# BreakOutBoard_Cyclone.net
KiCad netlist of a schematic drawn in Altium Designer
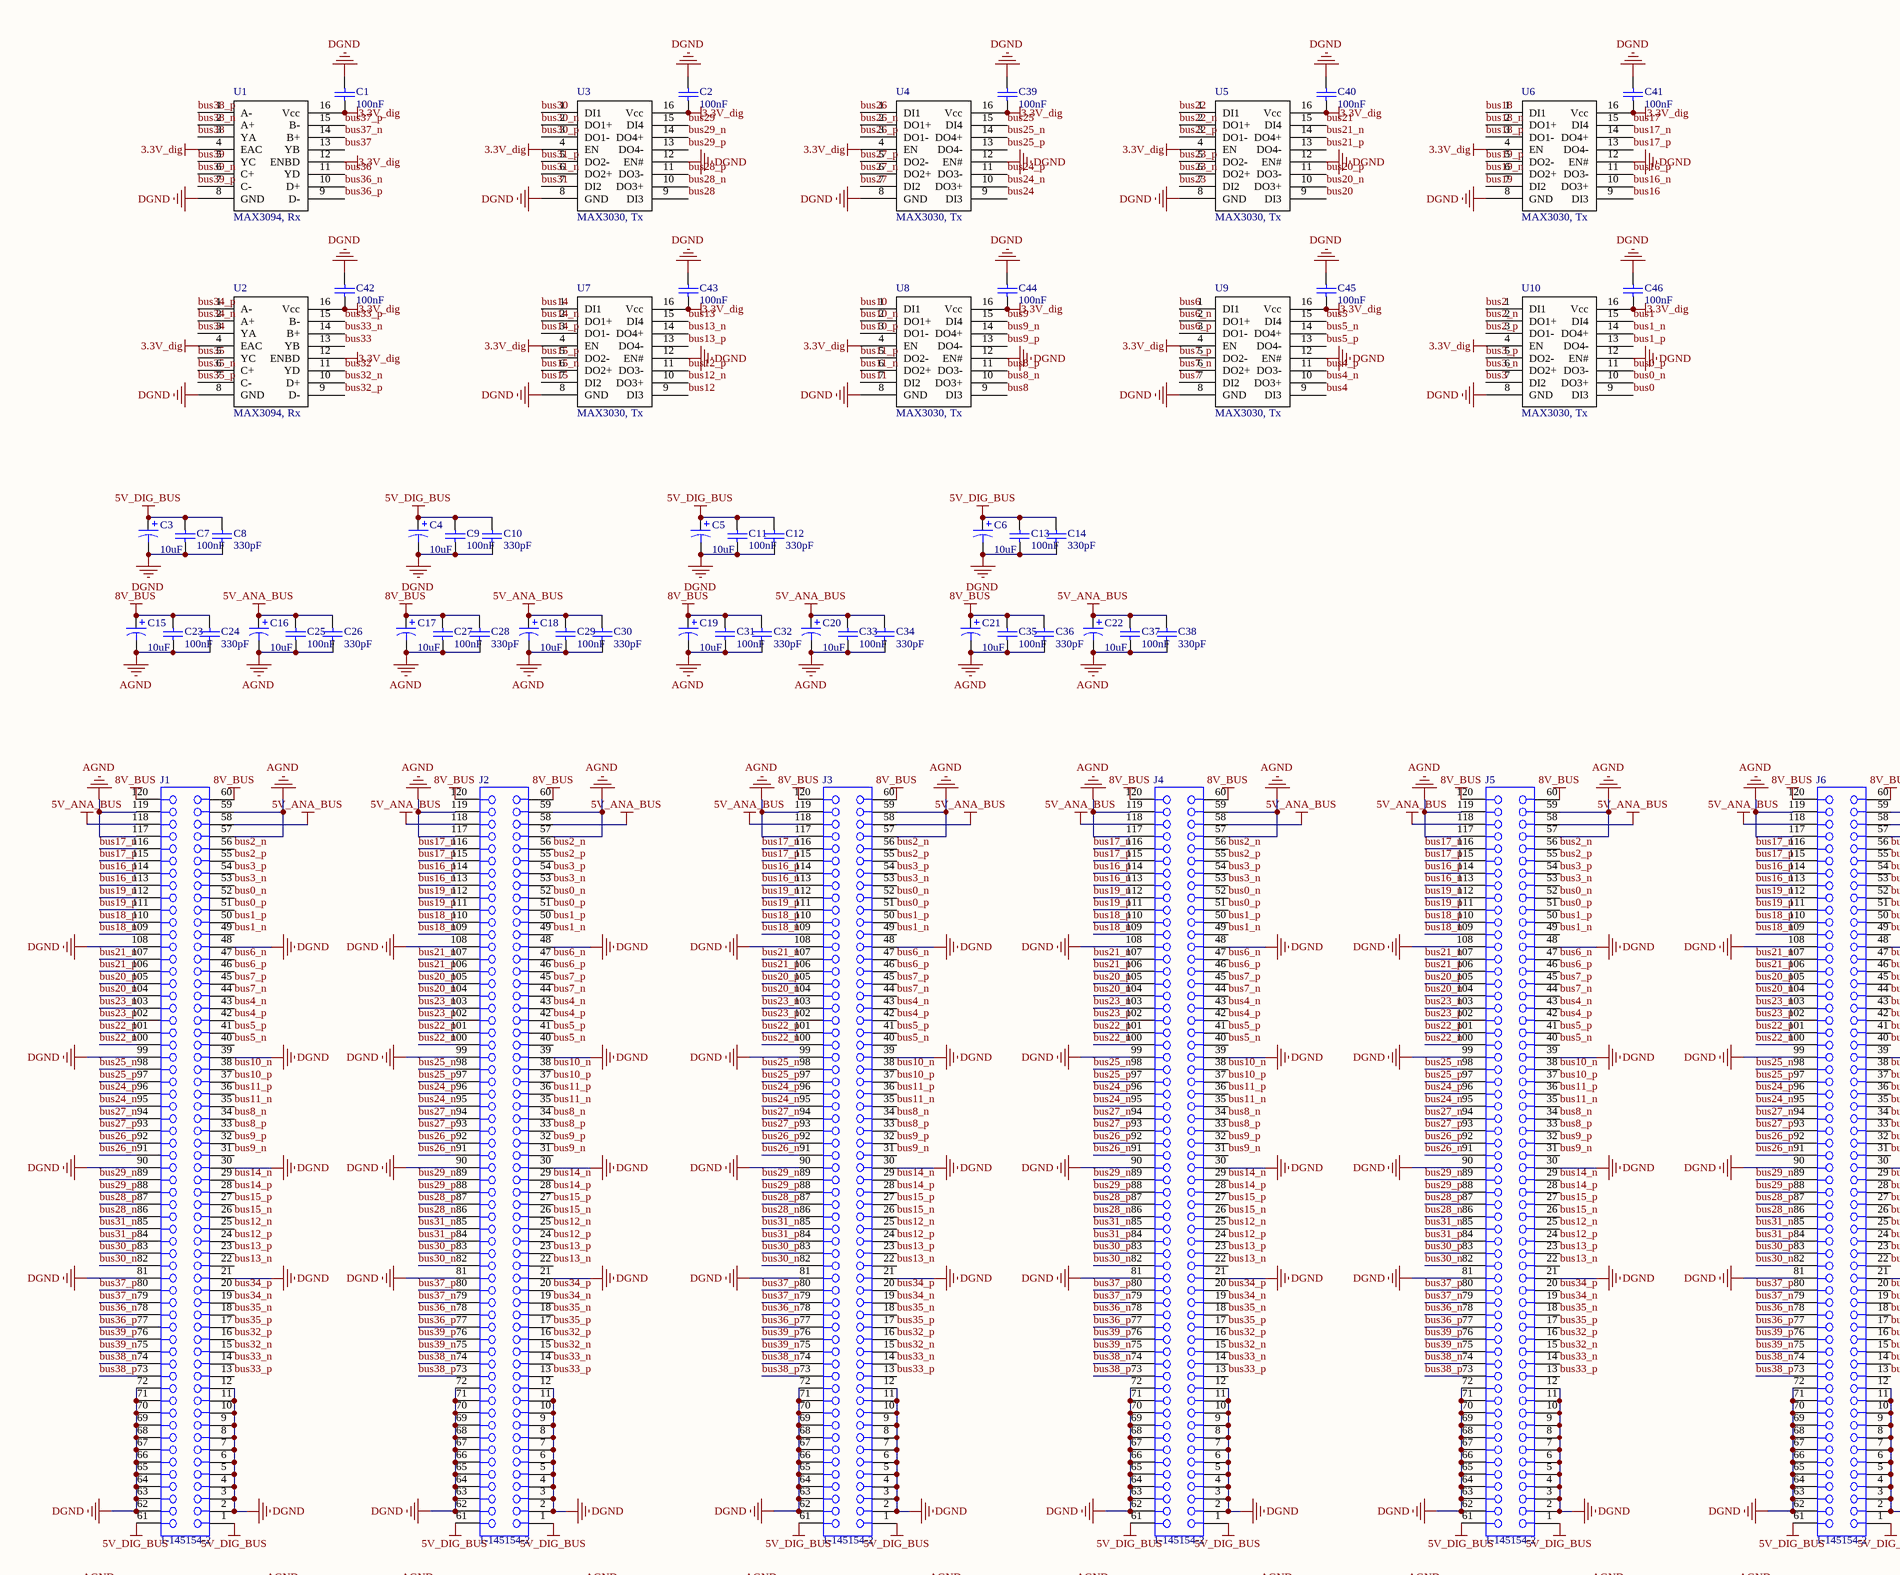
[diagram p0: BreakOutBoard_Cyclone.SchDoc, top left]
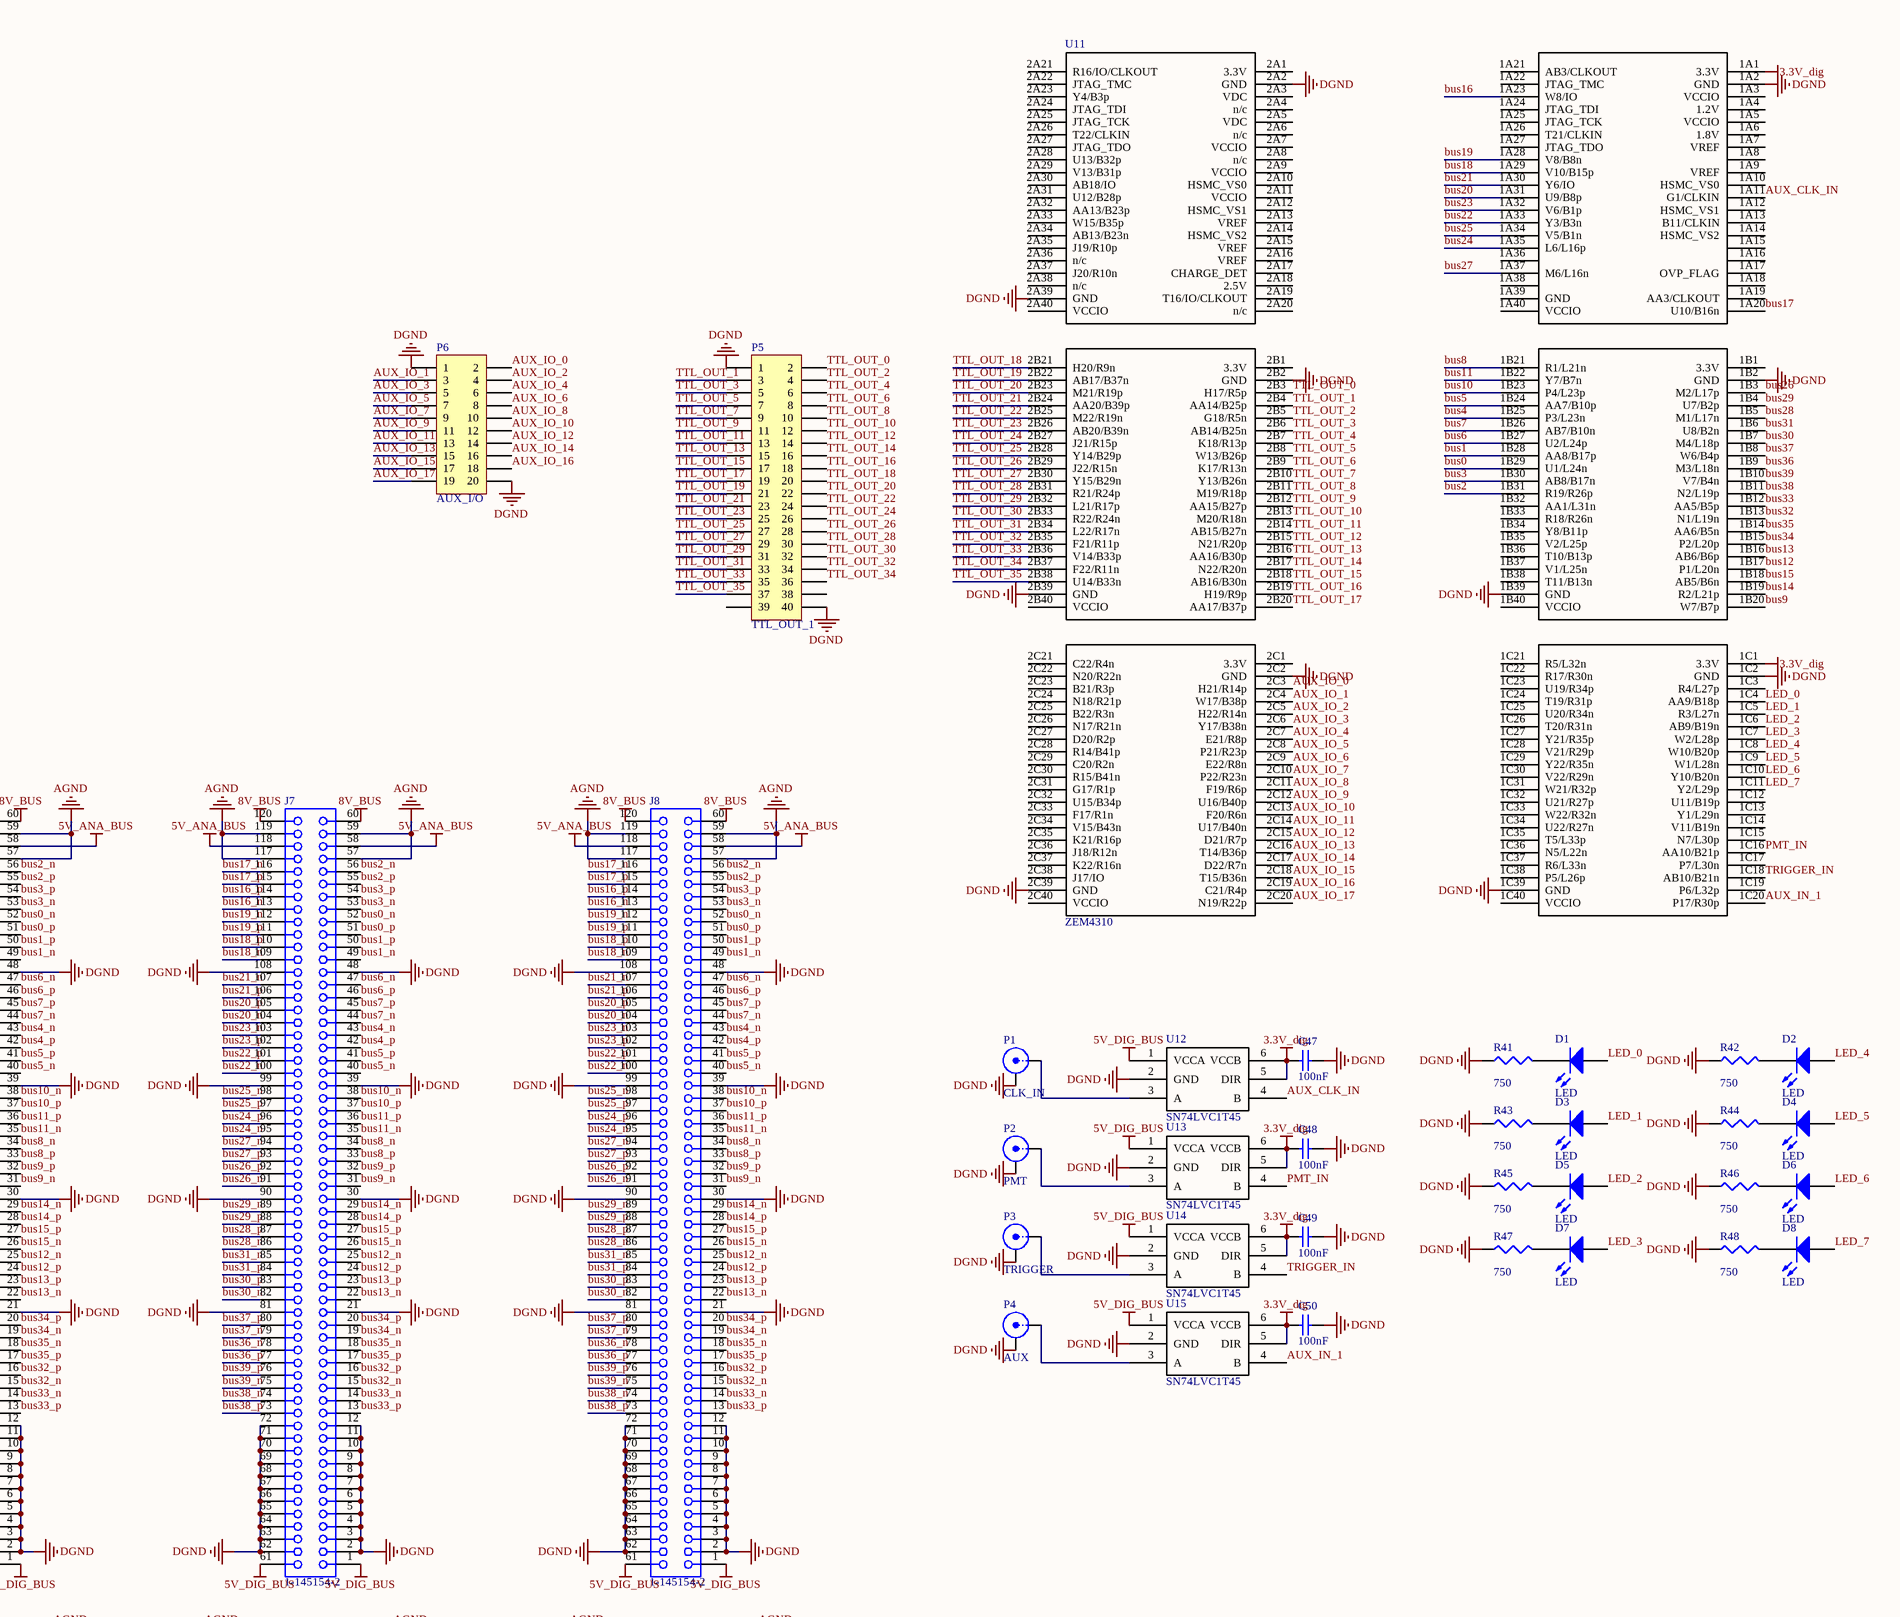
[diagram p1: BreakOutBoard_Cyclone.SchDoc, top right]
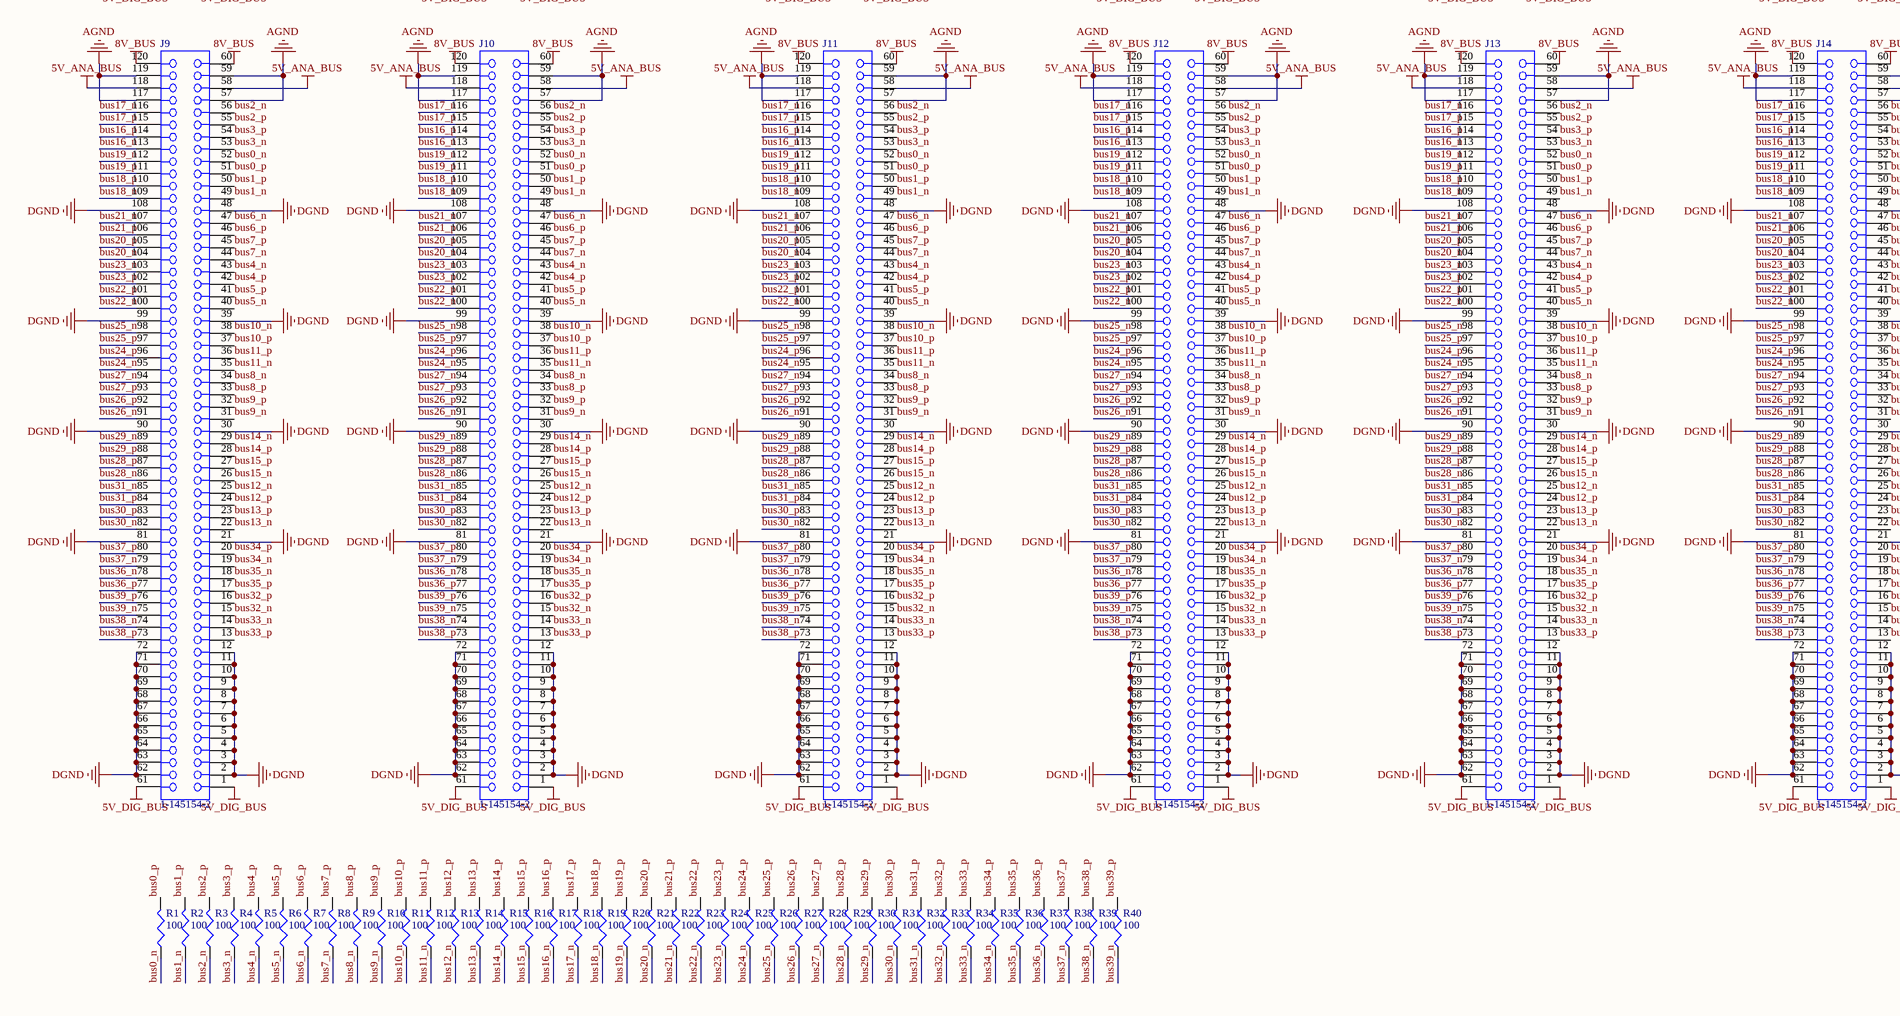
[diagram p2: BreakOutBoard_Cyclone.SchDoc, bottom left]
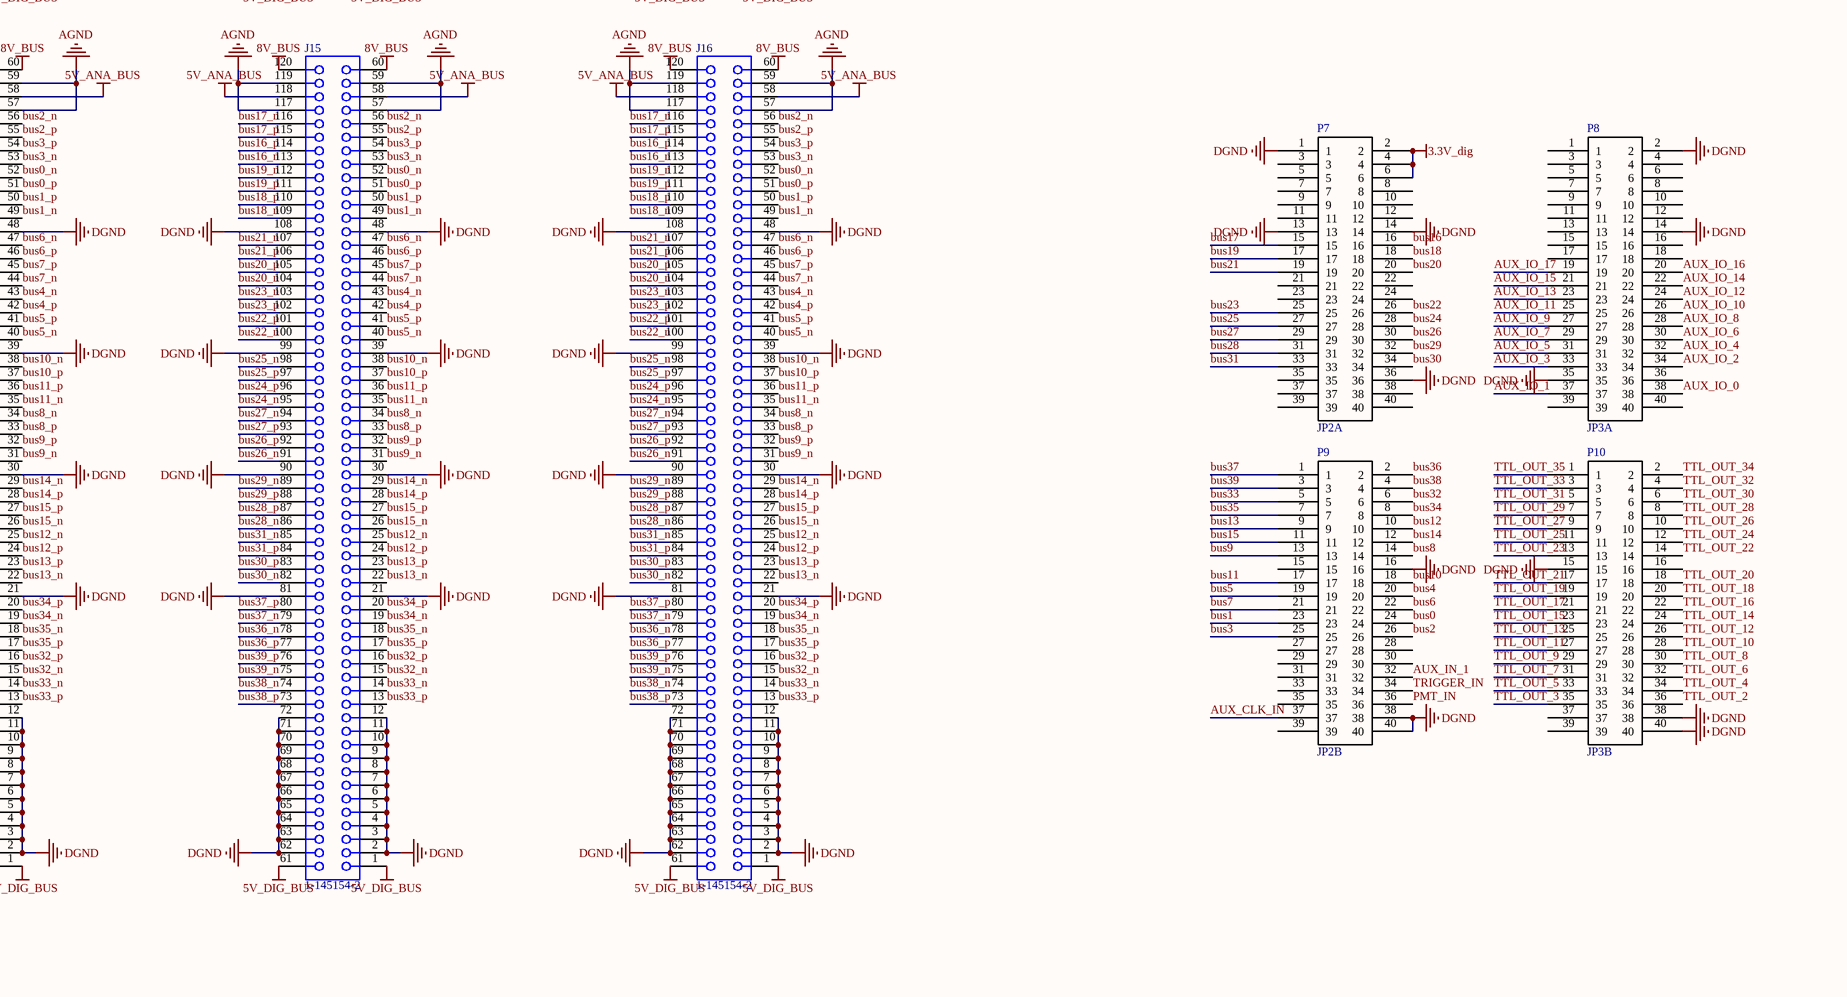
[diagram p3: BreakOutBoard_Cyclone.SchDoc, bottom right]

(export (version "E")
  (design (tool "Eeschema 10.0.6"))
  (components
    (comp (ref "C1")
      (value "100nF")
      (footprint "CAPC2012L")
      (description "Capacitor (Semiconductor SIM Model)")
      (fields (field (name "Comment") "Cap Semi") (field (name "PUBLISHER") "Altium Limited"))
      (libsource (lib "Miscellaneous Devices") (part "Cap Semi"))
    )
    (comp (ref "C2")
      (value "100nF")
      (footprint "CAPC2012L")
      (description "Capacitor (Semiconductor SIM Model)")
      (fields (field (name "Comment") "Cap Semi") (field (name "PUBLISHER") "Altium Limited"))
      (libsource (lib "Miscellaneous Devices") (part "Cap Semi"))
    )
    (comp (ref "C3")
      (value "10uF")
      (footprint "B")
      (description "Polarized Capacitor (Radial)")
      (fields
        (field (name "VOLTAGE") "16V")
        (field (name "Comment") "Cap Pol1")
        (field (name "PUBLISHER") "Altium Limited")
      )
      (libsource (lib "Miscellaneous Devices") (part "Cap Pol1"))
    )
    (comp (ref "C4")
      (value "10uF")
      (footprint "B")
      (description "Polarized Capacitor (Radial)")
      (fields
        (field (name "VOLTAGE") "16V")
        (field (name "Comment") "Cap Pol1")
        (field (name "PUBLISHER") "Altium Limited")
      )
      (libsource (lib "Miscellaneous Devices") (part "Cap Pol1"))
    )
    (comp (ref "C5")
      (value "10uF")
      (footprint "B")
      (description "Polarized Capacitor (Radial)")
      (fields
        (field (name "VOLTAGE") "16V")
        (field (name "Comment") "Cap Pol1")
        (field (name "PUBLISHER") "Altium Limited")
      )
      (libsource (lib "Miscellaneous Devices") (part "Cap Pol1"))
    )
    (comp (ref "C6")
      (value "10uF")
      (footprint "B")
      (description "Polarized Capacitor (Radial)")
      (fields
        (field (name "VOLTAGE") "16V")
        (field (name "Comment") "Cap Pol1")
        (field (name "PUBLISHER") "Altium Limited")
      )
      (libsource (lib "Miscellaneous Devices") (part "Cap Pol1"))
    )
    (comp (ref "C7")
      (value "100nF")
      (footprint "CAPC2012L")
      (description "Capacitor (Semiconductor SIM Model)")
      (fields (field (name "Comment") "Cap Semi") (field (name "PUBLISHER") "Altium Limited"))
      (libsource (lib "Miscellaneous Devices") (part "Cap Semi"))
    )
    (comp (ref "C8")
      (value "330pF")
      (footprint "CAPC2012L")
      (description "Capacitor (Semiconductor SIM Model)")
      (fields (field (name "Comment") "Cap Semi") (field (name "PUBLISHER") "Altium Limited"))
      (libsource (lib "Miscellaneous Devices") (part "Cap Semi"))
    )
    (comp (ref "C9")
      (value "100nF")
      (footprint "CAPC2012L")
      (description "Capacitor (Semiconductor SIM Model)")
      (fields (field (name "Comment") "Cap Semi") (field (name "PUBLISHER") "Altium Limited"))
      (libsource (lib "Miscellaneous Devices") (part "Cap Semi"))
    )
    (comp (ref "C10")
      (value "330pF")
      (footprint "CAPC2012L")
      (description "Capacitor (Semiconductor SIM Model)")
      (fields (field (name "Comment") "Cap Semi") (field (name "PUBLISHER") "Altium Limited"))
      (libsource (lib "Miscellaneous Devices") (part "Cap Semi"))
    )
    (comp (ref "C11")
      (value "100nF")
      (footprint "CAPC2012L")
      (description "Capacitor (Semiconductor SIM Model)")
      (fields (field (name "Comment") "Cap Semi") (field (name "PUBLISHER") "Altium Limited"))
      (libsource (lib "Miscellaneous Devices") (part "Cap Semi"))
    )
    (comp (ref "C12")
      (value "330pF")
      (footprint "CAPC2012L")
      (description "Capacitor (Semiconductor SIM Model)")
      (fields (field (name "Comment") "Cap Semi") (field (name "PUBLISHER") "Altium Limited"))
      (libsource (lib "Miscellaneous Devices") (part "Cap Semi"))
    )
    (comp (ref "C13")
      (value "100nF")
      (footprint "CAPC2012L")
      (description "Capacitor (Semiconductor SIM Model)")
      (fields (field (name "Comment") "Cap Semi") (field (name "PUBLISHER") "Altium Limited"))
      (libsource (lib "Miscellaneous Devices") (part "Cap Semi"))
    )
    (comp (ref "C14")
      (value "330pF")
      (footprint "CAPC2012L")
      (description "Capacitor (Semiconductor SIM Model)")
      (fields (field (name "Comment") "Cap Semi") (field (name "PUBLISHER") "Altium Limited"))
      (libsource (lib "Miscellaneous Devices") (part "Cap Semi"))
    )
    (comp (ref "C15")
      (value "10uF")
      (footprint "B")
      (description "Polarized Capacitor (Radial)")
      (fields
        (field (name "VOLTAGE") "16V")
        (field (name "Comment") "Cap Pol1")
        (field (name "PUBLISHER") "Altium Limited")
      )
      (libsource (lib "Miscellaneous Devices") (part "Cap Pol1"))
    )
    (comp (ref "C16")
      (value "10uF")
      (footprint "B")
      (description "Polarized Capacitor (Radial)")
      (fields
        (field (name "VOLTAGE") "16V")
        (field (name "Comment") "Cap Pol1")
        (field (name "PUBLISHER") "Altium Limited")
      )
      (libsource (lib "Miscellaneous Devices") (part "Cap Pol1"))
    )
    (comp (ref "C17")
      (value "10uF")
      (footprint "B")
      (description "Polarized Capacitor (Radial)")
      (fields
        (field (name "VOLTAGE") "16V")
        (field (name "Comment") "Cap Pol1")
        (field (name "PUBLISHER") "Altium Limited")
      )
      (libsource (lib "Miscellaneous Devices") (part "Cap Pol1"))
    )
    (comp (ref "C18")
      (value "10uF")
      (footprint "B")
      (description "Polarized Capacitor (Radial)")
      (fields
        (field (name "VOLTAGE") "16V")
        (field (name "Comment") "Cap Pol1")
        (field (name "PUBLISHER") "Altium Limited")
      )
      (libsource (lib "Miscellaneous Devices") (part "Cap Pol1"))
    )
    (comp (ref "C19")
      (value "10uF")
      (footprint "B")
      (description "Polarized Capacitor (Radial)")
      (fields
        (field (name "VOLTAGE") "16V")
        (field (name "Comment") "Cap Pol1")
        (field (name "PUBLISHER") "Altium Limited")
      )
      (libsource (lib "Miscellaneous Devices") (part "Cap Pol1"))
    )
    (comp (ref "C20")
      (value "10uF")
      (footprint "B")
      (description "Polarized Capacitor (Radial)")
      (fields
        (field (name "VOLTAGE") "16V")
        (field (name "Comment") "Cap Pol1")
        (field (name "PUBLISHER") "Altium Limited")
      )
      (libsource (lib "Miscellaneous Devices") (part "Cap Pol1"))
    )
    (comp (ref "C21")
      (value "10uF")
      (footprint "B")
      (description "Polarized Capacitor (Radial)")
      (fields
        (field (name "VOLTAGE") "16V")
        (field (name "Comment") "Cap Pol1")
        (field (name "PUBLISHER") "Altium Limited")
      )
      (libsource (lib "Miscellaneous Devices") (part "Cap Pol1"))
    )
    (comp (ref "C22")
      (value "10uF")
      (footprint "B")
      (description "Polarized Capacitor (Radial)")
      (fields
        (field (name "VOLTAGE") "16V")
        (field (name "Comment") "Cap Pol1")
        (field (name "PUBLISHER") "Altium Limited")
      )
      (libsource (lib "Miscellaneous Devices") (part "Cap Pol1"))
    )
    (comp (ref "C23")
      (value "100nF")
      (footprint "CAPC2012L")
      (description "Capacitor (Semiconductor SIM Model)")
      (fields (field (name "Comment") "Cap Semi") (field (name "PUBLISHER") "Altium Limited"))
      (libsource (lib "Miscellaneous Devices") (part "Cap Semi"))
    )
    (comp (ref "C24")
      (value "330pF")
      (footprint "CAPC2012L")
      (description "Capacitor (Semiconductor SIM Model)")
      (fields (field (name "Comment") "Cap Semi") (field (name "PUBLISHER") "Altium Limited"))
      (libsource (lib "Miscellaneous Devices") (part "Cap Semi"))
    )
    (comp (ref "C25")
      (value "100nF")
      (footprint "CAPC2012L")
      (description "Capacitor (Semiconductor SIM Model)")
      (fields (field (name "Comment") "Cap Semi") (field (name "PUBLISHER") "Altium Limited"))
      (libsource (lib "Miscellaneous Devices") (part "Cap Semi"))
    )
    (comp (ref "C26")
      (value "330pF")
      (footprint "CAPC2012L")
      (description "Capacitor (Semiconductor SIM Model)")
      (fields (field (name "Comment") "Cap Semi") (field (name "PUBLISHER") "Altium Limited"))
      (libsource (lib "Miscellaneous Devices") (part "Cap Semi"))
    )
    (comp (ref "C27")
      (value "100nF")
      (footprint "CAPC2012L")
      (description "Capacitor (Semiconductor SIM Model)")
      (fields (field (name "Comment") "Cap Semi") (field (name "PUBLISHER") "Altium Limited"))
      (libsource (lib "Miscellaneous Devices") (part "Cap Semi"))
    )
    (comp (ref "C28")
      (value "330pF")
      (footprint "CAPC2012L")
      (description "Capacitor (Semiconductor SIM Model)")
      (fields (field (name "Comment") "Cap Semi") (field (name "PUBLISHER") "Altium Limited"))
      (libsource (lib "Miscellaneous Devices") (part "Cap Semi"))
    )
    (comp (ref "C29")
      (value "100nF")
      (footprint "CAPC2012L")
      (description "Capacitor (Semiconductor SIM Model)")
      (fields (field (name "Comment") "Cap Semi") (field (name "PUBLISHER") "Altium Limited"))
      (libsource (lib "Miscellaneous Devices") (part "Cap Semi"))
    )
    (comp (ref "C30")
      (value "330pF")
      (footprint "CAPC2012L")
      (description "Capacitor (Semiconductor SIM Model)")
      (fields (field (name "Comment") "Cap Semi") (field (name "PUBLISHER") "Altium Limited"))
      (libsource (lib "Miscellaneous Devices") (part "Cap Semi"))
    )
    (comp (ref "C31")
      (value "100nF")
      (footprint "CAPC2012L")
      (description "Capacitor (Semiconductor SIM Model)")
      (fields (field (name "Comment") "Cap Semi") (field (name "PUBLISHER") "Altium Limited"))
      (libsource (lib "Miscellaneous Devices") (part "Cap Semi"))
    )
    (comp (ref "C32")
      (value "330pF")
      (footprint "CAPC2012L")
      (description "Capacitor (Semiconductor SIM Model)")
      (fields (field (name "Comment") "Cap Semi") (field (name "PUBLISHER") "Altium Limited"))
      (libsource (lib "Miscellaneous Devices") (part "Cap Semi"))
    )
    (comp (ref "C33")
      (value "100nF")
      (footprint "CAPC2012L")
      (description "Capacitor (Semiconductor SIM Model)")
      (fields (field (name "Comment") "Cap Semi") (field (name "PUBLISHER") "Altium Limited"))
      (libsource (lib "Miscellaneous Devices") (part "Cap Semi"))
    )
    (comp (ref "C34")
      (value "330pF")
      (footprint "CAPC2012L")
      (description "Capacitor (Semiconductor SIM Model)")
      (fields (field (name "Comment") "Cap Semi") (field (name "PUBLISHER") "Altium Limited"))
      (libsource (lib "Miscellaneous Devices") (part "Cap Semi"))
    )
    (comp (ref "C35")
      (value "100nF")
      (footprint "CAPC2012L")
      (description "Capacitor (Semiconductor SIM Model)")
      (fields (field (name "Comment") "Cap Semi") (field (name "PUBLISHER") "Altium Limited"))
      (libsource (lib "Miscellaneous Devices") (part "Cap Semi"))
    )
    (comp (ref "C36")
      (value "330pF")
      (footprint "CAPC2012L")
      (description "Capacitor (Semiconductor SIM Model)")
      (fields (field (name "Comment") "Cap Semi") (field (name "PUBLISHER") "Altium Limited"))
      (libsource (lib "Miscellaneous Devices") (part "Cap Semi"))
    )
    (comp (ref "C37")
      (value "100nF")
      (footprint "CAPC2012L")
      (description "Capacitor (Semiconductor SIM Model)")
      (fields (field (name "Comment") "Cap Semi") (field (name "PUBLISHER") "Altium Limited"))
      (libsource (lib "Miscellaneous Devices") (part "Cap Semi"))
    )
    (comp (ref "C38")
      (value "330pF")
      (footprint "CAPC2012L")
      (description "Capacitor (Semiconductor SIM Model)")
      (fields (field (name "Comment") "Cap Semi") (field (name "PUBLISHER") "Altium Limited"))
      (libsource (lib "Miscellaneous Devices") (part "Cap Semi"))
    )
    (comp (ref "C39")
      (value "100nF")
      (footprint "CAPC2012L")
      (description "Capacitor (Semiconductor SIM Model)")
      (fields (field (name "Comment") "Cap Semi") (field (name "PUBLISHER") "Altium Limited"))
      (libsource (lib "Miscellaneous Devices") (part "Cap Semi"))
    )
    (comp (ref "C40")
      (value "100nF")
      (footprint "CAPC2012L")
      (description "Capacitor (Semiconductor SIM Model)")
      (fields (field (name "Comment") "Cap Semi") (field (name "PUBLISHER") "Altium Limited"))
      (libsource (lib "Miscellaneous Devices") (part "Cap Semi"))
    )
    (comp (ref "C41")
      (value "100nF")
      (footprint "CAPC2012L")
      (description "Capacitor (Semiconductor SIM Model)")
      (fields (field (name "Comment") "Cap Semi") (field (name "PUBLISHER") "Altium Limited"))
      (libsource (lib "Miscellaneous Devices") (part "Cap Semi"))
    )
    (comp (ref "C42")
      (value "100nF")
      (footprint "CAPC2012L")
      (description "Capacitor (Semiconductor SIM Model)")
      (fields (field (name "Comment") "Cap Semi") (field (name "PUBLISHER") "Altium Limited"))
      (libsource (lib "Miscellaneous Devices") (part "Cap Semi"))
    )
    (comp (ref "C43")
      (value "100nF")
      (footprint "CAPC2012L")
      (description "Capacitor (Semiconductor SIM Model)")
      (fields (field (name "Comment") "Cap Semi") (field (name "PUBLISHER") "Altium Limited"))
      (libsource (lib "Miscellaneous Devices") (part "Cap Semi"))
    )
    (comp (ref "C44")
      (value "100nF")
      (footprint "CAPC2012L")
      (description "Capacitor (Semiconductor SIM Model)")
      (fields (field (name "Comment") "Cap Semi") (field (name "PUBLISHER") "Altium Limited"))
      (libsource (lib "Miscellaneous Devices") (part "Cap Semi"))
    )
    (comp (ref "C45")
      (value "100nF")
      (footprint "CAPC2012L")
      (description "Capacitor (Semiconductor SIM Model)")
      (fields (field (name "Comment") "Cap Semi") (field (name "PUBLISHER") "Altium Limited"))
      (libsource (lib "Miscellaneous Devices") (part "Cap Semi"))
    )
    (comp (ref "C46")
      (value "100nF")
      (footprint "CAPC2012L")
      (description "Capacitor (Semiconductor SIM Model)")
      (fields (field (name "Comment") "Cap Semi") (field (name "PUBLISHER") "Altium Limited"))
      (libsource (lib "Miscellaneous Devices") (part "Cap Semi"))
    )
    (comp (ref "C47")
      (value "100nF")
      (footprint "CAPC2012L")
      (description "Capacitor (Semiconductor SIM Model)")
      (fields (field (name "Comment") "Cap Semi") (field (name "PUBLISHER") "Altium Limited"))
      (libsource (lib "Miscellaneous Devices") (part "Cap Semi"))
    )
    (comp (ref "C48")
      (value "100nF")
      (footprint "CAPC2012L")
      (description "Capacitor (Semiconductor SIM Model)")
      (fields (field (name "Comment") "Cap Semi") (field (name "PUBLISHER") "Altium Limited"))
      (libsource (lib "Miscellaneous Devices") (part "Cap Semi"))
    )
    (comp (ref "C49")
      (value "100nF")
      (footprint "CAPC2012L")
      (description "Capacitor (Semiconductor SIM Model)")
      (fields (field (name "Comment") "Cap Semi") (field (name "PUBLISHER") "Altium Limited"))
      (libsource (lib "Miscellaneous Devices") (part "Cap Semi"))
    )
    (comp (ref "C50")
      (value "100nF")
      (footprint "CAPC2012L")
      (description "Capacitor (Semiconductor SIM Model)")
      (fields (field (name "Comment") "Cap Semi") (field (name "PUBLISHER") "Altium Limited"))
      (libsource (lib "Miscellaneous Devices") (part "Cap Semi"))
    )
    (comp (ref "D1")
      (value "LED")
      (footprint "RESC2012M")
      (description "Typical BLUE SiC LED")
      (fields (field (name "PUBLISHER") "Altium Limited"))
      (libsource (lib "Miscellaneous Devices") (part "LED3"))
    )
    (comp (ref "D2")
      (value "LED")
      (footprint "RESC2012M")
      (description "Typical BLUE SiC LED")
      (fields (field (name "PUBLISHER") "Altium Limited"))
      (libsource (lib "Miscellaneous Devices") (part "LED3"))
    )
    (comp (ref "D3")
      (value "LED")
      (footprint "RESC2012M")
      (description "Typical BLUE SiC LED")
      (fields (field (name "PUBLISHER") "Altium Limited"))
      (libsource (lib "Miscellaneous Devices") (part "LED3"))
    )
    (comp (ref "D4")
      (value "LED")
      (footprint "RESC2012M")
      (description "Typical BLUE SiC LED")
      (fields (field (name "PUBLISHER") "Altium Limited"))
      (libsource (lib "Miscellaneous Devices") (part "LED3"))
    )
    (comp (ref "D5")
      (value "LED")
      (footprint "RESC2012M")
      (description "Typical BLUE SiC LED")
      (fields (field (name "PUBLISHER") "Altium Limited"))
      (libsource (lib "Miscellaneous Devices") (part "LED3"))
    )
    (comp (ref "D6")
      (value "LED")
      (footprint "RESC2012M")
      (description "Typical BLUE SiC LED")
      (fields (field (name "PUBLISHER") "Altium Limited"))
      (libsource (lib "Miscellaneous Devices") (part "LED3"))
    )
    (comp (ref "D7")
      (value "LED")
      (footprint "RESC2012M")
      (description "Typical BLUE SiC LED")
      (fields (field (name "PUBLISHER") "Altium Limited"))
      (libsource (lib "Miscellaneous Devices") (part "LED3"))
    )
    (comp (ref "D8")
      (value "LED")
      (footprint "RESC2012M")
      (description "Typical BLUE SiC LED")
      (fields (field (name "PUBLISHER") "Altium Limited"))
      (libsource (lib "Miscellaneous Devices") (part "LED3"))
    )
    (comp (ref "J1")
      (value "1-145154-2")
      (footprint "1-145154-2")
      (description "Connector Assembly, 60 Dual Position, 1.27 [.050] Series, Standard Edge")
      (fields (field (name "VOLTAGE") "3.3V, 5V") (field (name "PUBLISHER") "Altium Limited"))
      (libsource (lib "AMP Card Edge 050 Series PCI") (part "1-145154-2"))
    )
    (comp (ref "J2")
      (value "1-145154-2")
      (footprint "1-145154-2")
      (description "Connector Assembly, 60 Dual Position, 1.27 [.050] Series, Standard Edge")
      (fields (field (name "VOLTAGE") "3.3V, 5V") (field (name "PUBLISHER") "Altium Limited"))
      (libsource (lib "AMP Card Edge 050 Series PCI") (part "1-145154-2"))
    )
    (comp (ref "J3")
      (value "1-145154-2")
      (footprint "1-145154-2")
      (description "Connector Assembly, 60 Dual Position, 1.27 [.050] Series, Standard Edge")
      (fields (field (name "VOLTAGE") "3.3V, 5V") (field (name "PUBLISHER") "Altium Limited"))
      (libsource (lib "AMP Card Edge 050 Series PCI") (part "1-145154-2"))
    )
    (comp (ref "J4")
      (value "1-145154-2")
      (footprint "1-145154-2")
      (description "Connector Assembly, 60 Dual Position, 1.27 [.050] Series, Standard Edge")
      (fields (field (name "VOLTAGE") "3.3V, 5V") (field (name "PUBLISHER") "Altium Limited"))
      (libsource (lib "AMP Card Edge 050 Series PCI") (part "1-145154-2"))
    )
    (comp (ref "J5")
      (value "1-145154-2")
      (footprint "1-145154-2")
      (description "Connector Assembly, 60 Dual Position, 1.27 [.050] Series, Standard Edge")
      (fields (field (name "VOLTAGE") "3.3V, 5V") (field (name "PUBLISHER") "Altium Limited"))
      (libsource (lib "AMP Card Edge 050 Series PCI") (part "1-145154-2"))
    )
    (comp (ref "J6")
      (value "1-145154-2")
      (footprint "1-145154-2")
      (description "Connector Assembly, 60 Dual Position, 1.27 [.050] Series, Standard Edge")
      (fields (field (name "VOLTAGE") "3.3V, 5V") (field (name "PUBLISHER") "Altium Limited"))
      (libsource (lib "AMP Card Edge 050 Series PCI") (part "1-145154-2"))
    )
    (comp (ref "J7")
      (value "1-145154-2")
      (footprint "1-145154-2")
      (description "Connector Assembly, 60 Dual Position, 1.27 [.050] Series, Standard Edge")
      (fields (field (name "VOLTAGE") "3.3V, 5V") (field (name "PUBLISHER") "Altium Limited"))
      (libsource (lib "AMP Card Edge 050 Series PCI") (part "1-145154-2"))
    )
    (comp (ref "J8")
      (value "1-145154-2")
      (footprint "1-145154-2")
      (description "Connector Assembly, 60 Dual Position, 1.27 [.050] Series, Standard Edge")
      (fields (field (name "VOLTAGE") "3.3V, 5V") (field (name "PUBLISHER") "Altium Limited"))
      (libsource (lib "AMP Card Edge 050 Series PCI") (part "1-145154-2"))
    )
    (comp (ref "J9")
      (value "1-145154-2")
      (footprint "1-145154-2")
      (description "Connector Assembly, 60 Dual Position, 1.27 [.050] Series, Standard Edge")
      (fields (field (name "VOLTAGE") "3.3V, 5V") (field (name "PUBLISHER") "Altium Limited"))
      (libsource (lib "AMP Card Edge 050 Series PCI") (part "1-145154-2"))
    )
    (comp (ref "J10")
      (value "1-145154-2")
      (footprint "1-145154-2")
      (description "Connector Assembly, 60 Dual Position, 1.27 [.050] Series, Standard Edge")
      (fields (field (name "VOLTAGE") "3.3V, 5V") (field (name "PUBLISHER") "Altium Limited"))
      (libsource (lib "AMP Card Edge 050 Series PCI") (part "1-145154-2"))
    )
    (comp (ref "J11")
      (value "1-145154-2")
      (footprint "1-145154-2")
      (description "Connector Assembly, 60 Dual Position, 1.27 [.050] Series, Standard Edge")
      (fields (field (name "VOLTAGE") "3.3V, 5V") (field (name "PUBLISHER") "Altium Limited"))
      (libsource (lib "AMP Card Edge 050 Series PCI") (part "1-145154-2"))
    )
    (comp (ref "J12")
      (value "1-145154-2")
      (footprint "1-145154-2")
      (description "Connector Assembly, 60 Dual Position, 1.27 [.050] Series, Standard Edge")
      (fields (field (name "VOLTAGE") "3.3V, 5V") (field (name "PUBLISHER") "Altium Limited"))
      (libsource (lib "AMP Card Edge 050 Series PCI") (part "1-145154-2"))
    )
    (comp (ref "J13")
      (value "1-145154-2")
      (footprint "1-145154-2")
      (description "Connector Assembly, 60 Dual Position, 1.27 [.050] Series, Standard Edge")
      (fields (field (name "VOLTAGE") "3.3V, 5V") (field (name "PUBLISHER") "Altium Limited"))
      (libsource (lib "AMP Card Edge 050 Series PCI") (part "1-145154-2"))
    )
    (comp (ref "J14")
      (value "1-145154-2")
      (footprint "1-145154-2")
      (description "Connector Assembly, 60 Dual Position, 1.27 [.050] Series, Standard Edge")
      (fields (field (name "VOLTAGE") "3.3V, 5V") (field (name "PUBLISHER") "Altium Limited"))
      (libsource (lib "AMP Card Edge 050 Series PCI") (part "1-145154-2"))
    )
    (comp (ref "J15")
      (value "1-145154-2")
      (footprint "1-145154-2")
      (description "Connector Assembly, 60 Dual Position, 1.27 [.050] Series, Standard Edge")
      (fields (field (name "VOLTAGE") "3.3V, 5V") (field (name "PUBLISHER") "Altium Limited"))
      (libsource (lib "AMP Card Edge 050 Series PCI") (part "1-145154-2"))
    )
    (comp (ref "J16")
      (value "1-145154-2")
      (footprint "1-145154-2")
      (description "Connector Assembly, 60 Dual Position, 1.27 [.050] Series, Standard Edge")
      (fields (field (name "VOLTAGE") "3.3V, 5V") (field (name "PUBLISHER") "Altium Limited"))
      (libsource (lib "AMP Card Edge 050 Series PCI") (part "1-145154-2"))
    )
    (comp (ref "P1")
      (value "CLK_IN")
      (footprint "BNC_RA CON")
      (description "BNC Elbow Connector")
      (fields (field (name "PUBLISHER") "Altium Limited"))
      (libsource (lib "Miscellaneous Connectors") (part "BNC"))
    )
    (comp (ref "P2")
      (value "PMT")
      (footprint "BNC_RA CON")
      (description "BNC Elbow Connector")
      (fields (field (name "PUBLISHER") "Altium Limited"))
      (libsource (lib "Miscellaneous Connectors") (part "BNC"))
    )
    (comp (ref "P3")
      (value "TRIGGER")
      (footprint "BNC_RA CON")
      (description "BNC Elbow Connector")
      (fields (field (name "PUBLISHER") "Altium Limited"))
      (libsource (lib "Miscellaneous Connectors") (part "BNC"))
    )
    (comp (ref "P4")
      (value "AUX")
      (footprint "BNC_RA CON")
      (description "BNC Elbow Connector")
      (fields (field (name "PUBLISHER") "Altium Limited"))
      (libsource (lib "Miscellaneous Connectors") (part "BNC"))
    )
    (comp (ref "P5")
      (value "TTL_OUT_1")
      (footprint "HDR2X20")
      (description "Header, 20-Pin, Dual row")
      (fields (field (name "PUBLISHER") "Altium Limited"))
      (libsource (lib "Miscellaneous Connectors") (part "Header 20X2"))
    )
    (comp (ref "P6")
      (value "AUX_I/O")
      (footprint "HDR2X10")
      (description "Header, 10-Pin, Dual row")
      (fields (field (name "PUBLISHER") "Altium Limited"))
      (libsource (lib "Miscellaneous Connectors") (part "Header 10X2"))
    )
    (comp (ref "P7")
      (value "JP2A")
      (footprint "connector_40pos_2mm")
      (description "2 mm connector 40 positions")
      (fields (field (name "PUBLISHER") "Altium Limited"))
      (libsource (lib "HH_chips") (part "CONN_40_2mm"))
    )
    (comp (ref "P8")
      (value "JP3A")
      (footprint "connector_40pos_2mm")
      (description "2 mm connector 40 positions")
      (fields (field (name "PUBLISHER") "Altium Limited"))
      (libsource (lib "HH_chips") (part "CONN_40_2mm"))
    )
    (comp (ref "P9")
      (value "JP2B")
      (footprint "connector_40pos_2mm")
      (description "2 mm connector 40 positions")
      (fields (field (name "PUBLISHER") "Altium Limited"))
      (libsource (lib "HH_chips") (part "CONN_40_2mm"))
    )
    (comp (ref "P10")
      (value "JP3B")
      (footprint "connector_40pos_2mm")
      (description "2 mm connector 40 positions")
      (fields (field (name "PUBLISHER") "Altium Limited"))
      (libsource (lib "HH_chips") (part "CONN_40_2mm"))
    )
    (comp (ref "R1")
      (value "100")
      (footprint "RESC3216L")
      (description "Resistor")
      (fields (field (name "PUBLISHER") "Altium Limited"))
      (libsource (lib "Miscellaneous Devices") (part "Res3"))
    )
    (comp (ref "R2")
      (value "100")
      (footprint "RESC3216L")
      (description "Resistor")
      (fields (field (name "PUBLISHER") "Altium Limited"))
      (libsource (lib "Miscellaneous Devices") (part "Res3"))
    )
    (comp (ref "R3")
      (value "100")
      (footprint "RESC3216L")
      (description "Resistor")
      (fields (field (name "PUBLISHER") "Altium Limited"))
      (libsource (lib "Miscellaneous Devices") (part "Res3"))
    )
    (comp (ref "R4")
      (value "100")
      (footprint "RESC3216L")
      (description "Resistor")
      (fields (field (name "PUBLISHER") "Altium Limited"))
      (libsource (lib "Miscellaneous Devices") (part "Res3"))
    )
    (comp (ref "R5")
      (value "100")
      (footprint "RESC3216L")
      (description "Resistor")
      (fields (field (name "PUBLISHER") "Altium Limited"))
      (libsource (lib "Miscellaneous Devices") (part "Res3"))
    )
    (comp (ref "R6")
      (value "100")
      (footprint "RESC3216L")
      (description "Resistor")
      (fields (field (name "PUBLISHER") "Altium Limited"))
      (libsource (lib "Miscellaneous Devices") (part "Res3"))
    )
    (comp (ref "R7")
      (value "100")
      (footprint "RESC3216L")
      (description "Resistor")
      (fields (field (name "PUBLISHER") "Altium Limited"))
      (libsource (lib "Miscellaneous Devices") (part "Res3"))
    )
    (comp (ref "R8")
      (value "100")
      (footprint "RESC3216L")
      (description "Resistor")
      (fields (field (name "PUBLISHER") "Altium Limited"))
      (libsource (lib "Miscellaneous Devices") (part "Res3"))
    )
    (comp (ref "R9")
      (value "100")
      (footprint "RESC3216L")
      (description "Resistor")
      (fields (field (name "PUBLISHER") "Altium Limited"))
      (libsource (lib "Miscellaneous Devices") (part "Res3"))
    )
    (comp (ref "R10")
      (value "100")
      (footprint "RESC3216L")
      (description "Resistor")
      (fields (field (name "PUBLISHER") "Altium Limited"))
      (libsource (lib "Miscellaneous Devices") (part "Res3"))
    )
    (comp (ref "R11")
      (value "100")
      (footprint "RESC3216L")
      (description "Resistor")
      (fields (field (name "PUBLISHER") "Altium Limited"))
      (libsource (lib "Miscellaneous Devices") (part "Res3"))
    )
    (comp (ref "R12")
      (value "100")
      (footprint "RESC3216L")
      (description "Resistor")
      (fields (field (name "PUBLISHER") "Altium Limited"))
      (libsource (lib "Miscellaneous Devices") (part "Res3"))
    )
    (comp (ref "R13")
      (value "100")
      (footprint "RESC3216L")
      (description "Resistor")
      (fields (field (name "PUBLISHER") "Altium Limited"))
      (libsource (lib "Miscellaneous Devices") (part "Res3"))
    )
    (comp (ref "R14")
      (value "100")
      (footprint "RESC3216L")
      (description "Resistor")
      (fields (field (name "PUBLISHER") "Altium Limited"))
      (libsource (lib "Miscellaneous Devices") (part "Res3"))
    )
    (comp (ref "R15")
      (value "100")
      (footprint "RESC3216L")
      (description "Resistor")
      (fields (field (name "PUBLISHER") "Altium Limited"))
      (libsource (lib "Miscellaneous Devices") (part "Res3"))
    )
    (comp (ref "R16")
      (value "100")
      (footprint "RESC3216L")
      (description "Resistor")
      (fields (field (name "PUBLISHER") "Altium Limited"))
      (libsource (lib "Miscellaneous Devices") (part "Res3"))
    )
    (comp (ref "R17")
      (value "100")
      (footprint "RESC3216L")
      (description "Resistor")
      (fields (field (name "PUBLISHER") "Altium Limited"))
      (libsource (lib "Miscellaneous Devices") (part "Res3"))
    )
    (comp (ref "R18")
      (value "100")
      (footprint "RESC3216L")
      (description "Resistor")
      (fields (field (name "PUBLISHER") "Altium Limited"))
      (libsource (lib "Miscellaneous Devices") (part "Res3"))
    )
    (comp (ref "R19")
      (value "100")
      (footprint "RESC3216L")
      (description "Resistor")
      (fields (field (name "PUBLISHER") "Altium Limited"))
      (libsource (lib "Miscellaneous Devices") (part "Res3"))
    )
    (comp (ref "R20")
      (value "100")
      (footprint "RESC3216L")
      (description "Resistor")
      (fields (field (name "PUBLISHER") "Altium Limited"))
      (libsource (lib "Miscellaneous Devices") (part "Res3"))
    )
    (comp (ref "R21")
      (value "100")
      (footprint "RESC3216L")
      (description "Resistor")
      (fields (field (name "PUBLISHER") "Altium Limited"))
      (libsource (lib "Miscellaneous Devices") (part "Res3"))
    )
    (comp (ref "R22")
      (value "100")
      (footprint "RESC3216L")
      (description "Resistor")
      (fields (field (name "PUBLISHER") "Altium Limited"))
      (libsource (lib "Miscellaneous Devices") (part "Res3"))
    )
    (comp (ref "R23")
      (value "100")
      (footprint "RESC3216L")
      (description "Resistor")
      (fields (field (name "PUBLISHER") "Altium Limited"))
      (libsource (lib "Miscellaneous Devices") (part "Res3"))
    )
    (comp (ref "R24")
      (value "100")
      (footprint "RESC3216L")
      (description "Resistor")
      (fields (field (name "PUBLISHER") "Altium Limited"))
      (libsource (lib "Miscellaneous Devices") (part "Res3"))
    )
    (comp (ref "R25")
      (value "100")
      (footprint "RESC3216L")
      (description "Resistor")
      (fields (field (name "PUBLISHER") "Altium Limited"))
      (libsource (lib "Miscellaneous Devices") (part "Res3"))
    )
    (comp (ref "R26")
      (value "100")
      (footprint "RESC3216L")
      (description "Resistor")
      (fields (field (name "PUBLISHER") "Altium Limited"))
      (libsource (lib "Miscellaneous Devices") (part "Res3"))
    )
    (comp (ref "R27")
      (value "100")
      (footprint "RESC3216L")
      (description "Resistor")
      (fields (field (name "PUBLISHER") "Altium Limited"))
      (libsource (lib "Miscellaneous Devices") (part "Res3"))
    )
    (comp (ref "R28")
      (value "100")
      (footprint "RESC3216L")
      (description "Resistor")
      (fields (field (name "PUBLISHER") "Altium Limited"))
      (libsource (lib "Miscellaneous Devices") (part "Res3"))
    )
    (comp (ref "R29")
      (value "100")
      (footprint "RESC3216L")
      (description "Resistor")
      (fields (field (name "PUBLISHER") "Altium Limited"))
      (libsource (lib "Miscellaneous Devices") (part "Res3"))
    )
    (comp (ref "R30")
      (value "100")
      (footprint "RESC3216L")
      (description "Resistor")
      (fields (field (name "PUBLISHER") "Altium Limited"))
      (libsource (lib "Miscellaneous Devices") (part "Res3"))
    )
    (comp (ref "R31")
      (value "100")
      (footprint "RESC3216L")
      (description "Resistor")
      (fields (field (name "PUBLISHER") "Altium Limited"))
      (libsource (lib "Miscellaneous Devices") (part "Res3"))
    )
    (comp (ref "R32")
      (value "100")
      (footprint "RESC3216L")
      (description "Resistor")
      (fields (field (name "PUBLISHER") "Altium Limited"))
      (libsource (lib "Miscellaneous Devices") (part "Res3"))
    )
    (comp (ref "R33")
      (value "100")
      (footprint "RESC3216L")
      (description "Resistor")
      (fields (field (name "PUBLISHER") "Altium Limited"))
      (libsource (lib "Miscellaneous Devices") (part "Res3"))
    )
    (comp (ref "R34")
      (value "100")
      (footprint "RESC3216L")
      (description "Resistor")
      (fields (field (name "PUBLISHER") "Altium Limited"))
      (libsource (lib "Miscellaneous Devices") (part "Res3"))
    )
    (comp (ref "R35")
      (value "100")
      (footprint "RESC3216L")
      (description "Resistor")
      (fields (field (name "PUBLISHER") "Altium Limited"))
      (libsource (lib "Miscellaneous Devices") (part "Res3"))
    )
    (comp (ref "R36")
      (value "100")
      (footprint "RESC3216L")
      (description "Resistor")
      (fields (field (name "PUBLISHER") "Altium Limited"))
      (libsource (lib "Miscellaneous Devices") (part "Res3"))
    )
    (comp (ref "R37")
      (value "100")
      (footprint "RESC3216L")
      (description "Resistor")
      (fields (field (name "PUBLISHER") "Altium Limited"))
      (libsource (lib "Miscellaneous Devices") (part "Res3"))
    )
    (comp (ref "R38")
      (value "100")
      (footprint "RESC3216L")
      (description "Resistor")
      (fields (field (name "PUBLISHER") "Altium Limited"))
      (libsource (lib "Miscellaneous Devices") (part "Res3"))
    )
    (comp (ref "R39")
      (value "100")
      (footprint "RESC3216L")
      (description "Resistor")
      (fields (field (name "PUBLISHER") "Altium Limited"))
      (libsource (lib "Miscellaneous Devices") (part "Res3"))
    )
    (comp (ref "R40")
      (value "100")
      (footprint "RESC3216L")
      (description "Resistor")
      (fields (field (name "PUBLISHER") "Altium Limited"))
      (libsource (lib "Miscellaneous Devices") (part "Res3"))
    )
    (comp (ref "R41")
      (value "750")
      (footprint "RESC2012M")
      (description "Resistor")
      (fields (field (name "Comment") "Res3") (field (name "PUBLISHER") "Altium Limited"))
      (libsource (lib "Miscellaneous Devices") (part "Res3"))
    )
    (comp (ref "R42")
      (value "750")
      (footprint "RESC2012M")
      (description "Resistor")
      (fields (field (name "Comment") "Res3") (field (name "PUBLISHER") "Altium Limited"))
      (libsource (lib "Miscellaneous Devices") (part "Res3"))
    )
    (comp (ref "R43")
      (value "750")
      (footprint "RESC2012M")
      (description "Resistor")
      (fields (field (name "Comment") "Res3") (field (name "PUBLISHER") "Altium Limited"))
      (libsource (lib "Miscellaneous Devices") (part "Res3"))
    )
    (comp (ref "R44")
      (value "750")
      (footprint "RESC2012M")
      (description "Resistor")
      (fields (field (name "Comment") "Res3") (field (name "PUBLISHER") "Altium Limited"))
      (libsource (lib "Miscellaneous Devices") (part "Res3"))
    )
    (comp (ref "R45")
      (value "750")
      (footprint "RESC2012M")
      (description "Resistor")
      (fields (field (name "Comment") "Res3") (field (name "PUBLISHER") "Altium Limited"))
      (libsource (lib "Miscellaneous Devices") (part "Res3"))
    )
    (comp (ref "R46")
      (value "750")
      (footprint "RESC2012M")
      (description "Resistor")
      (fields (field (name "Comment") "Res3") (field (name "PUBLISHER") "Altium Limited"))
      (libsource (lib "Miscellaneous Devices") (part "Res3"))
    )
    (comp (ref "R47")
      (value "750")
      (footprint "RESC2012M")
      (description "Resistor")
      (fields (field (name "Comment") "Res3") (field (name "PUBLISHER") "Altium Limited"))
      (libsource (lib "Miscellaneous Devices") (part "Res3"))
    )
    (comp (ref "R48")
      (value "750")
      (footprint "RESC2012M")
      (description "Resistor")
      (fields (field (name "Comment") "Res3") (field (name "PUBLISHER") "Altium Limited"))
      (libsource (lib "Miscellaneous Devices") (part "Res3"))
    )
    (comp (ref "U1")
      (value "MAX3094, Rx")
      (footprint "NSO16_N")
      (description "Differential Line Receivers")
      (libsource (lib "HH_chips") (part "MAX3094"))
    )
    (comp (ref "U2")
      (value "MAX3094, Rx")
      (footprint "NSO16_N")
      (description "Differential Line Receivers")
      (libsource (lib "HH_chips") (part "MAX3094"))
    )
    (comp (ref "U3")
      (value "MAX3030, Tx")
      (footprint "NSO16_N")
      (description "Differential Line Transmitter")
      (libsource (lib "HH_chips") (part "MAX3030"))
    )
    (comp (ref "U4")
      (value "MAX3030, Tx")
      (footprint "NSO16_N")
      (description "Differential Line Transmitter")
      (libsource (lib "HH_chips") (part "MAX3030"))
    )
    (comp (ref "U5")
      (value "MAX3030, Tx")
      (footprint "NSO16_N")
      (description "Differential Line Transmitter")
      (libsource (lib "HH_chips") (part "MAX3030"))
    )
    (comp (ref "U6")
      (value "MAX3030, Tx")
      (footprint "NSO16_N")
      (description "Differential Line Transmitter")
      (libsource (lib "HH_chips") (part "MAX3030"))
    )
    (comp (ref "U7")
      (value "MAX3030, Tx")
      (footprint "NSO16_N")
      (description "Differential Line Transmitter")
      (libsource (lib "HH_chips") (part "MAX3030"))
    )
    (comp (ref "U8")
      (value "MAX3030, Tx")
      (footprint "NSO16_N")
      (description "Differential Line Transmitter")
      (libsource (lib "HH_chips") (part "MAX3030"))
    )
    (comp (ref "U9")
      (value "MAX3030, Tx")
      (footprint "NSO16_N")
      (description "Differential Line Transmitter")
      (libsource (lib "HH_chips") (part "MAX3030"))
    )
    (comp (ref "U10")
      (value "MAX3030, Tx")
      (footprint "NSO16_N")
      (description "Differential Line Transmitter")
      (libsource (lib "HH_chips") (part "MAX3030"))
    )
    (comp (ref "U11")
      (value "ZEM4310")
      (footprint "ZEM4310")
      (description "ZEM4310 breakout module")
      (libsource (lib "HH_chips") (part "ZEM4310"))
    )
    (comp (ref "U12")
      (value "SN74LVC1T45")
      (footprint "SOT23-6")
      (description "Logic Translator (Bidirectional)")
      (libsource (lib "HH_chips") (part "SN74LVC1T45"))
    )
    (comp (ref "U13")
      (value "SN74LVC1T45")
      (footprint "SOT23-6")
      (description "Logic Translator (Bidirectional)")
      (libsource (lib "HH_chips") (part "SN74LVC1T45"))
    )
    (comp (ref "U14")
      (value "SN74LVC1T45")
      (footprint "SOT23-6")
      (description "Logic Translator (Bidirectional)")
      (libsource (lib "HH_chips") (part "SN74LVC1T45"))
    )
    (comp (ref "U15")
      (value "SN74LVC1T45")
      (footprint "SOT23-6")
      (description "Logic Translator (Bidirectional)")
      (libsource (lib "HH_chips") (part "SN74LVC1T45"))
    )
  )
  (nets
    (net (code "1") (name "/AUX_CLK_IN") (class "Default")
      (node (ref "P9") (pin "37") (pinfunction "37_37") (pintype "passive"))
      (node (ref "U11") (pin "1A11") (pinfunction "G1/CLKIN_1A11") (pintype "passive"))
      (node (ref "U12") (pin "4") (pinfunction "B_4") (pintype "passive"))
    )
    (net (code "2") (name "/AUX_IN_1") (class "Default")
      (node (ref "P9") (pin "32") (pinfunction "32_32") (pintype "passive"))
      (node (ref "U11") (pin "1C20") (pinfunction "P17/R30p_1C20") (pintype "passive"))
      (node (ref "U15") (pin "4") (pinfunction "B_4") (pintype "passive"))
    )
    (net (code "3") (name "/AUX_IO_0") (class "Default")
      (node (ref "P6") (pin "2") (pinfunction "2_2") (pintype "passive"))
      (node (ref "P8") (pin "38") (pinfunction "38_38") (pintype "passive"))
      (node (ref "U11") (pin "2C3") (pinfunction "H21/R14p_2C3") (pintype "passive"))
    )
    (net (code "4") (name "/AUX_IO_1") (class "Default")
      (node (ref "P6") (pin "3") (pinfunction "3_3") (pintype "passive"))
      (node (ref "P8") (pin "37") (pinfunction "37_37") (pintype "passive"))
      (node (ref "U11") (pin "2C4") (pinfunction "W17/B38p_2C4") (pintype "passive"))
    )
    (net (code "5") (name "/AUX_IO_2") (class "Default")
      (node (ref "P6") (pin "4") (pinfunction "4_4") (pintype "passive"))
      (node (ref "P8") (pin "34") (pinfunction "34_34") (pintype "passive"))
      (node (ref "U11") (pin "2C5") (pinfunction "H22/R14n_2C5") (pintype "passive"))
    )
    (net (code "6") (name "/AUX_IO_3") (class "Default")
      (node (ref "P6") (pin "5") (pinfunction "5_5") (pintype "passive"))
      (node (ref "P8") (pin "33") (pinfunction "33_33") (pintype "passive"))
      (node (ref "U11") (pin "2C6") (pinfunction "Y17/B38n_2C6") (pintype "passive"))
    )
    (net (code "7") (name "/AUX_IO_4") (class "Default")
      (node (ref "P6") (pin "6") (pinfunction "6_6") (pintype "passive"))
      (node (ref "P8") (pin "32") (pinfunction "32_32") (pintype "passive"))
      (node (ref "U11") (pin "2C7") (pinfunction "E21/R8p_2C7") (pintype "passive"))
    )
    (net (code "8") (name "/AUX_IO_5") (class "Default")
      (node (ref "P6") (pin "7") (pinfunction "7_7") (pintype "passive"))
      (node (ref "P8") (pin "31") (pinfunction "31_31") (pintype "passive"))
      (node (ref "U11") (pin "2C8") (pinfunction "P21/R23p_2C8") (pintype "passive"))
    )
    (net (code "9") (name "/AUX_IO_6") (class "Default")
      (node (ref "P6") (pin "8") (pinfunction "8_8") (pintype "passive"))
      (node (ref "P8") (pin "30") (pinfunction "30_30") (pintype "passive"))
      (node (ref "U11") (pin "2C9") (pinfunction "E22/R8n_2C9") (pintype "passive"))
    )
    (net (code "10") (name "/AUX_IO_7") (class "Default")
      (node (ref "P6") (pin "9") (pinfunction "9_9") (pintype "passive"))
      (node (ref "P8") (pin "29") (pinfunction "29_29") (pintype "passive"))
      (node (ref "U11") (pin "2C10") (pinfunction "P22/R23n_2C10") (pintype "passive"))
    )
    (net (code "11") (name "/AUX_IO_8") (class "Default")
      (node (ref "P6") (pin "10") (pinfunction "10_10") (pintype "passive"))
      (node (ref "P8") (pin "28") (pinfunction "28_28") (pintype "passive"))
      (node (ref "U11") (pin "2C11") (pinfunction "F19/R6p_2C11") (pintype "passive"))
    )
    (net (code "12") (name "/AUX_IO_9") (class "Default")
      (node (ref "P6") (pin "11") (pinfunction "11_11") (pintype "passive"))
      (node (ref "P8") (pin "27") (pinfunction "27_27") (pintype "passive"))
      (node (ref "U11") (pin "2C12") (pinfunction "U16/B40p_2C12") (pintype "passive"))
    )
    (net (code "13") (name "/AUX_IO_10") (class "Default")
      (node (ref "P6") (pin "12") (pinfunction "12_12") (pintype "passive"))
      (node (ref "P8") (pin "26") (pinfunction "26_26") (pintype "passive"))
      (node (ref "U11") (pin "2C13") (pinfunction "F20/R6n_2C13") (pintype "passive"))
    )
    (net (code "14") (name "/AUX_IO_11") (class "Default")
      (node (ref "P6") (pin "13") (pinfunction "13_13") (pintype "passive"))
      (node (ref "P8") (pin "25") (pinfunction "25_25") (pintype "passive"))
      (node (ref "U11") (pin "2C14") (pinfunction "U17/B40n_2C14") (pintype "passive"))
    )
    (net (code "15") (name "/AUX_IO_12") (class "Default")
      (node (ref "P6") (pin "14") (pinfunction "14_14") (pintype "passive"))
      (node (ref "P8") (pin "24") (pinfunction "24_24") (pintype "passive"))
      (node (ref "U11") (pin "2C15") (pinfunction "D21/R7p_2C15") (pintype "passive"))
    )
    (net (code "16") (name "/AUX_IO_13") (class "Default")
      (node (ref "P6") (pin "15") (pinfunction "15_15") (pintype "passive"))
      (node (ref "P8") (pin "23") (pinfunction "23_23") (pintype "passive"))
      (node (ref "U11") (pin "2C16") (pinfunction "T14/B36p_2C16") (pintype "passive"))
    )
    (net (code "17") (name "/AUX_IO_14") (class "Default")
      (node (ref "P6") (pin "16") (pinfunction "16_16") (pintype "passive"))
      (node (ref "P8") (pin "22") (pinfunction "22_22") (pintype "passive"))
      (node (ref "U11") (pin "2C17") (pinfunction "D22/R7n_2C17") (pintype "passive"))
    )
    (net (code "18") (name "/AUX_IO_15") (class "Default")
      (node (ref "P6") (pin "17") (pinfunction "17_17") (pintype "passive"))
      (node (ref "P8") (pin "21") (pinfunction "21_21") (pintype "passive"))
      (node (ref "U11") (pin "2C18") (pinfunction "T15/B36n_2C18") (pintype "passive"))
    )
    (net (code "19") (name "/AUX_IO_16") (class "Default")
      (node (ref "P6") (pin "18") (pinfunction "18_18") (pintype "passive"))
      (node (ref "P8") (pin "20") (pinfunction "20_20") (pintype "passive"))
      (node (ref "U11") (pin "2C19") (pinfunction "C21/R4p_2C19") (pintype "passive"))
    )
    (net (code "20") (name "/AUX_IO_17") (class "Default")
      (node (ref "P6") (pin "19") (pinfunction "19_19") (pintype "passive"))
      (node (ref "P8") (pin "19") (pinfunction "19_19") (pintype "passive"))
      (node (ref "U11") (pin "2C20") (pinfunction "N19/R22p_2C20") (pintype "passive"))
    )
    (net (code "21") (name "/LED_0") (class "Default")
      (node (ref "D1") (pin "1") (pinfunction "A_1") (pintype "passive"))
      (node (ref "U11") (pin "1C4") (pinfunction "AA9/B18p_1C4") (pintype "passive"))
    )
    (net (code "22") (name "/LED_1") (class "Default")
      (node (ref "D3") (pin "1") (pinfunction "A_1") (pintype "passive"))
      (node (ref "U11") (pin "1C5") (pinfunction "R3/L27n_1C5") (pintype "passive"))
    )
    (net (code "23") (name "/LED_2") (class "Default")
      (node (ref "D5") (pin "1") (pinfunction "A_1") (pintype "passive"))
      (node (ref "U11") (pin "1C6") (pinfunction "AB9/B19n_1C6") (pintype "passive"))
    )
    (net (code "24") (name "/LED_3") (class "Default")
      (node (ref "D7") (pin "1") (pinfunction "A_1") (pintype "passive"))
      (node (ref "U11") (pin "1C7") (pinfunction "W2/L28p_1C7") (pintype "passive"))
    )
    (net (code "25") (name "/LED_4") (class "Default")
      (node (ref "D2") (pin "1") (pinfunction "A_1") (pintype "passive"))
      (node (ref "U11") (pin "1C8") (pinfunction "W10/B20p_1C8") (pintype "passive"))
    )
    (net (code "26") (name "/LED_5") (class "Default")
      (node (ref "D4") (pin "1") (pinfunction "A_1") (pintype "passive"))
      (node (ref "U11") (pin "1C9") (pinfunction "W1/L28n_1C9") (pintype "passive"))
    )
    (net (code "27") (name "/LED_6") (class "Default")
      (node (ref "D6") (pin "1") (pinfunction "A_1") (pintype "passive"))
      (node (ref "U11") (pin "1C10") (pinfunction "Y10/B20n_1C10") (pintype "passive"))
    )
    (net (code "28") (name "/LED_7") (class "Default")
      (node (ref "D8") (pin "1") (pinfunction "A_1") (pintype "passive"))
      (node (ref "U11") (pin "1C11") (pinfunction "Y2/L29p_1C11") (pintype "passive"))
    )
    (net (code "29") (name "/PMT_IN") (class "Default")
      (node (ref "P9") (pin "36") (pinfunction "36_36") (pintype "passive"))
      (node (ref "U11") (pin "1C16") (pinfunction "AA10/B21p_1C16") (pintype "passive"))
      (node (ref "U13") (pin "4") (pinfunction "B_4") (pintype "passive"))
    )
    (net (code "30") (name "/TRIGGER_IN") (class "Default")
      (node (ref "P9") (pin "34") (pinfunction "34_34") (pintype "passive"))
      (node (ref "U11") (pin "1C18") (pinfunction "AB10/B21n_1C18") (pintype "passive"))
      (node (ref "U14") (pin "4") (pinfunction "B_4") (pintype "passive"))
    )
    (net (code "31") (name "/TTL_OUT_0") (class "Default")
      (node (ref "P5") (pin "2") (pinfunction "2_2") (pintype "passive"))
      (node (ref "U11") (pin "2B3") (pinfunction "H17/R5p_2B3") (pintype "passive"))
    )
    (net (code "32") (name "/TTL_OUT_1") (class "Default")
      (node (ref "P5") (pin "3") (pinfunction "3_3") (pintype "passive"))
      (node (ref "U11") (pin "2B4") (pinfunction "AA14/B25p_2B4") (pintype "passive"))
    )
    (net (code "33") (name "/TTL_OUT_2") (class "Default")
      (node (ref "P10") (pin "36") (pinfunction "36_36") (pintype "passive"))
      (node (ref "P5") (pin "4") (pinfunction "4_4") (pintype "passive"))
      (node (ref "U11") (pin "2B5") (pinfunction "G18/R5n_2B5") (pintype "passive"))
    )
    (net (code "34") (name "/TTL_OUT_3") (class "Default")
      (node (ref "P10") (pin "35") (pinfunction "35_35") (pintype "passive"))
      (node (ref "P5") (pin "5") (pinfunction "5_5") (pintype "passive"))
      (node (ref "U11") (pin "2B6") (pinfunction "AB14/B25n_2B6") (pintype "passive"))
    )
    (net (code "35") (name "/TTL_OUT_4") (class "Default")
      (node (ref "P10") (pin "34") (pinfunction "34_34") (pintype "passive"))
      (node (ref "P5") (pin "6") (pinfunction "6_6") (pintype "passive"))
      (node (ref "U11") (pin "2B7") (pinfunction "K18/R13p_2B7") (pintype "passive"))
    )
    (net (code "36") (name "/TTL_OUT_5") (class "Default")
      (node (ref "P10") (pin "33") (pinfunction "33_33") (pintype "passive"))
      (node (ref "P5") (pin "7") (pinfunction "7_7") (pintype "passive"))
      (node (ref "U11") (pin "2B8") (pinfunction "W13/B26p_2B8") (pintype "passive"))
    )
    (net (code "37") (name "/TTL_OUT_6") (class "Default")
      (node (ref "P10") (pin "32") (pinfunction "32_32") (pintype "passive"))
      (node (ref "P5") (pin "8") (pinfunction "8_8") (pintype "passive"))
      (node (ref "U11") (pin "2B9") (pinfunction "K17/R13n_2B9") (pintype "passive"))
    )
    (net (code "38") (name "/TTL_OUT_7") (class "Default")
      (node (ref "P10") (pin "31") (pinfunction "31_31") (pintype "passive"))
      (node (ref "P5") (pin "9") (pinfunction "9_9") (pintype "passive"))
      (node (ref "U11") (pin "2B10") (pinfunction "Y13/B26n_2B10") (pintype "passive"))
    )
    (net (code "39") (name "/TTL_OUT_8") (class "Default")
      (node (ref "P10") (pin "30") (pinfunction "30_30") (pintype "passive"))
      (node (ref "P5") (pin "10") (pinfunction "10_10") (pintype "passive"))
      (node (ref "U11") (pin "2B11") (pinfunction "M19/R18p_2B11") (pintype "passive"))
    )
    (net (code "40") (name "/TTL_OUT_9") (class "Default")
      (node (ref "P10") (pin "29") (pinfunction "29_29") (pintype "passive"))
      (node (ref "P5") (pin "11") (pinfunction "11_11") (pintype "passive"))
      (node (ref "U11") (pin "2B12") (pinfunction "AA15/B27p_2B12") (pintype "passive"))
    )
    (net (code "41") (name "/TTL_OUT_10") (class "Default")
      (node (ref "P10") (pin "28") (pinfunction "28_28") (pintype "passive"))
      (node (ref "P5") (pin "12") (pinfunction "12_12") (pintype "passive"))
      (node (ref "U11") (pin "2B13") (pinfunction "M20/R18n_2B13") (pintype "passive"))
    )
    (net (code "42") (name "/TTL_OUT_11") (class "Default")
      (node (ref "P10") (pin "27") (pinfunction "27_27") (pintype "passive"))
      (node (ref "P5") (pin "13") (pinfunction "13_13") (pintype "passive"))
      (node (ref "U11") (pin "2B14") (pinfunction "AB15/B27n_2B14") (pintype "passive"))
    )
    (net (code "43") (name "/TTL_OUT_12") (class "Default")
      (node (ref "P10") (pin "26") (pinfunction "26_26") (pintype "passive"))
      (node (ref "P5") (pin "14") (pinfunction "14_14") (pintype "passive"))
      (node (ref "U11") (pin "2B15") (pinfunction "N21/R20p_2B15") (pintype "passive"))
    )
    (net (code "44") (name "/TTL_OUT_13") (class "Default")
      (node (ref "P10") (pin "25") (pinfunction "25_25") (pintype "passive"))
      (node (ref "P5") (pin "15") (pinfunction "15_15") (pintype "passive"))
      (node (ref "U11") (pin "2B16") (pinfunction "AA16/B30p_2B16") (pintype "passive"))
    )
    (net (code "45") (name "/TTL_OUT_14") (class "Default")
      (node (ref "P10") (pin "24") (pinfunction "24_24") (pintype "passive"))
      (node (ref "P5") (pin "16") (pinfunction "16_16") (pintype "passive"))
      (node (ref "U11") (pin "2B17") (pinfunction "N22/R20n_2B17") (pintype "passive"))
    )
    (net (code "46") (name "/TTL_OUT_15") (class "Default")
      (node (ref "P10") (pin "23") (pinfunction "23_23") (pintype "passive"))
      (node (ref "P5") (pin "17") (pinfunction "17_17") (pintype "passive"))
      (node (ref "U11") (pin "2B18") (pinfunction "AB16/B30n_2B18") (pintype "passive"))
    )
    (net (code "47") (name "/TTL_OUT_16") (class "Default")
      (node (ref "P10") (pin "22") (pinfunction "22_22") (pintype "passive"))
      (node (ref "P5") (pin "18") (pinfunction "18_18") (pintype "passive"))
      (node (ref "U11") (pin "2B19") (pinfunction "H19/R9p_2B19") (pintype "passive"))
    )
    (net (code "48") (name "/TTL_OUT_17") (class "Default")
      (node (ref "P10") (pin "21") (pinfunction "21_21") (pintype "passive"))
      (node (ref "P5") (pin "19") (pinfunction "19_19") (pintype "passive"))
      (node (ref "U11") (pin "2B20") (pinfunction "AA17/B37p_2B20") (pintype "passive"))
    )
    (net (code "49") (name "/TTL_OUT_18") (class "Default")
      (node (ref "P10") (pin "20") (pinfunction "20_20") (pintype "passive"))
      (node (ref "P5") (pin "20") (pinfunction "20_20") (pintype "passive"))
      (node (ref "U11") (pin "2B21") (pinfunction "H20/R9n_2B21") (pintype "passive"))
    )
    (net (code "50") (name "/TTL_OUT_19") (class "Default")
      (node (ref "P10") (pin "19") (pinfunction "19_19") (pintype "passive"))
      (node (ref "P5") (pin "21") (pinfunction "21_21") (pintype "passive"))
      (node (ref "U11") (pin "2B22") (pinfunction "AB17/B37n_2B22") (pintype "passive"))
    )
    (net (code "51") (name "/TTL_OUT_20") (class "Default")
      (node (ref "P10") (pin "18") (pinfunction "18_18") (pintype "passive"))
      (node (ref "P5") (pin "22") (pinfunction "22_22") (pintype "passive"))
      (node (ref "U11") (pin "2B23") (pinfunction "M21/R19p_2B23") (pintype "passive"))
    )
    (net (code "52") (name "/TTL_OUT_21") (class "Default")
      (node (ref "P10") (pin "17") (pinfunction "17_17") (pintype "passive"))
      (node (ref "P5") (pin "23") (pinfunction "23_23") (pintype "passive"))
      (node (ref "U11") (pin "2B24") (pinfunction "AA20/B39p_2B24") (pintype "passive"))
    )
    (net (code "53") (name "/TTL_OUT_22") (class "Default")
      (node (ref "P10") (pin "14") (pinfunction "14_14") (pintype "passive"))
      (node (ref "P5") (pin "24") (pinfunction "24_24") (pintype "passive"))
      (node (ref "U11") (pin "2B25") (pinfunction "M22/R19n_2B25") (pintype "passive"))
    )
    (net (code "54") (name "/TTL_OUT_23") (class "Default")
      (node (ref "P10") (pin "13") (pinfunction "13_13") (pintype "passive"))
      (node (ref "P5") (pin "25") (pinfunction "25_25") (pintype "passive"))
      (node (ref "U11") (pin "2B26") (pinfunction "AB20/B39n_2B26") (pintype "passive"))
    )
    (net (code "55") (name "/TTL_OUT_24") (class "Default")
      (node (ref "P10") (pin "12") (pinfunction "12_12") (pintype "passive"))
      (node (ref "P5") (pin "26") (pinfunction "26_26") (pintype "passive"))
      (node (ref "U11") (pin "2B27") (pinfunction "J21/R15p_2B27") (pintype "passive"))
    )
    (net (code "56") (name "/TTL_OUT_25") (class "Default")
      (node (ref "P10") (pin "11") (pinfunction "11_11") (pintype "passive"))
      (node (ref "P5") (pin "27") (pinfunction "27_27") (pintype "passive"))
      (node (ref "U11") (pin "2B28") (pinfunction "Y14/B29p_2B28") (pintype "passive"))
    )
    (net (code "57") (name "/TTL_OUT_26") (class "Default")
      (node (ref "P10") (pin "10") (pinfunction "10_10") (pintype "passive"))
      (node (ref "P5") (pin "28") (pinfunction "28_28") (pintype "passive"))
      (node (ref "U11") (pin "2B29") (pinfunction "J22/R15n_2B29") (pintype "passive"))
    )
    (net (code "58") (name "/TTL_OUT_27") (class "Default")
      (node (ref "P10") (pin "9") (pinfunction "9_9") (pintype "passive"))
      (node (ref "P5") (pin "29") (pinfunction "29_29") (pintype "passive"))
      (node (ref "U11") (pin "2B30") (pinfunction "Y15/B29n_2B30") (pintype "passive"))
    )
    (net (code "59") (name "/TTL_OUT_28") (class "Default")
      (node (ref "P10") (pin "8") (pinfunction "8_8") (pintype "passive"))
      (node (ref "P5") (pin "30") (pinfunction "30_30") (pintype "passive"))
      (node (ref "U11") (pin "2B31") (pinfunction "R21/R24p_2B31") (pintype "passive"))
    )
    (net (code "60") (name "/TTL_OUT_29") (class "Default")
      (node (ref "P10") (pin "7") (pinfunction "7_7") (pintype "passive"))
      (node (ref "P5") (pin "31") (pinfunction "31_31") (pintype "passive"))
      (node (ref "U11") (pin "2B32") (pinfunction "L21/R17p_2B32") (pintype "passive"))
    )
    (net (code "61") (name "/TTL_OUT_30") (class "Default")
      (node (ref "P10") (pin "6") (pinfunction "6_6") (pintype "passive"))
      (node (ref "P5") (pin "32") (pinfunction "32_32") (pintype "passive"))
      (node (ref "U11") (pin "2B33") (pinfunction "R22/R24n_2B33") (pintype "passive"))
    )
    (net (code "62") (name "/TTL_OUT_31") (class "Default")
      (node (ref "P10") (pin "5") (pinfunction "5_5") (pintype "passive"))
      (node (ref "P5") (pin "33") (pinfunction "33_33") (pintype "passive"))
      (node (ref "U11") (pin "2B34") (pinfunction "L22/R17n_2B34") (pintype "passive"))
    )
    (net (code "63") (name "/TTL_OUT_32") (class "Default")
      (node (ref "P10") (pin "4") (pinfunction "4_4") (pintype "passive"))
      (node (ref "P5") (pin "34") (pinfunction "34_34") (pintype "passive"))
      (node (ref "U11") (pin "2B35") (pinfunction "F21/R11p_2B35") (pintype "passive"))
    )
    (net (code "64") (name "/TTL_OUT_33") (class "Default")
      (node (ref "P10") (pin "3") (pinfunction "3_3") (pintype "passive"))
      (node (ref "P5") (pin "35") (pinfunction "35_35") (pintype "passive"))
      (node (ref "U11") (pin "2B36") (pinfunction "V14/B33p_2B36") (pintype "passive"))
    )
    (net (code "65") (name "/TTL_OUT_34") (class "Default")
      (node (ref "P10") (pin "2") (pinfunction "2_2") (pintype "passive"))
      (node (ref "P5") (pin "36") (pinfunction "36_36") (pintype "passive"))
      (node (ref "U11") (pin "2B37") (pinfunction "F22/R11n_2B37") (pintype "passive"))
    )
    (net (code "66") (name "/TTL_OUT_35") (class "Default")
      (node (ref "P10") (pin "1") (pinfunction "1_1") (pintype "passive"))
      (node (ref "P5") (pin "37") (pinfunction "37_37") (pintype "passive"))
      (node (ref "U11") (pin "2B38") (pinfunction "U14/B33n_2B38") (pintype "passive"))
    )
    (net (code "67") (name "/bus0") (class "Default")
      (node (ref "P9") (pin "24") (pinfunction "24_24") (pintype "passive"))
      (node (ref "U10") (pin "9") (pinfunction "DI3_9") (pintype "passive"))
      (node (ref "U11") (pin "1B29") (pinfunction "U1/L24n_1B29") (pintype "passive"))
    )
    (net (code "68") (name "/bus0_n") (class "Default")
      (node (ref "J1") (pin "52") (pinfunction "A52_52") (pintype "passive"))
      (node (ref "J10") (pin "52") (pinfunction "A52_52") (pintype "passive"))
      (node (ref "J11") (pin "52") (pinfunction "A52_52") (pintype "passive"))
      (node (ref "J12") (pin "52") (pinfunction "A52_52") (pintype "passive"))
      (node (ref "J13") (pin "52") (pinfunction "A52_52") (pintype "passive"))
      (node (ref "J14") (pin "52") (pinfunction "A52_52") (pintype "passive"))
      (node (ref "J15") (pin "52") (pinfunction "A52_52") (pintype "passive"))
      (node (ref "J16") (pin "52") (pinfunction "A52_52") (pintype "passive"))
      (node (ref "J2") (pin "52") (pinfunction "A52_52") (pintype "passive"))
      (node (ref "J3") (pin "52") (pinfunction "A52_52") (pintype "passive"))
      (node (ref "J4") (pin "52") (pinfunction "A52_52") (pintype "passive"))
      (node (ref "J5") (pin "52") (pinfunction "A52_52") (pintype "passive"))
      (node (ref "J6") (pin "52") (pinfunction "A52_52") (pintype "passive"))
      (node (ref "J7") (pin "52") (pinfunction "A52_52") (pintype "passive"))
      (node (ref "J8") (pin "52") (pinfunction "A52_52") (pintype "passive"))
      (node (ref "J9") (pin "52") (pinfunction "A52_52") (pintype "passive"))
      (node (ref "R1") (pin "1") (pinfunction "1_1") (pintype "passive"))
      (node (ref "U10") (pin "10") (pinfunction "DO3+_10") (pintype "passive"))
    )
    (net (code "69") (name "/bus0_p") (class "Default")
      (node (ref "J1") (pin "51") (pinfunction "A51_51") (pintype "passive"))
      (node (ref "J10") (pin "51") (pinfunction "A51_51") (pintype "passive"))
      (node (ref "J11") (pin "51") (pinfunction "A51_51") (pintype "passive"))
      (node (ref "J12") (pin "51") (pinfunction "A51_51") (pintype "passive"))
      (node (ref "J13") (pin "51") (pinfunction "A51_51") (pintype "passive"))
      (node (ref "J14") (pin "51") (pinfunction "A51_51") (pintype "passive"))
      (node (ref "J15") (pin "51") (pinfunction "A51_51") (pintype "passive"))
      (node (ref "J16") (pin "51") (pinfunction "A51_51") (pintype "passive"))
      (node (ref "J2") (pin "51") (pinfunction "A51_51") (pintype "passive"))
      (node (ref "J3") (pin "51") (pinfunction "A51_51") (pintype "passive"))
      (node (ref "J4") (pin "51") (pinfunction "A51_51") (pintype "passive"))
      (node (ref "J5") (pin "51") (pinfunction "A51_51") (pintype "passive"))
      (node (ref "J6") (pin "51") (pinfunction "A51_51") (pintype "passive"))
      (node (ref "J7") (pin "51") (pinfunction "A51_51") (pintype "passive"))
      (node (ref "J8") (pin "51") (pinfunction "A51_51") (pintype "passive"))
      (node (ref "J9") (pin "51") (pinfunction "A51_51") (pintype "passive"))
      (node (ref "R1") (pin "2") (pinfunction "2_2") (pintype "passive"))
      (node (ref "U10") (pin "11") (pinfunction "DO3-_11") (pintype "passive"))
    )
    (net (code "70") (name "/bus1") (class "Default")
      (node (ref "P9") (pin "23") (pinfunction "23_23") (pintype "passive"))
      (node (ref "U10") (pin "15") (pinfunction "DI4_15") (pintype "passive"))
      (node (ref "U11") (pin "1B28") (pinfunction "AA8/B17p_1B28") (pintype "passive"))
    )
    (net (code "71") (name "/bus1_n") (class "Default")
      (node (ref "J1") (pin "49") (pinfunction "A49_49") (pintype "passive"))
      (node (ref "J10") (pin "49") (pinfunction "A49_49") (pintype "passive"))
      (node (ref "J11") (pin "49") (pinfunction "A49_49") (pintype "passive"))
      (node (ref "J12") (pin "49") (pinfunction "A49_49") (pintype "passive"))
      (node (ref "J13") (pin "49") (pinfunction "A49_49") (pintype "passive"))
      (node (ref "J14") (pin "49") (pinfunction "A49_49") (pintype "passive"))
      (node (ref "J15") (pin "49") (pinfunction "A49_49") (pintype "passive"))
      (node (ref "J16") (pin "49") (pinfunction "A49_49") (pintype "passive"))
      (node (ref "J2") (pin "49") (pinfunction "A49_49") (pintype "passive"))
      (node (ref "J3") (pin "49") (pinfunction "A49_49") (pintype "passive"))
      (node (ref "J4") (pin "49") (pinfunction "A49_49") (pintype "passive"))
      (node (ref "J5") (pin "49") (pinfunction "A49_49") (pintype "passive"))
      (node (ref "J6") (pin "49") (pinfunction "A49_49") (pintype "passive"))
      (node (ref "J7") (pin "49") (pinfunction "A49_49") (pintype "passive"))
      (node (ref "J8") (pin "49") (pinfunction "A49_49") (pintype "passive"))
      (node (ref "J9") (pin "49") (pinfunction "A49_49") (pintype "passive"))
      (node (ref "R2") (pin "1") (pinfunction "1_1") (pintype "passive"))
      (node (ref "U10") (pin "14") (pinfunction "DO4+_14") (pintype "passive"))
    )
    (net (code "72") (name "/bus1_p") (class "Default")
      (node (ref "J1") (pin "50") (pinfunction "A50_50") (pintype "passive"))
      (node (ref "J10") (pin "50") (pinfunction "A50_50") (pintype "passive"))
      (node (ref "J11") (pin "50") (pinfunction "A50_50") (pintype "passive"))
      (node (ref "J12") (pin "50") (pinfunction "A50_50") (pintype "passive"))
      (node (ref "J13") (pin "50") (pinfunction "A50_50") (pintype "passive"))
      (node (ref "J14") (pin "50") (pinfunction "A50_50") (pintype "passive"))
      (node (ref "J15") (pin "50") (pinfunction "A50_50") (pintype "passive"))
      (node (ref "J16") (pin "50") (pinfunction "A50_50") (pintype "passive"))
      (node (ref "J2") (pin "50") (pinfunction "A50_50") (pintype "passive"))
      (node (ref "J3") (pin "50") (pinfunction "A50_50") (pintype "passive"))
      (node (ref "J4") (pin "50") (pinfunction "A50_50") (pintype "passive"))
      (node (ref "J5") (pin "50") (pinfunction "A50_50") (pintype "passive"))
      (node (ref "J6") (pin "50") (pinfunction "A50_50") (pintype "passive"))
      (node (ref "J7") (pin "50") (pinfunction "A50_50") (pintype "passive"))
      (node (ref "J8") (pin "50") (pinfunction "A50_50") (pintype "passive"))
      (node (ref "J9") (pin "50") (pinfunction "A50_50") (pintype "passive"))
      (node (ref "R2") (pin "2") (pinfunction "2_2") (pintype "passive"))
      (node (ref "U10") (pin "13") (pinfunction "DO4-_13") (pintype "passive"))
    )
    (net (code "73") (name "/bus2") (class "Default")
      (node (ref "P9") (pin "26") (pinfunction "26_26") (pintype "passive"))
      (node (ref "U10") (pin "1") (pinfunction "DI1_1") (pintype "passive"))
      (node (ref "U11") (pin "1B31") (pinfunction "R19/R26p_1B31") (pintype "passive"))
    )
    (net (code "74") (name "/bus2_n") (class "Default")
      (node (ref "J1") (pin "56") (pinfunction "A56_56") (pintype "passive"))
      (node (ref "J10") (pin "56") (pinfunction "A56_56") (pintype "passive"))
      (node (ref "J11") (pin "56") (pinfunction "A56_56") (pintype "passive"))
      (node (ref "J12") (pin "56") (pinfunction "A56_56") (pintype "passive"))
      (node (ref "J13") (pin "56") (pinfunction "A56_56") (pintype "passive"))
      (node (ref "J14") (pin "56") (pinfunction "A56_56") (pintype "passive"))
      (node (ref "J15") (pin "56") (pinfunction "A56_56") (pintype "passive"))
      (node (ref "J16") (pin "56") (pinfunction "A56_56") (pintype "passive"))
      (node (ref "J2") (pin "56") (pinfunction "A56_56") (pintype "passive"))
      (node (ref "J3") (pin "56") (pinfunction "A56_56") (pintype "passive"))
      (node (ref "J4") (pin "56") (pinfunction "A56_56") (pintype "passive"))
      (node (ref "J5") (pin "56") (pinfunction "A56_56") (pintype "passive"))
      (node (ref "J6") (pin "56") (pinfunction "A56_56") (pintype "passive"))
      (node (ref "J7") (pin "56") (pinfunction "A56_56") (pintype "passive"))
      (node (ref "J8") (pin "56") (pinfunction "A56_56") (pintype "passive"))
      (node (ref "J9") (pin "56") (pinfunction "A56_56") (pintype "passive"))
      (node (ref "R3") (pin "1") (pinfunction "1_1") (pintype "passive"))
      (node (ref "U10") (pin "2") (pinfunction "DO1+_2") (pintype "passive"))
    )
    (net (code "75") (name "/bus2_p") (class "Default")
      (node (ref "J1") (pin "55") (pinfunction "A55_55") (pintype "passive"))
      (node (ref "J10") (pin "55") (pinfunction "A55_55") (pintype "passive"))
      (node (ref "J11") (pin "55") (pinfunction "A55_55") (pintype "passive"))
      (node (ref "J12") (pin "55") (pinfunction "A55_55") (pintype "passive"))
      (node (ref "J13") (pin "55") (pinfunction "A55_55") (pintype "passive"))
      (node (ref "J14") (pin "55") (pinfunction "A55_55") (pintype "passive"))
      (node (ref "J15") (pin "55") (pinfunction "A55_55") (pintype "passive"))
      (node (ref "J16") (pin "55") (pinfunction "A55_55") (pintype "passive"))
      (node (ref "J2") (pin "55") (pinfunction "A55_55") (pintype "passive"))
      (node (ref "J3") (pin "55") (pinfunction "A55_55") (pintype "passive"))
      (node (ref "J4") (pin "55") (pinfunction "A55_55") (pintype "passive"))
      (node (ref "J5") (pin "55") (pinfunction "A55_55") (pintype "passive"))
      (node (ref "J6") (pin "55") (pinfunction "A55_55") (pintype "passive"))
      (node (ref "J7") (pin "55") (pinfunction "A55_55") (pintype "passive"))
      (node (ref "J8") (pin "55") (pinfunction "A55_55") (pintype "passive"))
      (node (ref "J9") (pin "55") (pinfunction "A55_55") (pintype "passive"))
      (node (ref "R3") (pin "2") (pinfunction "2_2") (pintype "passive"))
      (node (ref "U10") (pin "3") (pinfunction "DO1-_3") (pintype "passive"))
    )
    (net (code "76") (name "/bus3") (class "Default")
      (node (ref "P9") (pin "25") (pinfunction "25_25") (pintype "passive"))
      (node (ref "U10") (pin "7") (pinfunction "DI2_7") (pintype "passive"))
      (node (ref "U11") (pin "1B30") (pinfunction "AB8/B17n_1B30") (pintype "passive"))
    )
    (net (code "77") (name "/bus3_n") (class "Default")
      (node (ref "J1") (pin "53") (pinfunction "A53_53") (pintype "passive"))
      (node (ref "J10") (pin "53") (pinfunction "A53_53") (pintype "passive"))
      (node (ref "J11") (pin "53") (pinfunction "A53_53") (pintype "passive"))
      (node (ref "J12") (pin "53") (pinfunction "A53_53") (pintype "passive"))
      (node (ref "J13") (pin "53") (pinfunction "A53_53") (pintype "passive"))
      (node (ref "J14") (pin "53") (pinfunction "A53_53") (pintype "passive"))
      (node (ref "J15") (pin "53") (pinfunction "A53_53") (pintype "passive"))
      (node (ref "J16") (pin "53") (pinfunction "A53_53") (pintype "passive"))
      (node (ref "J2") (pin "53") (pinfunction "A53_53") (pintype "passive"))
      (node (ref "J3") (pin "53") (pinfunction "A53_53") (pintype "passive"))
      (node (ref "J4") (pin "53") (pinfunction "A53_53") (pintype "passive"))
      (node (ref "J5") (pin "53") (pinfunction "A53_53") (pintype "passive"))
      (node (ref "J6") (pin "53") (pinfunction "A53_53") (pintype "passive"))
      (node (ref "J7") (pin "53") (pinfunction "A53_53") (pintype "passive"))
      (node (ref "J8") (pin "53") (pinfunction "A53_53") (pintype "passive"))
      (node (ref "J9") (pin "53") (pinfunction "A53_53") (pintype "passive"))
      (node (ref "R4") (pin "1") (pinfunction "1_1") (pintype "passive"))
      (node (ref "U10") (pin "6") (pinfunction "DO2+_6") (pintype "passive"))
    )
    (net (code "78") (name "/bus3_p") (class "Default")
      (node (ref "J1") (pin "54") (pinfunction "A54_54") (pintype "passive"))
      (node (ref "J10") (pin "54") (pinfunction "A54_54") (pintype "passive"))
      (node (ref "J11") (pin "54") (pinfunction "A54_54") (pintype "passive"))
      (node (ref "J12") (pin "54") (pinfunction "A54_54") (pintype "passive"))
      (node (ref "J13") (pin "54") (pinfunction "A54_54") (pintype "passive"))
      (node (ref "J14") (pin "54") (pinfunction "A54_54") (pintype "passive"))
      (node (ref "J15") (pin "54") (pinfunction "A54_54") (pintype "passive"))
      (node (ref "J16") (pin "54") (pinfunction "A54_54") (pintype "passive"))
      (node (ref "J2") (pin "54") (pinfunction "A54_54") (pintype "passive"))
      (node (ref "J3") (pin "54") (pinfunction "A54_54") (pintype "passive"))
      (node (ref "J4") (pin "54") (pinfunction "A54_54") (pintype "passive"))
      (node (ref "J5") (pin "54") (pinfunction "A54_54") (pintype "passive"))
      (node (ref "J6") (pin "54") (pinfunction "A54_54") (pintype "passive"))
      (node (ref "J7") (pin "54") (pinfunction "A54_54") (pintype "passive"))
      (node (ref "J8") (pin "54") (pinfunction "A54_54") (pintype "passive"))
      (node (ref "J9") (pin "54") (pinfunction "A54_54") (pintype "passive"))
      (node (ref "R4") (pin "2") (pinfunction "2_2") (pintype "passive"))
      (node (ref "U10") (pin "5") (pinfunction "DO2-_5") (pintype "passive"))
    )
    (net (code "79") (name "/bus4") (class "Default")
      (node (ref "P9") (pin "20") (pinfunction "20_20") (pintype "passive"))
      (node (ref "U11") (pin "1B25") (pinfunction "P3/L23n_1B25") (pintype "passive"))
      (node (ref "U9") (pin "9") (pinfunction "DI3_9") (pintype "passive"))
    )
    (net (code "80") (name "/bus4_n") (class "Default")
      (node (ref "J1") (pin "43") (pinfunction "A43_43") (pintype "passive"))
      (node (ref "J10") (pin "43") (pinfunction "A43_43") (pintype "passive"))
      (node (ref "J11") (pin "43") (pinfunction "A43_43") (pintype "passive"))
      (node (ref "J12") (pin "43") (pinfunction "A43_43") (pintype "passive"))
      (node (ref "J13") (pin "43") (pinfunction "A43_43") (pintype "passive"))
      (node (ref "J14") (pin "43") (pinfunction "A43_43") (pintype "passive"))
      (node (ref "J15") (pin "43") (pinfunction "A43_43") (pintype "passive"))
      (node (ref "J16") (pin "43") (pinfunction "A43_43") (pintype "passive"))
      (node (ref "J2") (pin "43") (pinfunction "A43_43") (pintype "passive"))
      (node (ref "J3") (pin "43") (pinfunction "A43_43") (pintype "passive"))
      (node (ref "J4") (pin "43") (pinfunction "A43_43") (pintype "passive"))
      (node (ref "J5") (pin "43") (pinfunction "A43_43") (pintype "passive"))
      (node (ref "J6") (pin "43") (pinfunction "A43_43") (pintype "passive"))
      (node (ref "J7") (pin "43") (pinfunction "A43_43") (pintype "passive"))
      (node (ref "J8") (pin "43") (pinfunction "A43_43") (pintype "passive"))
      (node (ref "J9") (pin "43") (pinfunction "A43_43") (pintype "passive"))
      (node (ref "R5") (pin "1") (pinfunction "1_1") (pintype "passive"))
      (node (ref "U9") (pin "10") (pinfunction "DO3+_10") (pintype "passive"))
    )
    (net (code "81") (name "/bus4_p") (class "Default")
      (node (ref "J1") (pin "42") (pinfunction "A42_42") (pintype "passive"))
      (node (ref "J10") (pin "42") (pinfunction "A42_42") (pintype "passive"))
      (node (ref "J11") (pin "42") (pinfunction "A42_42") (pintype "passive"))
      (node (ref "J12") (pin "42") (pinfunction "A42_42") (pintype "passive"))
      (node (ref "J13") (pin "42") (pinfunction "A42_42") (pintype "passive"))
      (node (ref "J14") (pin "42") (pinfunction "A42_42") (pintype "passive"))
      (node (ref "J15") (pin "42") (pinfunction "A42_42") (pintype "passive"))
      (node (ref "J16") (pin "42") (pinfunction "A42_42") (pintype "passive"))
      (node (ref "J2") (pin "42") (pinfunction "A42_42") (pintype "passive"))
      (node (ref "J3") (pin "42") (pinfunction "A42_42") (pintype "passive"))
      (node (ref "J4") (pin "42") (pinfunction "A42_42") (pintype "passive"))
      (node (ref "J5") (pin "42") (pinfunction "A42_42") (pintype "passive"))
      (node (ref "J6") (pin "42") (pinfunction "A42_42") (pintype "passive"))
      (node (ref "J7") (pin "42") (pinfunction "A42_42") (pintype "passive"))
      (node (ref "J8") (pin "42") (pinfunction "A42_42") (pintype "passive"))
      (node (ref "J9") (pin "42") (pinfunction "A42_42") (pintype "passive"))
      (node (ref "R5") (pin "2") (pinfunction "2_2") (pintype "passive"))
      (node (ref "U9") (pin "11") (pinfunction "DO3-_11") (pintype "passive"))
    )
    (net (code "82") (name "/bus5") (class "Default")
      (node (ref "P9") (pin "19") (pinfunction "19_19") (pintype "passive"))
      (node (ref "U11") (pin "1B24") (pinfunction "AA7/B10p_1B24") (pintype "passive"))
      (node (ref "U9") (pin "15") (pinfunction "DI4_15") (pintype "passive"))
    )
    (net (code "83") (name "/bus5_n") (class "Default")
      (node (ref "J1") (pin "40") (pinfunction "A40_40") (pintype "passive"))
      (node (ref "J10") (pin "40") (pinfunction "A40_40") (pintype "passive"))
      (node (ref "J11") (pin "40") (pinfunction "A40_40") (pintype "passive"))
      (node (ref "J12") (pin "40") (pinfunction "A40_40") (pintype "passive"))
      (node (ref "J13") (pin "40") (pinfunction "A40_40") (pintype "passive"))
      (node (ref "J14") (pin "40") (pinfunction "A40_40") (pintype "passive"))
      (node (ref "J15") (pin "40") (pinfunction "A40_40") (pintype "passive"))
      (node (ref "J16") (pin "40") (pinfunction "A40_40") (pintype "passive"))
      (node (ref "J2") (pin "40") (pinfunction "A40_40") (pintype "passive"))
      (node (ref "J3") (pin "40") (pinfunction "A40_40") (pintype "passive"))
      (node (ref "J4") (pin "40") (pinfunction "A40_40") (pintype "passive"))
      (node (ref "J5") (pin "40") (pinfunction "A40_40") (pintype "passive"))
      (node (ref "J6") (pin "40") (pinfunction "A40_40") (pintype "passive"))
      (node (ref "J7") (pin "40") (pinfunction "A40_40") (pintype "passive"))
      (node (ref "J8") (pin "40") (pinfunction "A40_40") (pintype "passive"))
      (node (ref "J9") (pin "40") (pinfunction "A40_40") (pintype "passive"))
      (node (ref "R6") (pin "1") (pinfunction "1_1") (pintype "passive"))
      (node (ref "U9") (pin "14") (pinfunction "DO4+_14") (pintype "passive"))
    )
    (net (code "84") (name "/bus5_p") (class "Default")
      (node (ref "J1") (pin "41") (pinfunction "A41_41") (pintype "passive"))
      (node (ref "J10") (pin "41") (pinfunction "A41_41") (pintype "passive"))
      (node (ref "J11") (pin "41") (pinfunction "A41_41") (pintype "passive"))
      (node (ref "J12") (pin "41") (pinfunction "A41_41") (pintype "passive"))
      (node (ref "J13") (pin "41") (pinfunction "A41_41") (pintype "passive"))
      (node (ref "J14") (pin "41") (pinfunction "A41_41") (pintype "passive"))
      (node (ref "J15") (pin "41") (pinfunction "A41_41") (pintype "passive"))
      (node (ref "J16") (pin "41") (pinfunction "A41_41") (pintype "passive"))
      (node (ref "J2") (pin "41") (pinfunction "A41_41") (pintype "passive"))
      (node (ref "J3") (pin "41") (pinfunction "A41_41") (pintype "passive"))
      (node (ref "J4") (pin "41") (pinfunction "A41_41") (pintype "passive"))
      (node (ref "J5") (pin "41") (pinfunction "A41_41") (pintype "passive"))
      (node (ref "J6") (pin "41") (pinfunction "A41_41") (pintype "passive"))
      (node (ref "J7") (pin "41") (pinfunction "A41_41") (pintype "passive"))
      (node (ref "J8") (pin "41") (pinfunction "A41_41") (pintype "passive"))
      (node (ref "J9") (pin "41") (pinfunction "A41_41") (pintype "passive"))
      (node (ref "R6") (pin "2") (pinfunction "2_2") (pintype "passive"))
      (node (ref "U9") (pin "13") (pinfunction "DO4-_13") (pintype "passive"))
    )
    (net (code "85") (name "/bus6") (class "Default")
      (node (ref "P9") (pin "22") (pinfunction "22_22") (pintype "passive"))
      (node (ref "U11") (pin "1B27") (pinfunction "U2/L24p_1B27") (pintype "passive"))
      (node (ref "U9") (pin "1") (pinfunction "DI1_1") (pintype "passive"))
    )
    (net (code "86") (name "/bus6_n") (class "Default")
      (node (ref "J1") (pin "47") (pinfunction "A47_47") (pintype "passive"))
      (node (ref "J10") (pin "47") (pinfunction "A47_47") (pintype "passive"))
      (node (ref "J11") (pin "47") (pinfunction "A47_47") (pintype "passive"))
      (node (ref "J12") (pin "47") (pinfunction "A47_47") (pintype "passive"))
      (node (ref "J13") (pin "47") (pinfunction "A47_47") (pintype "passive"))
      (node (ref "J14") (pin "47") (pinfunction "A47_47") (pintype "passive"))
      (node (ref "J15") (pin "47") (pinfunction "A47_47") (pintype "passive"))
      (node (ref "J16") (pin "47") (pinfunction "A47_47") (pintype "passive"))
      (node (ref "J2") (pin "47") (pinfunction "A47_47") (pintype "passive"))
      (node (ref "J3") (pin "47") (pinfunction "A47_47") (pintype "passive"))
      (node (ref "J4") (pin "47") (pinfunction "A47_47") (pintype "passive"))
      (node (ref "J5") (pin "47") (pinfunction "A47_47") (pintype "passive"))
      (node (ref "J6") (pin "47") (pinfunction "A47_47") (pintype "passive"))
      (node (ref "J7") (pin "47") (pinfunction "A47_47") (pintype "passive"))
      (node (ref "J8") (pin "47") (pinfunction "A47_47") (pintype "passive"))
      (node (ref "J9") (pin "47") (pinfunction "A47_47") (pintype "passive"))
      (node (ref "R7") (pin "1") (pinfunction "1_1") (pintype "passive"))
      (node (ref "U9") (pin "2") (pinfunction "DO1+_2") (pintype "passive"))
    )
    (net (code "87") (name "/bus6_p") (class "Default")
      (node (ref "J1") (pin "46") (pinfunction "A46_46") (pintype "passive"))
      (node (ref "J10") (pin "46") (pinfunction "A46_46") (pintype "passive"))
      (node (ref "J11") (pin "46") (pinfunction "A46_46") (pintype "passive"))
      (node (ref "J12") (pin "46") (pinfunction "A46_46") (pintype "passive"))
      (node (ref "J13") (pin "46") (pinfunction "A46_46") (pintype "passive"))
      (node (ref "J14") (pin "46") (pinfunction "A46_46") (pintype "passive"))
      (node (ref "J15") (pin "46") (pinfunction "A46_46") (pintype "passive"))
      (node (ref "J16") (pin "46") (pinfunction "A46_46") (pintype "passive"))
      (node (ref "J2") (pin "46") (pinfunction "A46_46") (pintype "passive"))
      (node (ref "J3") (pin "46") (pinfunction "A46_46") (pintype "passive"))
      (node (ref "J4") (pin "46") (pinfunction "A46_46") (pintype "passive"))
      (node (ref "J5") (pin "46") (pinfunction "A46_46") (pintype "passive"))
      (node (ref "J6") (pin "46") (pinfunction "A46_46") (pintype "passive"))
      (node (ref "J7") (pin "46") (pinfunction "A46_46") (pintype "passive"))
      (node (ref "J8") (pin "46") (pinfunction "A46_46") (pintype "passive"))
      (node (ref "J9") (pin "46") (pinfunction "A46_46") (pintype "passive"))
      (node (ref "R7") (pin "2") (pinfunction "2_2") (pintype "passive"))
      (node (ref "U9") (pin "3") (pinfunction "DO1-_3") (pintype "passive"))
    )
    (net (code "88") (name "/bus7") (class "Default")
      (node (ref "P9") (pin "21") (pinfunction "21_21") (pintype "passive"))
      (node (ref "U11") (pin "1B26") (pinfunction "AB7/B10n_1B26") (pintype "passive"))
      (node (ref "U9") (pin "7") (pinfunction "DI2_7") (pintype "passive"))
    )
    (net (code "89") (name "/bus7_n") (class "Default")
      (node (ref "J1") (pin "44") (pinfunction "A44_44") (pintype "passive"))
      (node (ref "J10") (pin "44") (pinfunction "A44_44") (pintype "passive"))
      (node (ref "J11") (pin "44") (pinfunction "A44_44") (pintype "passive"))
      (node (ref "J12") (pin "44") (pinfunction "A44_44") (pintype "passive"))
      (node (ref "J13") (pin "44") (pinfunction "A44_44") (pintype "passive"))
      (node (ref "J14") (pin "44") (pinfunction "A44_44") (pintype "passive"))
      (node (ref "J15") (pin "44") (pinfunction "A44_44") (pintype "passive"))
      (node (ref "J16") (pin "44") (pinfunction "A44_44") (pintype "passive"))
      (node (ref "J2") (pin "44") (pinfunction "A44_44") (pintype "passive"))
      (node (ref "J3") (pin "44") (pinfunction "A44_44") (pintype "passive"))
      (node (ref "J4") (pin "44") (pinfunction "A44_44") (pintype "passive"))
      (node (ref "J5") (pin "44") (pinfunction "A44_44") (pintype "passive"))
      (node (ref "J6") (pin "44") (pinfunction "A44_44") (pintype "passive"))
      (node (ref "J7") (pin "44") (pinfunction "A44_44") (pintype "passive"))
      (node (ref "J8") (pin "44") (pinfunction "A44_44") (pintype "passive"))
      (node (ref "J9") (pin "44") (pinfunction "A44_44") (pintype "passive"))
      (node (ref "R8") (pin "1") (pinfunction "1_1") (pintype "passive"))
      (node (ref "U9") (pin "6") (pinfunction "DO2+_6") (pintype "passive"))
    )
    (net (code "90") (name "/bus7_p") (class "Default")
      (node (ref "J1") (pin "45") (pinfunction "A45_45") (pintype "passive"))
      (node (ref "J10") (pin "45") (pinfunction "A45_45") (pintype "passive"))
      (node (ref "J11") (pin "45") (pinfunction "A45_45") (pintype "passive"))
      (node (ref "J12") (pin "45") (pinfunction "A45_45") (pintype "passive"))
      (node (ref "J13") (pin "45") (pinfunction "A45_45") (pintype "passive"))
      (node (ref "J14") (pin "45") (pinfunction "A45_45") (pintype "passive"))
      (node (ref "J15") (pin "45") (pinfunction "A45_45") (pintype "passive"))
      (node (ref "J16") (pin "45") (pinfunction "A45_45") (pintype "passive"))
      (node (ref "J2") (pin "45") (pinfunction "A45_45") (pintype "passive"))
      (node (ref "J3") (pin "45") (pinfunction "A45_45") (pintype "passive"))
      (node (ref "J4") (pin "45") (pinfunction "A45_45") (pintype "passive"))
      (node (ref "J5") (pin "45") (pinfunction "A45_45") (pintype "passive"))
      (node (ref "J6") (pin "45") (pinfunction "A45_45") (pintype "passive"))
      (node (ref "J7") (pin "45") (pinfunction "A45_45") (pintype "passive"))
      (node (ref "J8") (pin "45") (pinfunction "A45_45") (pintype "passive"))
      (node (ref "J9") (pin "45") (pinfunction "A45_45") (pintype "passive"))
      (node (ref "R8") (pin "2") (pinfunction "2_2") (pintype "passive"))
      (node (ref "U9") (pin "5") (pinfunction "DO2-_5") (pintype "passive"))
    )
    (net (code "91") (name "/bus8") (class "Default")
      (node (ref "P9") (pin "14") (pinfunction "14_14") (pintype "passive"))
      (node (ref "U11") (pin "1B21") (pinfunction "R1/L21n_1B21") (pintype "passive"))
      (node (ref "U8") (pin "9") (pinfunction "DI3_9") (pintype "passive"))
    )
    (net (code "92") (name "/bus8_n") (class "Default")
      (node (ref "J1") (pin "34") (pinfunction "A34_34") (pintype "passive"))
      (node (ref "J10") (pin "34") (pinfunction "A34_34") (pintype "passive"))
      (node (ref "J11") (pin "34") (pinfunction "A34_34") (pintype "passive"))
      (node (ref "J12") (pin "34") (pinfunction "A34_34") (pintype "passive"))
      (node (ref "J13") (pin "34") (pinfunction "A34_34") (pintype "passive"))
      (node (ref "J14") (pin "34") (pinfunction "A34_34") (pintype "passive"))
      (node (ref "J15") (pin "34") (pinfunction "A34_34") (pintype "passive"))
      (node (ref "J16") (pin "34") (pinfunction "A34_34") (pintype "passive"))
      (node (ref "J2") (pin "34") (pinfunction "A34_34") (pintype "passive"))
      (node (ref "J3") (pin "34") (pinfunction "A34_34") (pintype "passive"))
      (node (ref "J4") (pin "34") (pinfunction "A34_34") (pintype "passive"))
      (node (ref "J5") (pin "34") (pinfunction "A34_34") (pintype "passive"))
      (node (ref "J6") (pin "34") (pinfunction "A34_34") (pintype "passive"))
      (node (ref "J7") (pin "34") (pinfunction "A34_34") (pintype "passive"))
      (node (ref "J8") (pin "34") (pinfunction "A34_34") (pintype "passive"))
      (node (ref "J9") (pin "34") (pinfunction "A34_34") (pintype "passive"))
      (node (ref "R9") (pin "1") (pinfunction "1_1") (pintype "passive"))
      (node (ref "U8") (pin "10") (pinfunction "DO3+_10") (pintype "passive"))
    )
    (net (code "93") (name "/bus8_p") (class "Default")
      (node (ref "J1") (pin "33") (pinfunction "A33_33") (pintype "passive"))
      (node (ref "J10") (pin "33") (pinfunction "A33_33") (pintype "passive"))
      (node (ref "J11") (pin "33") (pinfunction "A33_33") (pintype "passive"))
      (node (ref "J12") (pin "33") (pinfunction "A33_33") (pintype "passive"))
      (node (ref "J13") (pin "33") (pinfunction "A33_33") (pintype "passive"))
      (node (ref "J14") (pin "33") (pinfunction "A33_33") (pintype "passive"))
      (node (ref "J15") (pin "33") (pinfunction "A33_33") (pintype "passive"))
      (node (ref "J16") (pin "33") (pinfunction "A33_33") (pintype "passive"))
      (node (ref "J2") (pin "33") (pinfunction "A33_33") (pintype "passive"))
      (node (ref "J3") (pin "33") (pinfunction "A33_33") (pintype "passive"))
      (node (ref "J4") (pin "33") (pinfunction "A33_33") (pintype "passive"))
      (node (ref "J5") (pin "33") (pinfunction "A33_33") (pintype "passive"))
      (node (ref "J6") (pin "33") (pinfunction "A33_33") (pintype "passive"))
      (node (ref "J7") (pin "33") (pinfunction "A33_33") (pintype "passive"))
      (node (ref "J8") (pin "33") (pinfunction "A33_33") (pintype "passive"))
      (node (ref "J9") (pin "33") (pinfunction "A33_33") (pintype "passive"))
      (node (ref "R9") (pin "2") (pinfunction "2_2") (pintype "passive"))
      (node (ref "U8") (pin "11") (pinfunction "DO3-_11") (pintype "passive"))
    )
    (net (code "94") (name "/bus9") (class "Default")
      (node (ref "P9") (pin "13") (pinfunction "13_13") (pintype "passive"))
      (node (ref "U11") (pin "1B20") (pinfunction "W7/B7p_1B20") (pintype "passive"))
      (node (ref "U8") (pin "15") (pinfunction "DI4_15") (pintype "passive"))
    )
    (net (code "95") (name "/bus9_n") (class "Default")
      (node (ref "J1") (pin "31") (pinfunction "A31_31") (pintype "passive"))
      (node (ref "J10") (pin "31") (pinfunction "A31_31") (pintype "passive"))
      (node (ref "J11") (pin "31") (pinfunction "A31_31") (pintype "passive"))
      (node (ref "J12") (pin "31") (pinfunction "A31_31") (pintype "passive"))
      (node (ref "J13") (pin "31") (pinfunction "A31_31") (pintype "passive"))
      (node (ref "J14") (pin "31") (pinfunction "A31_31") (pintype "passive"))
      (node (ref "J15") (pin "31") (pinfunction "A31_31") (pintype "passive"))
      (node (ref "J16") (pin "31") (pinfunction "A31_31") (pintype "passive"))
      (node (ref "J2") (pin "31") (pinfunction "A31_31") (pintype "passive"))
      (node (ref "J3") (pin "31") (pinfunction "A31_31") (pintype "passive"))
      (node (ref "J4") (pin "31") (pinfunction "A31_31") (pintype "passive"))
      (node (ref "J5") (pin "31") (pinfunction "A31_31") (pintype "passive"))
      (node (ref "J6") (pin "31") (pinfunction "A31_31") (pintype "passive"))
      (node (ref "J7") (pin "31") (pinfunction "A31_31") (pintype "passive"))
      (node (ref "J8") (pin "31") (pinfunction "A31_31") (pintype "passive"))
      (node (ref "J9") (pin "31") (pinfunction "A31_31") (pintype "passive"))
      (node (ref "R10") (pin "1") (pinfunction "1_1") (pintype "passive"))
      (node (ref "U8") (pin "14") (pinfunction "DO4+_14") (pintype "passive"))
    )
    (net (code "96") (name "/bus9_p") (class "Default")
      (node (ref "J1") (pin "32") (pinfunction "A32_32") (pintype "passive"))
      (node (ref "J10") (pin "32") (pinfunction "A32_32") (pintype "passive"))
      (node (ref "J11") (pin "32") (pinfunction "A32_32") (pintype "passive"))
      (node (ref "J12") (pin "32") (pinfunction "A32_32") (pintype "passive"))
      (node (ref "J13") (pin "32") (pinfunction "A32_32") (pintype "passive"))
      (node (ref "J14") (pin "32") (pinfunction "A32_32") (pintype "passive"))
      (node (ref "J15") (pin "32") (pinfunction "A32_32") (pintype "passive"))
      (node (ref "J16") (pin "32") (pinfunction "A32_32") (pintype "passive"))
      (node (ref "J2") (pin "32") (pinfunction "A32_32") (pintype "passive"))
      (node (ref "J3") (pin "32") (pinfunction "A32_32") (pintype "passive"))
      (node (ref "J4") (pin "32") (pinfunction "A32_32") (pintype "passive"))
      (node (ref "J5") (pin "32") (pinfunction "A32_32") (pintype "passive"))
      (node (ref "J6") (pin "32") (pinfunction "A32_32") (pintype "passive"))
      (node (ref "J7") (pin "32") (pinfunction "A32_32") (pintype "passive"))
      (node (ref "J8") (pin "32") (pinfunction "A32_32") (pintype "passive"))
      (node (ref "J9") (pin "32") (pinfunction "A32_32") (pintype "passive"))
      (node (ref "R10") (pin "2") (pinfunction "2_2") (pintype "passive"))
      (node (ref "U8") (pin "13") (pinfunction "DO4-_13") (pintype "passive"))
    )
    (net (code "97") (name "/bus10") (class "Default")
      (node (ref "P9") (pin "18") (pinfunction "18_18") (pintype "passive"))
      (node (ref "U11") (pin "1B23") (pinfunction "P4/L23p_1B23") (pintype "passive"))
      (node (ref "U8") (pin "1") (pinfunction "DI1_1") (pintype "passive"))
    )
    (net (code "98") (name "/bus10_n") (class "Default")
      (node (ref "J1") (pin "38") (pinfunction "A38_38") (pintype "passive"))
      (node (ref "J10") (pin "38") (pinfunction "A38_38") (pintype "passive"))
      (node (ref "J11") (pin "38") (pinfunction "A38_38") (pintype "passive"))
      (node (ref "J12") (pin "38") (pinfunction "A38_38") (pintype "passive"))
      (node (ref "J13") (pin "38") (pinfunction "A38_38") (pintype "passive"))
      (node (ref "J14") (pin "38") (pinfunction "A38_38") (pintype "passive"))
      (node (ref "J15") (pin "38") (pinfunction "A38_38") (pintype "passive"))
      (node (ref "J16") (pin "38") (pinfunction "A38_38") (pintype "passive"))
      (node (ref "J2") (pin "38") (pinfunction "A38_38") (pintype "passive"))
      (node (ref "J3") (pin "38") (pinfunction "A38_38") (pintype "passive"))
      (node (ref "J4") (pin "38") (pinfunction "A38_38") (pintype "passive"))
      (node (ref "J5") (pin "38") (pinfunction "A38_38") (pintype "passive"))
      (node (ref "J6") (pin "38") (pinfunction "A38_38") (pintype "passive"))
      (node (ref "J7") (pin "38") (pinfunction "A38_38") (pintype "passive"))
      (node (ref "J8") (pin "38") (pinfunction "A38_38") (pintype "passive"))
      (node (ref "J9") (pin "38") (pinfunction "A38_38") (pintype "passive"))
      (node (ref "R11") (pin "1") (pinfunction "1_1") (pintype "passive"))
      (node (ref "U8") (pin "2") (pinfunction "DO1+_2") (pintype "passive"))
    )
    (net (code "99") (name "/bus10_p") (class "Default")
      (node (ref "J1") (pin "37") (pinfunction "A37_37") (pintype "passive"))
      (node (ref "J10") (pin "37") (pinfunction "A37_37") (pintype "passive"))
      (node (ref "J11") (pin "37") (pinfunction "A37_37") (pintype "passive"))
      (node (ref "J12") (pin "37") (pinfunction "A37_37") (pintype "passive"))
      (node (ref "J13") (pin "37") (pinfunction "A37_37") (pintype "passive"))
      (node (ref "J14") (pin "37") (pinfunction "A37_37") (pintype "passive"))
      (node (ref "J15") (pin "37") (pinfunction "A37_37") (pintype "passive"))
      (node (ref "J16") (pin "37") (pinfunction "A37_37") (pintype "passive"))
      (node (ref "J2") (pin "37") (pinfunction "A37_37") (pintype "passive"))
      (node (ref "J3") (pin "37") (pinfunction "A37_37") (pintype "passive"))
      (node (ref "J4") (pin "37") (pinfunction "A37_37") (pintype "passive"))
      (node (ref "J5") (pin "37") (pinfunction "A37_37") (pintype "passive"))
      (node (ref "J6") (pin "37") (pinfunction "A37_37") (pintype "passive"))
      (node (ref "J7") (pin "37") (pinfunction "A37_37") (pintype "passive"))
      (node (ref "J8") (pin "37") (pinfunction "A37_37") (pintype "passive"))
      (node (ref "J9") (pin "37") (pinfunction "A37_37") (pintype "passive"))
      (node (ref "R11") (pin "2") (pinfunction "2_2") (pintype "passive"))
      (node (ref "U8") (pin "3") (pinfunction "DO1-_3") (pintype "passive"))
    )
    (net (code "100") (name "/bus11") (class "Default")
      (node (ref "P9") (pin "17") (pinfunction "17_17") (pintype "passive"))
      (node (ref "U11") (pin "1B22") (pinfunction "Y7/B7n_1B22") (pintype "passive"))
      (node (ref "U8") (pin "7") (pinfunction "DI2_7") (pintype "passive"))
    )
    (net (code "101") (name "/bus11_n") (class "Default")
      (node (ref "J1") (pin "35") (pinfunction "A35_35") (pintype "passive"))
      (node (ref "J10") (pin "35") (pinfunction "A35_35") (pintype "passive"))
      (node (ref "J11") (pin "35") (pinfunction "A35_35") (pintype "passive"))
      (node (ref "J12") (pin "35") (pinfunction "A35_35") (pintype "passive"))
      (node (ref "J13") (pin "35") (pinfunction "A35_35") (pintype "passive"))
      (node (ref "J14") (pin "35") (pinfunction "A35_35") (pintype "passive"))
      (node (ref "J15") (pin "35") (pinfunction "A35_35") (pintype "passive"))
      (node (ref "J16") (pin "35") (pinfunction "A35_35") (pintype "passive"))
      (node (ref "J2") (pin "35") (pinfunction "A35_35") (pintype "passive"))
      (node (ref "J3") (pin "35") (pinfunction "A35_35") (pintype "passive"))
      (node (ref "J4") (pin "35") (pinfunction "A35_35") (pintype "passive"))
      (node (ref "J5") (pin "35") (pinfunction "A35_35") (pintype "passive"))
      (node (ref "J6") (pin "35") (pinfunction "A35_35") (pintype "passive"))
      (node (ref "J7") (pin "35") (pinfunction "A35_35") (pintype "passive"))
      (node (ref "J8") (pin "35") (pinfunction "A35_35") (pintype "passive"))
      (node (ref "J9") (pin "35") (pinfunction "A35_35") (pintype "passive"))
      (node (ref "R12") (pin "1") (pinfunction "1_1") (pintype "passive"))
      (node (ref "U8") (pin "6") (pinfunction "DO2+_6") (pintype "passive"))
    )
    (net (code "102") (name "/bus11_p") (class "Default")
      (node (ref "J1") (pin "36") (pinfunction "A36_36") (pintype "passive"))
      (node (ref "J10") (pin "36") (pinfunction "A36_36") (pintype "passive"))
      (node (ref "J11") (pin "36") (pinfunction "A36_36") (pintype "passive"))
      (node (ref "J12") (pin "36") (pinfunction "A36_36") (pintype "passive"))
      (node (ref "J13") (pin "36") (pinfunction "A36_36") (pintype "passive"))
      (node (ref "J14") (pin "36") (pinfunction "A36_36") (pintype "passive"))
      (node (ref "J15") (pin "36") (pinfunction "A36_36") (pintype "passive"))
      (node (ref "J16") (pin "36") (pinfunction "A36_36") (pintype "passive"))
      (node (ref "J2") (pin "36") (pinfunction "A36_36") (pintype "passive"))
      (node (ref "J3") (pin "36") (pinfunction "A36_36") (pintype "passive"))
      (node (ref "J4") (pin "36") (pinfunction "A36_36") (pintype "passive"))
      (node (ref "J5") (pin "36") (pinfunction "A36_36") (pintype "passive"))
      (node (ref "J6") (pin "36") (pinfunction "A36_36") (pintype "passive"))
      (node (ref "J7") (pin "36") (pinfunction "A36_36") (pintype "passive"))
      (node (ref "J8") (pin "36") (pinfunction "A36_36") (pintype "passive"))
      (node (ref "J9") (pin "36") (pinfunction "A36_36") (pintype "passive"))
      (node (ref "R12") (pin "2") (pinfunction "2_2") (pintype "passive"))
      (node (ref "U8") (pin "5") (pinfunction "DO2-_5") (pintype "passive"))
    )
    (net (code "103") (name "/bus12") (class "Default")
      (node (ref "P9") (pin "10") (pinfunction "10_10") (pintype "passive"))
      (node (ref "U11") (pin "1B17") (pinfunction "P1/L20n_1B17") (pintype "passive"))
      (node (ref "U7") (pin "9") (pinfunction "DI3_9") (pintype "passive"))
    )
    (net (code "104") (name "/bus12_n") (class "Default")
      (node (ref "J1") (pin "25") (pinfunction "A25_25") (pintype "passive"))
      (node (ref "J10") (pin "25") (pinfunction "A25_25") (pintype "passive"))
      (node (ref "J11") (pin "25") (pinfunction "A25_25") (pintype "passive"))
      (node (ref "J12") (pin "25") (pinfunction "A25_25") (pintype "passive"))
      (node (ref "J13") (pin "25") (pinfunction "A25_25") (pintype "passive"))
      (node (ref "J14") (pin "25") (pinfunction "A25_25") (pintype "passive"))
      (node (ref "J15") (pin "25") (pinfunction "A25_25") (pintype "passive"))
      (node (ref "J16") (pin "25") (pinfunction "A25_25") (pintype "passive"))
      (node (ref "J2") (pin "25") (pinfunction "A25_25") (pintype "passive"))
      (node (ref "J3") (pin "25") (pinfunction "A25_25") (pintype "passive"))
      (node (ref "J4") (pin "25") (pinfunction "A25_25") (pintype "passive"))
      (node (ref "J5") (pin "25") (pinfunction "A25_25") (pintype "passive"))
      (node (ref "J6") (pin "25") (pinfunction "A25_25") (pintype "passive"))
      (node (ref "J7") (pin "25") (pinfunction "A25_25") (pintype "passive"))
      (node (ref "J8") (pin "25") (pinfunction "A25_25") (pintype "passive"))
      (node (ref "J9") (pin "25") (pinfunction "A25_25") (pintype "passive"))
      (node (ref "R13") (pin "1") (pinfunction "1_1") (pintype "passive"))
      (node (ref "U7") (pin "10") (pinfunction "DO3+_10") (pintype "passive"))
    )
    (net (code "105") (name "/bus12_p") (class "Default")
      (node (ref "J1") (pin "24") (pinfunction "A24_24") (pintype "passive"))
      (node (ref "J10") (pin "24") (pinfunction "A24_24") (pintype "passive"))
      (node (ref "J11") (pin "24") (pinfunction "A24_24") (pintype "passive"))
      (node (ref "J12") (pin "24") (pinfunction "A24_24") (pintype "passive"))
      (node (ref "J13") (pin "24") (pinfunction "A24_24") (pintype "passive"))
      (node (ref "J14") (pin "24") (pinfunction "A24_24") (pintype "passive"))
      (node (ref "J15") (pin "24") (pinfunction "A24_24") (pintype "passive"))
      (node (ref "J16") (pin "24") (pinfunction "A24_24") (pintype "passive"))
      (node (ref "J2") (pin "24") (pinfunction "A24_24") (pintype "passive"))
      (node (ref "J3") (pin "24") (pinfunction "A24_24") (pintype "passive"))
      (node (ref "J4") (pin "24") (pinfunction "A24_24") (pintype "passive"))
      (node (ref "J5") (pin "24") (pinfunction "A24_24") (pintype "passive"))
      (node (ref "J6") (pin "24") (pinfunction "A24_24") (pintype "passive"))
      (node (ref "J7") (pin "24") (pinfunction "A24_24") (pintype "passive"))
      (node (ref "J8") (pin "24") (pinfunction "A24_24") (pintype "passive"))
      (node (ref "J9") (pin "24") (pinfunction "A24_24") (pintype "passive"))
      (node (ref "R13") (pin "2") (pinfunction "2_2") (pintype "passive"))
      (node (ref "U7") (pin "11") (pinfunction "DO3-_11") (pintype "passive"))
    )
    (net (code "106") (name "/bus13") (class "Default")
      (node (ref "P9") (pin "9") (pinfunction "9_9") (pintype "passive"))
      (node (ref "U11") (pin "1B16") (pinfunction "AB6/B6p_1B16") (pintype "passive"))
      (node (ref "U7") (pin "15") (pinfunction "DI4_15") (pintype "passive"))
    )
    (net (code "107") (name "/bus13_n") (class "Default")
      (node (ref "J1") (pin "22") (pinfunction "A22_22") (pintype "passive"))
      (node (ref "J10") (pin "22") (pinfunction "A22_22") (pintype "passive"))
      (node (ref "J11") (pin "22") (pinfunction "A22_22") (pintype "passive"))
      (node (ref "J12") (pin "22") (pinfunction "A22_22") (pintype "passive"))
      (node (ref "J13") (pin "22") (pinfunction "A22_22") (pintype "passive"))
      (node (ref "J14") (pin "22") (pinfunction "A22_22") (pintype "passive"))
      (node (ref "J15") (pin "22") (pinfunction "A22_22") (pintype "passive"))
      (node (ref "J16") (pin "22") (pinfunction "A22_22") (pintype "passive"))
      (node (ref "J2") (pin "22") (pinfunction "A22_22") (pintype "passive"))
      (node (ref "J3") (pin "22") (pinfunction "A22_22") (pintype "passive"))
      (node (ref "J4") (pin "22") (pinfunction "A22_22") (pintype "passive"))
      (node (ref "J5") (pin "22") (pinfunction "A22_22") (pintype "passive"))
      (node (ref "J6") (pin "22") (pinfunction "A22_22") (pintype "passive"))
      (node (ref "J7") (pin "22") (pinfunction "A22_22") (pintype "passive"))
      (node (ref "J8") (pin "22") (pinfunction "A22_22") (pintype "passive"))
      (node (ref "J9") (pin "22") (pinfunction "A22_22") (pintype "passive"))
      (node (ref "R14") (pin "1") (pinfunction "1_1") (pintype "passive"))
      (node (ref "U7") (pin "14") (pinfunction "DO4+_14") (pintype "passive"))
    )
    (net (code "108") (name "/bus13_p") (class "Default")
      (node (ref "J1") (pin "23") (pinfunction "A23_23") (pintype "passive"))
      (node (ref "J10") (pin "23") (pinfunction "A23_23") (pintype "passive"))
      (node (ref "J11") (pin "23") (pinfunction "A23_23") (pintype "passive"))
      (node (ref "J12") (pin "23") (pinfunction "A23_23") (pintype "passive"))
      (node (ref "J13") (pin "23") (pinfunction "A23_23") (pintype "passive"))
      (node (ref "J14") (pin "23") (pinfunction "A23_23") (pintype "passive"))
      (node (ref "J15") (pin "23") (pinfunction "A23_23") (pintype "passive"))
      (node (ref "J16") (pin "23") (pinfunction "A23_23") (pintype "passive"))
      (node (ref "J2") (pin "23") (pinfunction "A23_23") (pintype "passive"))
      (node (ref "J3") (pin "23") (pinfunction "A23_23") (pintype "passive"))
      (node (ref "J4") (pin "23") (pinfunction "A23_23") (pintype "passive"))
      (node (ref "J5") (pin "23") (pinfunction "A23_23") (pintype "passive"))
      (node (ref "J6") (pin "23") (pinfunction "A23_23") (pintype "passive"))
      (node (ref "J7") (pin "23") (pinfunction "A23_23") (pintype "passive"))
      (node (ref "J8") (pin "23") (pinfunction "A23_23") (pintype "passive"))
      (node (ref "J9") (pin "23") (pinfunction "A23_23") (pintype "passive"))
      (node (ref "R14") (pin "2") (pinfunction "2_2") (pintype "passive"))
      (node (ref "U7") (pin "13") (pinfunction "DO4-_13") (pintype "passive"))
    )
    (net (code "109") (name "/bus14") (class "Default")
      (node (ref "P9") (pin "12") (pinfunction "12_12") (pintype "passive"))
      (node (ref "U11") (pin "1B19") (pinfunction "R2/L21p_1B19") (pintype "passive"))
      (node (ref "U7") (pin "1") (pinfunction "DI1_1") (pintype "passive"))
    )
    (net (code "110") (name "/bus14_n") (class "Default")
      (node (ref "J1") (pin "29") (pinfunction "A29_29") (pintype "passive"))
      (node (ref "J10") (pin "29") (pinfunction "A29_29") (pintype "passive"))
      (node (ref "J11") (pin "29") (pinfunction "A29_29") (pintype "passive"))
      (node (ref "J12") (pin "29") (pinfunction "A29_29") (pintype "passive"))
      (node (ref "J13") (pin "29") (pinfunction "A29_29") (pintype "passive"))
      (node (ref "J14") (pin "29") (pinfunction "A29_29") (pintype "passive"))
      (node (ref "J15") (pin "29") (pinfunction "A29_29") (pintype "passive"))
      (node (ref "J16") (pin "29") (pinfunction "A29_29") (pintype "passive"))
      (node (ref "J2") (pin "29") (pinfunction "A29_29") (pintype "passive"))
      (node (ref "J3") (pin "29") (pinfunction "A29_29") (pintype "passive"))
      (node (ref "J4") (pin "29") (pinfunction "A29_29") (pintype "passive"))
      (node (ref "J5") (pin "29") (pinfunction "A29_29") (pintype "passive"))
      (node (ref "J6") (pin "29") (pinfunction "A29_29") (pintype "passive"))
      (node (ref "J7") (pin "29") (pinfunction "A29_29") (pintype "passive"))
      (node (ref "J8") (pin "29") (pinfunction "A29_29") (pintype "passive"))
      (node (ref "J9") (pin "29") (pinfunction "A29_29") (pintype "passive"))
      (node (ref "R15") (pin "1") (pinfunction "1_1") (pintype "passive"))
      (node (ref "U7") (pin "2") (pinfunction "DO1+_2") (pintype "passive"))
    )
    (net (code "111") (name "/bus14_p") (class "Default")
      (node (ref "J1") (pin "28") (pinfunction "A28_28") (pintype "passive"))
      (node (ref "J10") (pin "28") (pinfunction "A28_28") (pintype "passive"))
      (node (ref "J11") (pin "28") (pinfunction "A28_28") (pintype "passive"))
      (node (ref "J12") (pin "28") (pinfunction "A28_28") (pintype "passive"))
      (node (ref "J13") (pin "28") (pinfunction "A28_28") (pintype "passive"))
      (node (ref "J14") (pin "28") (pinfunction "A28_28") (pintype "passive"))
      (node (ref "J15") (pin "28") (pinfunction "A28_28") (pintype "passive"))
      (node (ref "J16") (pin "28") (pinfunction "A28_28") (pintype "passive"))
      (node (ref "J2") (pin "28") (pinfunction "A28_28") (pintype "passive"))
      (node (ref "J3") (pin "28") (pinfunction "A28_28") (pintype "passive"))
      (node (ref "J4") (pin "28") (pinfunction "A28_28") (pintype "passive"))
      (node (ref "J5") (pin "28") (pinfunction "A28_28") (pintype "passive"))
      (node (ref "J6") (pin "28") (pinfunction "A28_28") (pintype "passive"))
      (node (ref "J7") (pin "28") (pinfunction "A28_28") (pintype "passive"))
      (node (ref "J8") (pin "28") (pinfunction "A28_28") (pintype "passive"))
      (node (ref "J9") (pin "28") (pinfunction "A28_28") (pintype "passive"))
      (node (ref "R15") (pin "2") (pinfunction "2_2") (pintype "passive"))
      (node (ref "U7") (pin "3") (pinfunction "DO1-_3") (pintype "passive"))
    )
    (net (code "112") (name "/bus15") (class "Default")
      (node (ref "P9") (pin "11") (pinfunction "11_11") (pintype "passive"))
      (node (ref "U11") (pin "1B18") (pinfunction "AB5/B6n_1B18") (pintype "passive"))
      (node (ref "U7") (pin "7") (pinfunction "DI2_7") (pintype "passive"))
    )
    (net (code "113") (name "/bus15_n") (class "Default")
      (node (ref "J1") (pin "26") (pinfunction "A26_26") (pintype "passive"))
      (node (ref "J10") (pin "26") (pinfunction "A26_26") (pintype "passive"))
      (node (ref "J11") (pin "26") (pinfunction "A26_26") (pintype "passive"))
      (node (ref "J12") (pin "26") (pinfunction "A26_26") (pintype "passive"))
      (node (ref "J13") (pin "26") (pinfunction "A26_26") (pintype "passive"))
      (node (ref "J14") (pin "26") (pinfunction "A26_26") (pintype "passive"))
      (node (ref "J15") (pin "26") (pinfunction "A26_26") (pintype "passive"))
      (node (ref "J16") (pin "26") (pinfunction "A26_26") (pintype "passive"))
      (node (ref "J2") (pin "26") (pinfunction "A26_26") (pintype "passive"))
      (node (ref "J3") (pin "26") (pinfunction "A26_26") (pintype "passive"))
      (node (ref "J4") (pin "26") (pinfunction "A26_26") (pintype "passive"))
      (node (ref "J5") (pin "26") (pinfunction "A26_26") (pintype "passive"))
      (node (ref "J6") (pin "26") (pinfunction "A26_26") (pintype "passive"))
      (node (ref "J7") (pin "26") (pinfunction "A26_26") (pintype "passive"))
      (node (ref "J8") (pin "26") (pinfunction "A26_26") (pintype "passive"))
      (node (ref "J9") (pin "26") (pinfunction "A26_26") (pintype "passive"))
      (node (ref "R16") (pin "1") (pinfunction "1_1") (pintype "passive"))
      (node (ref "U7") (pin "6") (pinfunction "DO2+_6") (pintype "passive"))
    )
    (net (code "114") (name "/bus15_p") (class "Default")
      (node (ref "J1") (pin "27") (pinfunction "A27_27") (pintype "passive"))
      (node (ref "J10") (pin "27") (pinfunction "A27_27") (pintype "passive"))
      (node (ref "J11") (pin "27") (pinfunction "A27_27") (pintype "passive"))
      (node (ref "J12") (pin "27") (pinfunction "A27_27") (pintype "passive"))
      (node (ref "J13") (pin "27") (pinfunction "A27_27") (pintype "passive"))
      (node (ref "J14") (pin "27") (pinfunction "A27_27") (pintype "passive"))
      (node (ref "J15") (pin "27") (pinfunction "A27_27") (pintype "passive"))
      (node (ref "J16") (pin "27") (pinfunction "A27_27") (pintype "passive"))
      (node (ref "J2") (pin "27") (pinfunction "A27_27") (pintype "passive"))
      (node (ref "J3") (pin "27") (pinfunction "A27_27") (pintype "passive"))
      (node (ref "J4") (pin "27") (pinfunction "A27_27") (pintype "passive"))
      (node (ref "J5") (pin "27") (pinfunction "A27_27") (pintype "passive"))
      (node (ref "J6") (pin "27") (pinfunction "A27_27") (pintype "passive"))
      (node (ref "J7") (pin "27") (pinfunction "A27_27") (pintype "passive"))
      (node (ref "J8") (pin "27") (pinfunction "A27_27") (pintype "passive"))
      (node (ref "J9") (pin "27") (pinfunction "A27_27") (pintype "passive"))
      (node (ref "R16") (pin "2") (pinfunction "2_2") (pintype "passive"))
      (node (ref "U7") (pin "5") (pinfunction "DO2-_5") (pintype "passive"))
    )
    (net (code "115") (name "/bus16") (class "Default")
      (node (ref "P7") (pin "16") (pinfunction "16_16") (pintype "passive"))
      (node (ref "U11") (pin "1A23") (pinfunction "W8/IO_1A23") (pintype "passive"))
      (node (ref "U6") (pin "9") (pinfunction "DI3_9") (pintype "passive"))
    )
    (net (code "116") (name "/bus16_n") (class "Default")
      (node (ref "J1") (pin "113") (pinfunction "B53_113") (pintype "passive"))
      (node (ref "J10") (pin "113") (pinfunction "B53_113") (pintype "passive"))
      (node (ref "J11") (pin "113") (pinfunction "B53_113") (pintype "passive"))
      (node (ref "J12") (pin "113") (pinfunction "B53_113") (pintype "passive"))
      (node (ref "J13") (pin "113") (pinfunction "B53_113") (pintype "passive"))
      (node (ref "J14") (pin "113") (pinfunction "B53_113") (pintype "passive"))
      (node (ref "J15") (pin "113") (pinfunction "B53_113") (pintype "passive"))
      (node (ref "J16") (pin "113") (pinfunction "B53_113") (pintype "passive"))
      (node (ref "J2") (pin "113") (pinfunction "B53_113") (pintype "passive"))
      (node (ref "J3") (pin "113") (pinfunction "B53_113") (pintype "passive"))
      (node (ref "J4") (pin "113") (pinfunction "B53_113") (pintype "passive"))
      (node (ref "J5") (pin "113") (pinfunction "B53_113") (pintype "passive"))
      (node (ref "J6") (pin "113") (pinfunction "B53_113") (pintype "passive"))
      (node (ref "J7") (pin "113") (pinfunction "B53_113") (pintype "passive"))
      (node (ref "J8") (pin "113") (pinfunction "B53_113") (pintype "passive"))
      (node (ref "J9") (pin "113") (pinfunction "B53_113") (pintype "passive"))
      (node (ref "R17") (pin "1") (pinfunction "1_1") (pintype "passive"))
      (node (ref "U6") (pin "10") (pinfunction "DO3+_10") (pintype "passive"))
    )
    (net (code "117") (name "/bus16_p") (class "Default")
      (node (ref "J1") (pin "114") (pinfunction "B54_114") (pintype "passive"))
      (node (ref "J10") (pin "114") (pinfunction "B54_114") (pintype "passive"))
      (node (ref "J11") (pin "114") (pinfunction "B54_114") (pintype "passive"))
      (node (ref "J12") (pin "114") (pinfunction "B54_114") (pintype "passive"))
      (node (ref "J13") (pin "114") (pinfunction "B54_114") (pintype "passive"))
      (node (ref "J14") (pin "114") (pinfunction "B54_114") (pintype "passive"))
      (node (ref "J15") (pin "114") (pinfunction "B54_114") (pintype "passive"))
      (node (ref "J16") (pin "114") (pinfunction "B54_114") (pintype "passive"))
      (node (ref "J2") (pin "114") (pinfunction "B54_114") (pintype "passive"))
      (node (ref "J3") (pin "114") (pinfunction "B54_114") (pintype "passive"))
      (node (ref "J4") (pin "114") (pinfunction "B54_114") (pintype "passive"))
      (node (ref "J5") (pin "114") (pinfunction "B54_114") (pintype "passive"))
      (node (ref "J6") (pin "114") (pinfunction "B54_114") (pintype "passive"))
      (node (ref "J7") (pin "114") (pinfunction "B54_114") (pintype "passive"))
      (node (ref "J8") (pin "114") (pinfunction "B54_114") (pintype "passive"))
      (node (ref "J9") (pin "114") (pinfunction "B54_114") (pintype "passive"))
      (node (ref "R17") (pin "2") (pinfunction "2_2") (pintype "passive"))
      (node (ref "U6") (pin "11") (pinfunction "DO3-_11") (pintype "passive"))
    )
    (net (code "118") (name "/bus17") (class "Default")
      (node (ref "P7") (pin "15") (pinfunction "15_15") (pintype "passive"))
      (node (ref "U11") (pin "1A20") (pinfunction "U10/B16n_1A20") (pintype "passive"))
      (node (ref "U6") (pin "15") (pinfunction "DI4_15") (pintype "passive"))
    )
    (net (code "119") (name "/bus17_n") (class "Default")
      (node (ref "J1") (pin "116") (pinfunction "B56_116") (pintype "passive"))
      (node (ref "J10") (pin "116") (pinfunction "B56_116") (pintype "passive"))
      (node (ref "J11") (pin "116") (pinfunction "B56_116") (pintype "passive"))
      (node (ref "J12") (pin "116") (pinfunction "B56_116") (pintype "passive"))
      (node (ref "J13") (pin "116") (pinfunction "B56_116") (pintype "passive"))
      (node (ref "J14") (pin "116") (pinfunction "B56_116") (pintype "passive"))
      (node (ref "J15") (pin "116") (pinfunction "B56_116") (pintype "passive"))
      (node (ref "J16") (pin "116") (pinfunction "B56_116") (pintype "passive"))
      (node (ref "J2") (pin "116") (pinfunction "B56_116") (pintype "passive"))
      (node (ref "J3") (pin "116") (pinfunction "B56_116") (pintype "passive"))
      (node (ref "J4") (pin "116") (pinfunction "B56_116") (pintype "passive"))
      (node (ref "J5") (pin "116") (pinfunction "B56_116") (pintype "passive"))
      (node (ref "J6") (pin "116") (pinfunction "B56_116") (pintype "passive"))
      (node (ref "J7") (pin "116") (pinfunction "B56_116") (pintype "passive"))
      (node (ref "J8") (pin "116") (pinfunction "B56_116") (pintype "passive"))
      (node (ref "J9") (pin "116") (pinfunction "B56_116") (pintype "passive"))
      (node (ref "R18") (pin "1") (pinfunction "1_1") (pintype "passive"))
      (node (ref "U6") (pin "14") (pinfunction "DO4+_14") (pintype "passive"))
    )
    (net (code "120") (name "/bus17_p") (class "Default")
      (node (ref "J1") (pin "115") (pinfunction "B55_115") (pintype "passive"))
      (node (ref "J10") (pin "115") (pinfunction "B55_115") (pintype "passive"))
      (node (ref "J11") (pin "115") (pinfunction "B55_115") (pintype "passive"))
      (node (ref "J12") (pin "115") (pinfunction "B55_115") (pintype "passive"))
      (node (ref "J13") (pin "115") (pinfunction "B55_115") (pintype "passive"))
      (node (ref "J14") (pin "115") (pinfunction "B55_115") (pintype "passive"))
      (node (ref "J15") (pin "115") (pinfunction "B55_115") (pintype "passive"))
      (node (ref "J16") (pin "115") (pinfunction "B55_115") (pintype "passive"))
      (node (ref "J2") (pin "115") (pinfunction "B55_115") (pintype "passive"))
      (node (ref "J3") (pin "115") (pinfunction "B55_115") (pintype "passive"))
      (node (ref "J4") (pin "115") (pinfunction "B55_115") (pintype "passive"))
      (node (ref "J5") (pin "115") (pinfunction "B55_115") (pintype "passive"))
      (node (ref "J6") (pin "115") (pinfunction "B55_115") (pintype "passive"))
      (node (ref "J7") (pin "115") (pinfunction "B55_115") (pintype "passive"))
      (node (ref "J8") (pin "115") (pinfunction "B55_115") (pintype "passive"))
      (node (ref "J9") (pin "115") (pinfunction "B55_115") (pintype "passive"))
      (node (ref "R18") (pin "2") (pinfunction "2_2") (pintype "passive"))
      (node (ref "U6") (pin "13") (pinfunction "DO4-_13") (pintype "passive"))
    )
    (net (code "121") (name "/bus18") (class "Default")
      (node (ref "P7") (pin "18") (pinfunction "18_18") (pintype "passive"))
      (node (ref "U11") (pin "1A29") (pinfunction "V10/B15p_1A29") (pintype "passive"))
      (node (ref "U6") (pin "1") (pinfunction "DI1_1") (pintype "passive"))
    )
    (net (code "122") (name "/bus18_n") (class "Default")
      (node (ref "J1") (pin "109") (pinfunction "B49_109") (pintype "passive"))
      (node (ref "J10") (pin "109") (pinfunction "B49_109") (pintype "passive"))
      (node (ref "J11") (pin "109") (pinfunction "B49_109") (pintype "passive"))
      (node (ref "J12") (pin "109") (pinfunction "B49_109") (pintype "passive"))
      (node (ref "J13") (pin "109") (pinfunction "B49_109") (pintype "passive"))
      (node (ref "J14") (pin "109") (pinfunction "B49_109") (pintype "passive"))
      (node (ref "J15") (pin "109") (pinfunction "B49_109") (pintype "passive"))
      (node (ref "J16") (pin "109") (pinfunction "B49_109") (pintype "passive"))
      (node (ref "J2") (pin "109") (pinfunction "B49_109") (pintype "passive"))
      (node (ref "J3") (pin "109") (pinfunction "B49_109") (pintype "passive"))
      (node (ref "J4") (pin "109") (pinfunction "B49_109") (pintype "passive"))
      (node (ref "J5") (pin "109") (pinfunction "B49_109") (pintype "passive"))
      (node (ref "J6") (pin "109") (pinfunction "B49_109") (pintype "passive"))
      (node (ref "J7") (pin "109") (pinfunction "B49_109") (pintype "passive"))
      (node (ref "J8") (pin "109") (pinfunction "B49_109") (pintype "passive"))
      (node (ref "J9") (pin "109") (pinfunction "B49_109") (pintype "passive"))
      (node (ref "R19") (pin "1") (pinfunction "1_1") (pintype "passive"))
      (node (ref "U6") (pin "2") (pinfunction "DO1+_2") (pintype "passive"))
    )
    (net (code "123") (name "/bus18_p") (class "Default")
      (node (ref "J1") (pin "110") (pinfunction "B50_110") (pintype "passive"))
      (node (ref "J10") (pin "110") (pinfunction "B50_110") (pintype "passive"))
      (node (ref "J11") (pin "110") (pinfunction "B50_110") (pintype "passive"))
      (node (ref "J12") (pin "110") (pinfunction "B50_110") (pintype "passive"))
      (node (ref "J13") (pin "110") (pinfunction "B50_110") (pintype "passive"))
      (node (ref "J14") (pin "110") (pinfunction "B50_110") (pintype "passive"))
      (node (ref "J15") (pin "110") (pinfunction "B50_110") (pintype "passive"))
      (node (ref "J16") (pin "110") (pinfunction "B50_110") (pintype "passive"))
      (node (ref "J2") (pin "110") (pinfunction "B50_110") (pintype "passive"))
      (node (ref "J3") (pin "110") (pinfunction "B50_110") (pintype "passive"))
      (node (ref "J4") (pin "110") (pinfunction "B50_110") (pintype "passive"))
      (node (ref "J5") (pin "110") (pinfunction "B50_110") (pintype "passive"))
      (node (ref "J6") (pin "110") (pinfunction "B50_110") (pintype "passive"))
      (node (ref "J7") (pin "110") (pinfunction "B50_110") (pintype "passive"))
      (node (ref "J8") (pin "110") (pinfunction "B50_110") (pintype "passive"))
      (node (ref "J9") (pin "110") (pinfunction "B50_110") (pintype "passive"))
      (node (ref "R19") (pin "2") (pinfunction "2_2") (pintype "passive"))
      (node (ref "U6") (pin "3") (pinfunction "DO1-_3") (pintype "passive"))
    )
    (net (code "124") (name "/bus19") (class "Default")
      (node (ref "P7") (pin "17") (pinfunction "17_17") (pintype "passive"))
      (node (ref "U11") (pin "1A28") (pinfunction "V8/B8n_1A28") (pintype "passive"))
      (node (ref "U6") (pin "7") (pinfunction "DI2_7") (pintype "passive"))
    )
    (net (code "125") (name "/bus19_n") (class "Default")
      (node (ref "J1") (pin "112") (pinfunction "B52_112") (pintype "passive"))
      (node (ref "J10") (pin "112") (pinfunction "B52_112") (pintype "passive"))
      (node (ref "J11") (pin "112") (pinfunction "B52_112") (pintype "passive"))
      (node (ref "J12") (pin "112") (pinfunction "B52_112") (pintype "passive"))
      (node (ref "J13") (pin "112") (pinfunction "B52_112") (pintype "passive"))
      (node (ref "J14") (pin "112") (pinfunction "B52_112") (pintype "passive"))
      (node (ref "J15") (pin "112") (pinfunction "B52_112") (pintype "passive"))
      (node (ref "J16") (pin "112") (pinfunction "B52_112") (pintype "passive"))
      (node (ref "J2") (pin "112") (pinfunction "B52_112") (pintype "passive"))
      (node (ref "J3") (pin "112") (pinfunction "B52_112") (pintype "passive"))
      (node (ref "J4") (pin "112") (pinfunction "B52_112") (pintype "passive"))
      (node (ref "J5") (pin "112") (pinfunction "B52_112") (pintype "passive"))
      (node (ref "J6") (pin "112") (pinfunction "B52_112") (pintype "passive"))
      (node (ref "J7") (pin "112") (pinfunction "B52_112") (pintype "passive"))
      (node (ref "J8") (pin "112") (pinfunction "B52_112") (pintype "passive"))
      (node (ref "J9") (pin "112") (pinfunction "B52_112") (pintype "passive"))
      (node (ref "R20") (pin "1") (pinfunction "1_1") (pintype "passive"))
      (node (ref "U6") (pin "6") (pinfunction "DO2+_6") (pintype "passive"))
    )
    (net (code "126") (name "/bus19_p") (class "Default")
      (node (ref "J1") (pin "111") (pinfunction "B51_111") (pintype "passive"))
      (node (ref "J10") (pin "111") (pinfunction "B51_111") (pintype "passive"))
      (node (ref "J11") (pin "111") (pinfunction "B51_111") (pintype "passive"))
      (node (ref "J12") (pin "111") (pinfunction "B51_111") (pintype "passive"))
      (node (ref "J13") (pin "111") (pinfunction "B51_111") (pintype "passive"))
      (node (ref "J14") (pin "111") (pinfunction "B51_111") (pintype "passive"))
      (node (ref "J15") (pin "111") (pinfunction "B51_111") (pintype "passive"))
      (node (ref "J16") (pin "111") (pinfunction "B51_111") (pintype "passive"))
      (node (ref "J2") (pin "111") (pinfunction "B51_111") (pintype "passive"))
      (node (ref "J3") (pin "111") (pinfunction "B51_111") (pintype "passive"))
      (node (ref "J4") (pin "111") (pinfunction "B51_111") (pintype "passive"))
      (node (ref "J5") (pin "111") (pinfunction "B51_111") (pintype "passive"))
      (node (ref "J6") (pin "111") (pinfunction "B51_111") (pintype "passive"))
      (node (ref "J7") (pin "111") (pinfunction "B51_111") (pintype "passive"))
      (node (ref "J8") (pin "111") (pinfunction "B51_111") (pintype "passive"))
      (node (ref "J9") (pin "111") (pinfunction "B51_111") (pintype "passive"))
      (node (ref "R20") (pin "2") (pinfunction "2_2") (pintype "passive"))
      (node (ref "U6") (pin "5") (pinfunction "DO2-_5") (pintype "passive"))
    )
    (net (code "127") (name "/bus20") (class "Default")
      (node (ref "P7") (pin "20") (pinfunction "20_20") (pintype "passive"))
      (node (ref "U11") (pin "1A31") (pinfunction "U9/B8p_1A31") (pintype "passive"))
      (node (ref "U5") (pin "9") (pinfunction "DI3_9") (pintype "passive"))
    )
    (net (code "128") (name "/bus20_n") (class "Default")
      (node (ref "J1") (pin "104") (pinfunction "B44_104") (pintype "passive"))
      (node (ref "J10") (pin "104") (pinfunction "B44_104") (pintype "passive"))
      (node (ref "J11") (pin "104") (pinfunction "B44_104") (pintype "passive"))
      (node (ref "J12") (pin "104") (pinfunction "B44_104") (pintype "passive"))
      (node (ref "J13") (pin "104") (pinfunction "B44_104") (pintype "passive"))
      (node (ref "J14") (pin "104") (pinfunction "B44_104") (pintype "passive"))
      (node (ref "J15") (pin "104") (pinfunction "B44_104") (pintype "passive"))
      (node (ref "J16") (pin "104") (pinfunction "B44_104") (pintype "passive"))
      (node (ref "J2") (pin "104") (pinfunction "B44_104") (pintype "passive"))
      (node (ref "J3") (pin "104") (pinfunction "B44_104") (pintype "passive"))
      (node (ref "J4") (pin "104") (pinfunction "B44_104") (pintype "passive"))
      (node (ref "J5") (pin "104") (pinfunction "B44_104") (pintype "passive"))
      (node (ref "J6") (pin "104") (pinfunction "B44_104") (pintype "passive"))
      (node (ref "J7") (pin "104") (pinfunction "B44_104") (pintype "passive"))
      (node (ref "J8") (pin "104") (pinfunction "B44_104") (pintype "passive"))
      (node (ref "J9") (pin "104") (pinfunction "B44_104") (pintype "passive"))
      (node (ref "R21") (pin "1") (pinfunction "1_1") (pintype "passive"))
      (node (ref "U5") (pin "10") (pinfunction "DO3+_10") (pintype "passive"))
    )
    (net (code "129") (name "/bus20_p") (class "Default")
      (node (ref "J1") (pin "105") (pinfunction "B45_105") (pintype "passive"))
      (node (ref "J10") (pin "105") (pinfunction "B45_105") (pintype "passive"))
      (node (ref "J11") (pin "105") (pinfunction "B45_105") (pintype "passive"))
      (node (ref "J12") (pin "105") (pinfunction "B45_105") (pintype "passive"))
      (node (ref "J13") (pin "105") (pinfunction "B45_105") (pintype "passive"))
      (node (ref "J14") (pin "105") (pinfunction "B45_105") (pintype "passive"))
      (node (ref "J15") (pin "105") (pinfunction "B45_105") (pintype "passive"))
      (node (ref "J16") (pin "105") (pinfunction "B45_105") (pintype "passive"))
      (node (ref "J2") (pin "105") (pinfunction "B45_105") (pintype "passive"))
      (node (ref "J3") (pin "105") (pinfunction "B45_105") (pintype "passive"))
      (node (ref "J4") (pin "105") (pinfunction "B45_105") (pintype "passive"))
      (node (ref "J5") (pin "105") (pinfunction "B45_105") (pintype "passive"))
      (node (ref "J6") (pin "105") (pinfunction "B45_105") (pintype "passive"))
      (node (ref "J7") (pin "105") (pinfunction "B45_105") (pintype "passive"))
      (node (ref "J8") (pin "105") (pinfunction "B45_105") (pintype "passive"))
      (node (ref "J9") (pin "105") (pinfunction "B45_105") (pintype "passive"))
      (node (ref "R21") (pin "2") (pinfunction "2_2") (pintype "passive"))
      (node (ref "U5") (pin "11") (pinfunction "DO3-_11") (pintype "passive"))
    )
    (net (code "130") (name "/bus21") (class "Default")
      (node (ref "P7") (pin "19") (pinfunction "19_19") (pintype "passive"))
      (node (ref "U11") (pin "1A30") (pinfunction "Y6/IO_1A30") (pintype "passive"))
      (node (ref "U5") (pin "15") (pinfunction "DI4_15") (pintype "passive"))
    )
    (net (code "131") (name "/bus21_n") (class "Default")
      (node (ref "J1") (pin "107") (pinfunction "B47_107") (pintype "passive"))
      (node (ref "J10") (pin "107") (pinfunction "B47_107") (pintype "passive"))
      (node (ref "J11") (pin "107") (pinfunction "B47_107") (pintype "passive"))
      (node (ref "J12") (pin "107") (pinfunction "B47_107") (pintype "passive"))
      (node (ref "J13") (pin "107") (pinfunction "B47_107") (pintype "passive"))
      (node (ref "J14") (pin "107") (pinfunction "B47_107") (pintype "passive"))
      (node (ref "J15") (pin "107") (pinfunction "B47_107") (pintype "passive"))
      (node (ref "J16") (pin "107") (pinfunction "B47_107") (pintype "passive"))
      (node (ref "J2") (pin "107") (pinfunction "B47_107") (pintype "passive"))
      (node (ref "J3") (pin "107") (pinfunction "B47_107") (pintype "passive"))
      (node (ref "J4") (pin "107") (pinfunction "B47_107") (pintype "passive"))
      (node (ref "J5") (pin "107") (pinfunction "B47_107") (pintype "passive"))
      (node (ref "J6") (pin "107") (pinfunction "B47_107") (pintype "passive"))
      (node (ref "J7") (pin "107") (pinfunction "B47_107") (pintype "passive"))
      (node (ref "J8") (pin "107") (pinfunction "B47_107") (pintype "passive"))
      (node (ref "J9") (pin "107") (pinfunction "B47_107") (pintype "passive"))
      (node (ref "R22") (pin "1") (pinfunction "1_1") (pintype "passive"))
      (node (ref "U5") (pin "14") (pinfunction "DO4+_14") (pintype "passive"))
    )
    (net (code "132") (name "/bus21_p") (class "Default")
      (node (ref "J1") (pin "106") (pinfunction "B46_106") (pintype "passive"))
      (node (ref "J10") (pin "106") (pinfunction "B46_106") (pintype "passive"))
      (node (ref "J11") (pin "106") (pinfunction "B46_106") (pintype "passive"))
      (node (ref "J12") (pin "106") (pinfunction "B46_106") (pintype "passive"))
      (node (ref "J13") (pin "106") (pinfunction "B46_106") (pintype "passive"))
      (node (ref "J14") (pin "106") (pinfunction "B46_106") (pintype "passive"))
      (node (ref "J15") (pin "106") (pinfunction "B46_106") (pintype "passive"))
      (node (ref "J16") (pin "106") (pinfunction "B46_106") (pintype "passive"))
      (node (ref "J2") (pin "106") (pinfunction "B46_106") (pintype "passive"))
      (node (ref "J3") (pin "106") (pinfunction "B46_106") (pintype "passive"))
      (node (ref "J4") (pin "106") (pinfunction "B46_106") (pintype "passive"))
      (node (ref "J5") (pin "106") (pinfunction "B46_106") (pintype "passive"))
      (node (ref "J6") (pin "106") (pinfunction "B46_106") (pintype "passive"))
      (node (ref "J7") (pin "106") (pinfunction "B46_106") (pintype "passive"))
      (node (ref "J8") (pin "106") (pinfunction "B46_106") (pintype "passive"))
      (node (ref "J9") (pin "106") (pinfunction "B46_106") (pintype "passive"))
      (node (ref "R22") (pin "2") (pinfunction "2_2") (pintype "passive"))
      (node (ref "U5") (pin "13") (pinfunction "DO4-_13") (pintype "passive"))
    )
    (net (code "133") (name "/bus22") (class "Default")
      (node (ref "P7") (pin "26") (pinfunction "26_26") (pintype "passive"))
      (node (ref "U11") (pin "1A33") (pinfunction "Y3/B3n_1A33") (pintype "passive"))
      (node (ref "U5") (pin "1") (pinfunction "DI1_1") (pintype "passive"))
    )
    (net (code "134") (name "/bus22_n") (class "Default")
      (node (ref "J1") (pin "100") (pinfunction "B40_100") (pintype "passive"))
      (node (ref "J10") (pin "100") (pinfunction "B40_100") (pintype "passive"))
      (node (ref "J11") (pin "100") (pinfunction "B40_100") (pintype "passive"))
      (node (ref "J12") (pin "100") (pinfunction "B40_100") (pintype "passive"))
      (node (ref "J13") (pin "100") (pinfunction "B40_100") (pintype "passive"))
      (node (ref "J14") (pin "100") (pinfunction "B40_100") (pintype "passive"))
      (node (ref "J15") (pin "100") (pinfunction "B40_100") (pintype "passive"))
      (node (ref "J16") (pin "100") (pinfunction "B40_100") (pintype "passive"))
      (node (ref "J2") (pin "100") (pinfunction "B40_100") (pintype "passive"))
      (node (ref "J3") (pin "100") (pinfunction "B40_100") (pintype "passive"))
      (node (ref "J4") (pin "100") (pinfunction "B40_100") (pintype "passive"))
      (node (ref "J5") (pin "100") (pinfunction "B40_100") (pintype "passive"))
      (node (ref "J6") (pin "100") (pinfunction "B40_100") (pintype "passive"))
      (node (ref "J7") (pin "100") (pinfunction "B40_100") (pintype "passive"))
      (node (ref "J8") (pin "100") (pinfunction "B40_100") (pintype "passive"))
      (node (ref "J9") (pin "100") (pinfunction "B40_100") (pintype "passive"))
      (node (ref "R23") (pin "1") (pinfunction "1_1") (pintype "passive"))
      (node (ref "U5") (pin "2") (pinfunction "DO1+_2") (pintype "passive"))
    )
    (net (code "135") (name "/bus22_p") (class "Default")
      (node (ref "J1") (pin "101") (pinfunction "B41_101") (pintype "passive"))
      (node (ref "J10") (pin "101") (pinfunction "B41_101") (pintype "passive"))
      (node (ref "J11") (pin "101") (pinfunction "B41_101") (pintype "passive"))
      (node (ref "J12") (pin "101") (pinfunction "B41_101") (pintype "passive"))
      (node (ref "J13") (pin "101") (pinfunction "B41_101") (pintype "passive"))
      (node (ref "J14") (pin "101") (pinfunction "B41_101") (pintype "passive"))
      (node (ref "J15") (pin "101") (pinfunction "B41_101") (pintype "passive"))
      (node (ref "J16") (pin "101") (pinfunction "B41_101") (pintype "passive"))
      (node (ref "J2") (pin "101") (pinfunction "B41_101") (pintype "passive"))
      (node (ref "J3") (pin "101") (pinfunction "B41_101") (pintype "passive"))
      (node (ref "J4") (pin "101") (pinfunction "B41_101") (pintype "passive"))
      (node (ref "J5") (pin "101") (pinfunction "B41_101") (pintype "passive"))
      (node (ref "J6") (pin "101") (pinfunction "B41_101") (pintype "passive"))
      (node (ref "J7") (pin "101") (pinfunction "B41_101") (pintype "passive"))
      (node (ref "J8") (pin "101") (pinfunction "B41_101") (pintype "passive"))
      (node (ref "J9") (pin "101") (pinfunction "B41_101") (pintype "passive"))
      (node (ref "R23") (pin "2") (pinfunction "2_2") (pintype "passive"))
      (node (ref "U5") (pin "3") (pinfunction "DO1-_3") (pintype "passive"))
    )
    (net (code "136") (name "/bus23") (class "Default")
      (node (ref "P7") (pin "25") (pinfunction "25_25") (pintype "passive"))
      (node (ref "U11") (pin "1A32") (pinfunction "V6/B1p_1A32") (pintype "passive"))
      (node (ref "U5") (pin "7") (pinfunction "DI2_7") (pintype "passive"))
    )
    (net (code "137") (name "/bus23_n") (class "Default")
      (node (ref "J1") (pin "103") (pinfunction "B43_103") (pintype "passive"))
      (node (ref "J10") (pin "103") (pinfunction "B43_103") (pintype "passive"))
      (node (ref "J11") (pin "103") (pinfunction "B43_103") (pintype "passive"))
      (node (ref "J12") (pin "103") (pinfunction "B43_103") (pintype "passive"))
      (node (ref "J13") (pin "103") (pinfunction "B43_103") (pintype "passive"))
      (node (ref "J14") (pin "103") (pinfunction "B43_103") (pintype "passive"))
      (node (ref "J15") (pin "103") (pinfunction "B43_103") (pintype "passive"))
      (node (ref "J16") (pin "103") (pinfunction "B43_103") (pintype "passive"))
      (node (ref "J2") (pin "103") (pinfunction "B43_103") (pintype "passive"))
      (node (ref "J3") (pin "103") (pinfunction "B43_103") (pintype "passive"))
      (node (ref "J4") (pin "103") (pinfunction "B43_103") (pintype "passive"))
      (node (ref "J5") (pin "103") (pinfunction "B43_103") (pintype "passive"))
      (node (ref "J6") (pin "103") (pinfunction "B43_103") (pintype "passive"))
      (node (ref "J7") (pin "103") (pinfunction "B43_103") (pintype "passive"))
      (node (ref "J8") (pin "103") (pinfunction "B43_103") (pintype "passive"))
      (node (ref "J9") (pin "103") (pinfunction "B43_103") (pintype "passive"))
      (node (ref "R24") (pin "1") (pinfunction "1_1") (pintype "passive"))
      (node (ref "U5") (pin "6") (pinfunction "DO2+_6") (pintype "passive"))
    )
    (net (code "138") (name "/bus23_p") (class "Default")
      (node (ref "J1") (pin "102") (pinfunction "B42_102") (pintype "passive"))
      (node (ref "J10") (pin "102") (pinfunction "B42_102") (pintype "passive"))
      (node (ref "J11") (pin "102") (pinfunction "B42_102") (pintype "passive"))
      (node (ref "J12") (pin "102") (pinfunction "B42_102") (pintype "passive"))
      (node (ref "J13") (pin "102") (pinfunction "B42_102") (pintype "passive"))
      (node (ref "J14") (pin "102") (pinfunction "B42_102") (pintype "passive"))
      (node (ref "J15") (pin "102") (pinfunction "B42_102") (pintype "passive"))
      (node (ref "J16") (pin "102") (pinfunction "B42_102") (pintype "passive"))
      (node (ref "J2") (pin "102") (pinfunction "B42_102") (pintype "passive"))
      (node (ref "J3") (pin "102") (pinfunction "B42_102") (pintype "passive"))
      (node (ref "J4") (pin "102") (pinfunction "B42_102") (pintype "passive"))
      (node (ref "J5") (pin "102") (pinfunction "B42_102") (pintype "passive"))
      (node (ref "J6") (pin "102") (pinfunction "B42_102") (pintype "passive"))
      (node (ref "J7") (pin "102") (pinfunction "B42_102") (pintype "passive"))
      (node (ref "J8") (pin "102") (pinfunction "B42_102") (pintype "passive"))
      (node (ref "J9") (pin "102") (pinfunction "B42_102") (pintype "passive"))
      (node (ref "R24") (pin "2") (pinfunction "2_2") (pintype "passive"))
      (node (ref "U5") (pin "5") (pinfunction "DO2-_5") (pintype "passive"))
    )
    (net (code "139") (name "/bus24") (class "Default")
      (node (ref "P7") (pin "28") (pinfunction "28_28") (pintype "passive"))
      (node (ref "U11") (pin "1A35") (pinfunction "L6/L16p_1A35") (pintype "passive"))
      (node (ref "U4") (pin "9") (pinfunction "DI3_9") (pintype "passive"))
    )
    (net (code "140") (name "/bus24_n") (class "Default")
      (node (ref "J1") (pin "95") (pinfunction "B35_95") (pintype "passive"))
      (node (ref "J10") (pin "95") (pinfunction "B35_95") (pintype "passive"))
      (node (ref "J11") (pin "95") (pinfunction "B35_95") (pintype "passive"))
      (node (ref "J12") (pin "95") (pinfunction "B35_95") (pintype "passive"))
      (node (ref "J13") (pin "95") (pinfunction "B35_95") (pintype "passive"))
      (node (ref "J14") (pin "95") (pinfunction "B35_95") (pintype "passive"))
      (node (ref "J15") (pin "95") (pinfunction "B35_95") (pintype "passive"))
      (node (ref "J16") (pin "95") (pinfunction "B35_95") (pintype "passive"))
      (node (ref "J2") (pin "95") (pinfunction "B35_95") (pintype "passive"))
      (node (ref "J3") (pin "95") (pinfunction "B35_95") (pintype "passive"))
      (node (ref "J4") (pin "95") (pinfunction "B35_95") (pintype "passive"))
      (node (ref "J5") (pin "95") (pinfunction "B35_95") (pintype "passive"))
      (node (ref "J6") (pin "95") (pinfunction "B35_95") (pintype "passive"))
      (node (ref "J7") (pin "95") (pinfunction "B35_95") (pintype "passive"))
      (node (ref "J8") (pin "95") (pinfunction "B35_95") (pintype "passive"))
      (node (ref "J9") (pin "95") (pinfunction "B35_95") (pintype "passive"))
      (node (ref "R25") (pin "1") (pinfunction "1_1") (pintype "passive"))
      (node (ref "U4") (pin "10") (pinfunction "DO3+_10") (pintype "passive"))
    )
    (net (code "141") (name "/bus24_p") (class "Default")
      (node (ref "J1") (pin "96") (pinfunction "B36_96") (pintype "passive"))
      (node (ref "J10") (pin "96") (pinfunction "B36_96") (pintype "passive"))
      (node (ref "J11") (pin "96") (pinfunction "B36_96") (pintype "passive"))
      (node (ref "J12") (pin "96") (pinfunction "B36_96") (pintype "passive"))
      (node (ref "J13") (pin "96") (pinfunction "B36_96") (pintype "passive"))
      (node (ref "J14") (pin "96") (pinfunction "B36_96") (pintype "passive"))
      (node (ref "J15") (pin "96") (pinfunction "B36_96") (pintype "passive"))
      (node (ref "J16") (pin "96") (pinfunction "B36_96") (pintype "passive"))
      (node (ref "J2") (pin "96") (pinfunction "B36_96") (pintype "passive"))
      (node (ref "J3") (pin "96") (pinfunction "B36_96") (pintype "passive"))
      (node (ref "J4") (pin "96") (pinfunction "B36_96") (pintype "passive"))
      (node (ref "J5") (pin "96") (pinfunction "B36_96") (pintype "passive"))
      (node (ref "J6") (pin "96") (pinfunction "B36_96") (pintype "passive"))
      (node (ref "J7") (pin "96") (pinfunction "B36_96") (pintype "passive"))
      (node (ref "J8") (pin "96") (pinfunction "B36_96") (pintype "passive"))
      (node (ref "J9") (pin "96") (pinfunction "B36_96") (pintype "passive"))
      (node (ref "R25") (pin "2") (pinfunction "2_2") (pintype "passive"))
      (node (ref "U4") (pin "11") (pinfunction "DO3-_11") (pintype "passive"))
    )
    (net (code "142") (name "/bus25") (class "Default")
      (node (ref "P7") (pin "27") (pinfunction "27_27") (pintype "passive"))
      (node (ref "U11") (pin "1A34") (pinfunction "V5/B1n_1A34") (pintype "passive"))
      (node (ref "U4") (pin "15") (pinfunction "DI4_15") (pintype "passive"))
    )
    (net (code "143") (name "/bus25_n") (class "Default")
      (node (ref "J1") (pin "98") (pinfunction "B38_98") (pintype "passive"))
      (node (ref "J10") (pin "98") (pinfunction "B38_98") (pintype "passive"))
      (node (ref "J11") (pin "98") (pinfunction "B38_98") (pintype "passive"))
      (node (ref "J12") (pin "98") (pinfunction "B38_98") (pintype "passive"))
      (node (ref "J13") (pin "98") (pinfunction "B38_98") (pintype "passive"))
      (node (ref "J14") (pin "98") (pinfunction "B38_98") (pintype "passive"))
      (node (ref "J15") (pin "98") (pinfunction "B38_98") (pintype "passive"))
      (node (ref "J16") (pin "98") (pinfunction "B38_98") (pintype "passive"))
      (node (ref "J2") (pin "98") (pinfunction "B38_98") (pintype "passive"))
      (node (ref "J3") (pin "98") (pinfunction "B38_98") (pintype "passive"))
      (node (ref "J4") (pin "98") (pinfunction "B38_98") (pintype "passive"))
      (node (ref "J5") (pin "98") (pinfunction "B38_98") (pintype "passive"))
      (node (ref "J6") (pin "98") (pinfunction "B38_98") (pintype "passive"))
      (node (ref "J7") (pin "98") (pinfunction "B38_98") (pintype "passive"))
      (node (ref "J8") (pin "98") (pinfunction "B38_98") (pintype "passive"))
      (node (ref "J9") (pin "98") (pinfunction "B38_98") (pintype "passive"))
      (node (ref "R26") (pin "1") (pinfunction "1_1") (pintype "passive"))
      (node (ref "U4") (pin "14") (pinfunction "DO4+_14") (pintype "passive"))
    )
    (net (code "144") (name "/bus25_p") (class "Default")
      (node (ref "J1") (pin "97") (pinfunction "B37_97") (pintype "passive"))
      (node (ref "J10") (pin "97") (pinfunction "B37_97") (pintype "passive"))
      (node (ref "J11") (pin "97") (pinfunction "B37_97") (pintype "passive"))
      (node (ref "J12") (pin "97") (pinfunction "B37_97") (pintype "passive"))
      (node (ref "J13") (pin "97") (pinfunction "B37_97") (pintype "passive"))
      (node (ref "J14") (pin "97") (pinfunction "B37_97") (pintype "passive"))
      (node (ref "J15") (pin "97") (pinfunction "B37_97") (pintype "passive"))
      (node (ref "J16") (pin "97") (pinfunction "B37_97") (pintype "passive"))
      (node (ref "J2") (pin "97") (pinfunction "B37_97") (pintype "passive"))
      (node (ref "J3") (pin "97") (pinfunction "B37_97") (pintype "passive"))
      (node (ref "J4") (pin "97") (pinfunction "B37_97") (pintype "passive"))
      (node (ref "J5") (pin "97") (pinfunction "B37_97") (pintype "passive"))
      (node (ref "J6") (pin "97") (pinfunction "B37_97") (pintype "passive"))
      (node (ref "J7") (pin "97") (pinfunction "B37_97") (pintype "passive"))
      (node (ref "J8") (pin "97") (pinfunction "B37_97") (pintype "passive"))
      (node (ref "J9") (pin "97") (pinfunction "B37_97") (pintype "passive"))
      (node (ref "R26") (pin "2") (pinfunction "2_2") (pintype "passive"))
      (node (ref "U4") (pin "13") (pinfunction "DO4-_13") (pintype "passive"))
    )
    (net (code "145") (name "/bus26") (class "Default")
      (node (ref "P7") (pin "30") (pinfunction "30_30") (pintype "passive"))
      (node (ref "U11") (pin "1B3") (pinfunction "M2/L17p_1B3") (pintype "passive"))
      (node (ref "U4") (pin "1") (pinfunction "DI1_1") (pintype "passive"))
    )
    (net (code "146") (name "/bus26_n") (class "Default")
      (node (ref "J1") (pin "91") (pinfunction "B31_91") (pintype "passive"))
      (node (ref "J10") (pin "91") (pinfunction "B31_91") (pintype "passive"))
      (node (ref "J11") (pin "91") (pinfunction "B31_91") (pintype "passive"))
      (node (ref "J12") (pin "91") (pinfunction "B31_91") (pintype "passive"))
      (node (ref "J13") (pin "91") (pinfunction "B31_91") (pintype "passive"))
      (node (ref "J14") (pin "91") (pinfunction "B31_91") (pintype "passive"))
      (node (ref "J15") (pin "91") (pinfunction "B31_91") (pintype "passive"))
      (node (ref "J16") (pin "91") (pinfunction "B31_91") (pintype "passive"))
      (node (ref "J2") (pin "91") (pinfunction "B31_91") (pintype "passive"))
      (node (ref "J3") (pin "91") (pinfunction "B31_91") (pintype "passive"))
      (node (ref "J4") (pin "91") (pinfunction "B31_91") (pintype "passive"))
      (node (ref "J5") (pin "91") (pinfunction "B31_91") (pintype "passive"))
      (node (ref "J6") (pin "91") (pinfunction "B31_91") (pintype "passive"))
      (node (ref "J7") (pin "91") (pinfunction "B31_91") (pintype "passive"))
      (node (ref "J8") (pin "91") (pinfunction "B31_91") (pintype "passive"))
      (node (ref "J9") (pin "91") (pinfunction "B31_91") (pintype "passive"))
      (node (ref "R27") (pin "1") (pinfunction "1_1") (pintype "passive"))
      (node (ref "U4") (pin "2") (pinfunction "DO1+_2") (pintype "passive"))
    )
    (net (code "147") (name "/bus26_p") (class "Default")
      (node (ref "J1") (pin "92") (pinfunction "B32_92") (pintype "passive"))
      (node (ref "J10") (pin "92") (pinfunction "B32_92") (pintype "passive"))
      (node (ref "J11") (pin "92") (pinfunction "B32_92") (pintype "passive"))
      (node (ref "J12") (pin "92") (pinfunction "B32_92") (pintype "passive"))
      (node (ref "J13") (pin "92") (pinfunction "B32_92") (pintype "passive"))
      (node (ref "J14") (pin "92") (pinfunction "B32_92") (pintype "passive"))
      (node (ref "J15") (pin "92") (pinfunction "B32_92") (pintype "passive"))
      (node (ref "J16") (pin "92") (pinfunction "B32_92") (pintype "passive"))
      (node (ref "J2") (pin "92") (pinfunction "B32_92") (pintype "passive"))
      (node (ref "J3") (pin "92") (pinfunction "B32_92") (pintype "passive"))
      (node (ref "J4") (pin "92") (pinfunction "B32_92") (pintype "passive"))
      (node (ref "J5") (pin "92") (pinfunction "B32_92") (pintype "passive"))
      (node (ref "J6") (pin "92") (pinfunction "B32_92") (pintype "passive"))
      (node (ref "J7") (pin "92") (pinfunction "B32_92") (pintype "passive"))
      (node (ref "J8") (pin "92") (pinfunction "B32_92") (pintype "passive"))
      (node (ref "J9") (pin "92") (pinfunction "B32_92") (pintype "passive"))
      (node (ref "R27") (pin "2") (pinfunction "2_2") (pintype "passive"))
      (node (ref "U4") (pin "3") (pinfunction "DO1-_3") (pintype "passive"))
    )
    (net (code "148") (name "/bus27") (class "Default")
      (node (ref "P7") (pin "29") (pinfunction "29_29") (pintype "passive"))
      (node (ref "U11") (pin "1A37") (pinfunction "M6/L16n_1A37") (pintype "passive"))
      (node (ref "U4") (pin "7") (pinfunction "DI2_7") (pintype "passive"))
    )
    (net (code "149") (name "/bus27_n") (class "Default")
      (node (ref "J1") (pin "94") (pinfunction "B34_94") (pintype "passive"))
      (node (ref "J10") (pin "94") (pinfunction "B34_94") (pintype "passive"))
      (node (ref "J11") (pin "94") (pinfunction "B34_94") (pintype "passive"))
      (node (ref "J12") (pin "94") (pinfunction "B34_94") (pintype "passive"))
      (node (ref "J13") (pin "94") (pinfunction "B34_94") (pintype "passive"))
      (node (ref "J14") (pin "94") (pinfunction "B34_94") (pintype "passive"))
      (node (ref "J15") (pin "94") (pinfunction "B34_94") (pintype "passive"))
      (node (ref "J16") (pin "94") (pinfunction "B34_94") (pintype "passive"))
      (node (ref "J2") (pin "94") (pinfunction "B34_94") (pintype "passive"))
      (node (ref "J3") (pin "94") (pinfunction "B34_94") (pintype "passive"))
      (node (ref "J4") (pin "94") (pinfunction "B34_94") (pintype "passive"))
      (node (ref "J5") (pin "94") (pinfunction "B34_94") (pintype "passive"))
      (node (ref "J6") (pin "94") (pinfunction "B34_94") (pintype "passive"))
      (node (ref "J7") (pin "94") (pinfunction "B34_94") (pintype "passive"))
      (node (ref "J8") (pin "94") (pinfunction "B34_94") (pintype "passive"))
      (node (ref "J9") (pin "94") (pinfunction "B34_94") (pintype "passive"))
      (node (ref "R28") (pin "1") (pinfunction "1_1") (pintype "passive"))
      (node (ref "U4") (pin "6") (pinfunction "DO2+_6") (pintype "passive"))
    )
    (net (code "150") (name "/bus27_p") (class "Default")
      (node (ref "J1") (pin "93") (pinfunction "B33_93") (pintype "passive"))
      (node (ref "J10") (pin "93") (pinfunction "B33_93") (pintype "passive"))
      (node (ref "J11") (pin "93") (pinfunction "B33_93") (pintype "passive"))
      (node (ref "J12") (pin "93") (pinfunction "B33_93") (pintype "passive"))
      (node (ref "J13") (pin "93") (pinfunction "B33_93") (pintype "passive"))
      (node (ref "J14") (pin "93") (pinfunction "B33_93") (pintype "passive"))
      (node (ref "J15") (pin "93") (pinfunction "B33_93") (pintype "passive"))
      (node (ref "J16") (pin "93") (pinfunction "B33_93") (pintype "passive"))
      (node (ref "J2") (pin "93") (pinfunction "B33_93") (pintype "passive"))
      (node (ref "J3") (pin "93") (pinfunction "B33_93") (pintype "passive"))
      (node (ref "J4") (pin "93") (pinfunction "B33_93") (pintype "passive"))
      (node (ref "J5") (pin "93") (pinfunction "B33_93") (pintype "passive"))
      (node (ref "J6") (pin "93") (pinfunction "B33_93") (pintype "passive"))
      (node (ref "J7") (pin "93") (pinfunction "B33_93") (pintype "passive"))
      (node (ref "J8") (pin "93") (pinfunction "B33_93") (pintype "passive"))
      (node (ref "J9") (pin "93") (pinfunction "B33_93") (pintype "passive"))
      (node (ref "R28") (pin "2") (pinfunction "2_2") (pintype "passive"))
      (node (ref "U4") (pin "5") (pinfunction "DO2-_5") (pintype "passive"))
    )
    (net (code "151") (name "/bus28") (class "Default")
      (node (ref "P7") (pin "31") (pinfunction "31_31") (pintype "passive"))
      (node (ref "U11") (pin "1B5") (pinfunction "M1/L17n_1B5") (pintype "passive"))
      (node (ref "U3") (pin "9") (pinfunction "DI3_9") (pintype "passive"))
    )
    (net (code "152") (name "/bus28_n") (class "Default")
      (node (ref "J1") (pin "86") (pinfunction "B26_86") (pintype "passive"))
      (node (ref "J10") (pin "86") (pinfunction "B26_86") (pintype "passive"))
      (node (ref "J11") (pin "86") (pinfunction "B26_86") (pintype "passive"))
      (node (ref "J12") (pin "86") (pinfunction "B26_86") (pintype "passive"))
      (node (ref "J13") (pin "86") (pinfunction "B26_86") (pintype "passive"))
      (node (ref "J14") (pin "86") (pinfunction "B26_86") (pintype "passive"))
      (node (ref "J15") (pin "86") (pinfunction "B26_86") (pintype "passive"))
      (node (ref "J16") (pin "86") (pinfunction "B26_86") (pintype "passive"))
      (node (ref "J2") (pin "86") (pinfunction "B26_86") (pintype "passive"))
      (node (ref "J3") (pin "86") (pinfunction "B26_86") (pintype "passive"))
      (node (ref "J4") (pin "86") (pinfunction "B26_86") (pintype "passive"))
      (node (ref "J5") (pin "86") (pinfunction "B26_86") (pintype "passive"))
      (node (ref "J6") (pin "86") (pinfunction "B26_86") (pintype "passive"))
      (node (ref "J7") (pin "86") (pinfunction "B26_86") (pintype "passive"))
      (node (ref "J8") (pin "86") (pinfunction "B26_86") (pintype "passive"))
      (node (ref "J9") (pin "86") (pinfunction "B26_86") (pintype "passive"))
      (node (ref "R29") (pin "1") (pinfunction "1_1") (pintype "passive"))
      (node (ref "U3") (pin "10") (pinfunction "DO3+_10") (pintype "passive"))
    )
    (net (code "153") (name "/bus28_p") (class "Default")
      (node (ref "J1") (pin "87") (pinfunction "B27_87") (pintype "passive"))
      (node (ref "J10") (pin "87") (pinfunction "B27_87") (pintype "passive"))
      (node (ref "J11") (pin "87") (pinfunction "B27_87") (pintype "passive"))
      (node (ref "J12") (pin "87") (pinfunction "B27_87") (pintype "passive"))
      (node (ref "J13") (pin "87") (pinfunction "B27_87") (pintype "passive"))
      (node (ref "J14") (pin "87") (pinfunction "B27_87") (pintype "passive"))
      (node (ref "J15") (pin "87") (pinfunction "B27_87") (pintype "passive"))
      (node (ref "J16") (pin "87") (pinfunction "B27_87") (pintype "passive"))
      (node (ref "J2") (pin "87") (pinfunction "B27_87") (pintype "passive"))
      (node (ref "J3") (pin "87") (pinfunction "B27_87") (pintype "passive"))
      (node (ref "J4") (pin "87") (pinfunction "B27_87") (pintype "passive"))
      (node (ref "J5") (pin "87") (pinfunction "B27_87") (pintype "passive"))
      (node (ref "J6") (pin "87") (pinfunction "B27_87") (pintype "passive"))
      (node (ref "J7") (pin "87") (pinfunction "B27_87") (pintype "passive"))
      (node (ref "J8") (pin "87") (pinfunction "B27_87") (pintype "passive"))
      (node (ref "J9") (pin "87") (pinfunction "B27_87") (pintype "passive"))
      (node (ref "R29") (pin "2") (pinfunction "2_2") (pintype "passive"))
      (node (ref "U3") (pin "11") (pinfunction "DO3-_11") (pintype "passive"))
    )
    (net (code "154") (name "/bus29") (class "Default")
      (node (ref "P7") (pin "32") (pinfunction "32_32") (pintype "passive"))
      (node (ref "U11") (pin "1B4") (pinfunction "U7/B2p_1B4") (pintype "passive"))
      (node (ref "U3") (pin "15") (pinfunction "DI4_15") (pintype "passive"))
    )
    (net (code "155") (name "/bus29_n") (class "Default")
      (node (ref "J1") (pin "89") (pinfunction "B29_89") (pintype "passive"))
      (node (ref "J10") (pin "89") (pinfunction "B29_89") (pintype "passive"))
      (node (ref "J11") (pin "89") (pinfunction "B29_89") (pintype "passive"))
      (node (ref "J12") (pin "89") (pinfunction "B29_89") (pintype "passive"))
      (node (ref "J13") (pin "89") (pinfunction "B29_89") (pintype "passive"))
      (node (ref "J14") (pin "89") (pinfunction "B29_89") (pintype "passive"))
      (node (ref "J15") (pin "89") (pinfunction "B29_89") (pintype "passive"))
      (node (ref "J16") (pin "89") (pinfunction "B29_89") (pintype "passive"))
      (node (ref "J2") (pin "89") (pinfunction "B29_89") (pintype "passive"))
      (node (ref "J3") (pin "89") (pinfunction "B29_89") (pintype "passive"))
      (node (ref "J4") (pin "89") (pinfunction "B29_89") (pintype "passive"))
      (node (ref "J5") (pin "89") (pinfunction "B29_89") (pintype "passive"))
      (node (ref "J6") (pin "89") (pinfunction "B29_89") (pintype "passive"))
      (node (ref "J7") (pin "89") (pinfunction "B29_89") (pintype "passive"))
      (node (ref "J8") (pin "89") (pinfunction "B29_89") (pintype "passive"))
      (node (ref "J9") (pin "89") (pinfunction "B29_89") (pintype "passive"))
      (node (ref "R30") (pin "1") (pinfunction "1_1") (pintype "passive"))
      (node (ref "U3") (pin "14") (pinfunction "DO4+_14") (pintype "passive"))
    )
    (net (code "156") (name "/bus29_p") (class "Default")
      (node (ref "J1") (pin "88") (pinfunction "B28_88") (pintype "passive"))
      (node (ref "J10") (pin "88") (pinfunction "B28_88") (pintype "passive"))
      (node (ref "J11") (pin "88") (pinfunction "B28_88") (pintype "passive"))
      (node (ref "J12") (pin "88") (pinfunction "B28_88") (pintype "passive"))
      (node (ref "J13") (pin "88") (pinfunction "B28_88") (pintype "passive"))
      (node (ref "J14") (pin "88") (pinfunction "B28_88") (pintype "passive"))
      (node (ref "J15") (pin "88") (pinfunction "B28_88") (pintype "passive"))
      (node (ref "J16") (pin "88") (pinfunction "B28_88") (pintype "passive"))
      (node (ref "J2") (pin "88") (pinfunction "B28_88") (pintype "passive"))
      (node (ref "J3") (pin "88") (pinfunction "B28_88") (pintype "passive"))
      (node (ref "J4") (pin "88") (pinfunction "B28_88") (pintype "passive"))
      (node (ref "J5") (pin "88") (pinfunction "B28_88") (pintype "passive"))
      (node (ref "J6") (pin "88") (pinfunction "B28_88") (pintype "passive"))
      (node (ref "J7") (pin "88") (pinfunction "B28_88") (pintype "passive"))
      (node (ref "J8") (pin "88") (pinfunction "B28_88") (pintype "passive"))
      (node (ref "J9") (pin "88") (pinfunction "B28_88") (pintype "passive"))
      (node (ref "R30") (pin "2") (pinfunction "2_2") (pintype "passive"))
      (node (ref "U3") (pin "13") (pinfunction "DO4-_13") (pintype "passive"))
    )
    (net (code "157") (name "/bus30") (class "Default")
      (node (ref "P7") (pin "34") (pinfunction "34_34") (pintype "passive"))
      (node (ref "U11") (pin "1B7") (pinfunction "M4/L18p_1B7") (pintype "passive"))
      (node (ref "U3") (pin "1") (pinfunction "DI1_1") (pintype "passive"))
    )
    (net (code "158") (name "/bus30_n") (class "Default")
      (node (ref "J1") (pin "82") (pinfunction "B22_82") (pintype "passive"))
      (node (ref "J10") (pin "82") (pinfunction "B22_82") (pintype "passive"))
      (node (ref "J11") (pin "82") (pinfunction "B22_82") (pintype "passive"))
      (node (ref "J12") (pin "82") (pinfunction "B22_82") (pintype "passive"))
      (node (ref "J13") (pin "82") (pinfunction "B22_82") (pintype "passive"))
      (node (ref "J14") (pin "82") (pinfunction "B22_82") (pintype "passive"))
      (node (ref "J15") (pin "82") (pinfunction "B22_82") (pintype "passive"))
      (node (ref "J16") (pin "82") (pinfunction "B22_82") (pintype "passive"))
      (node (ref "J2") (pin "82") (pinfunction "B22_82") (pintype "passive"))
      (node (ref "J3") (pin "82") (pinfunction "B22_82") (pintype "passive"))
      (node (ref "J4") (pin "82") (pinfunction "B22_82") (pintype "passive"))
      (node (ref "J5") (pin "82") (pinfunction "B22_82") (pintype "passive"))
      (node (ref "J6") (pin "82") (pinfunction "B22_82") (pintype "passive"))
      (node (ref "J7") (pin "82") (pinfunction "B22_82") (pintype "passive"))
      (node (ref "J8") (pin "82") (pinfunction "B22_82") (pintype "passive"))
      (node (ref "J9") (pin "82") (pinfunction "B22_82") (pintype "passive"))
      (node (ref "R31") (pin "1") (pinfunction "1_1") (pintype "passive"))
      (node (ref "U3") (pin "2") (pinfunction "DO1+_2") (pintype "passive"))
    )
    (net (code "159") (name "/bus30_p") (class "Default")
      (node (ref "J1") (pin "83") (pinfunction "B23_83") (pintype "passive"))
      (node (ref "J10") (pin "83") (pinfunction "B23_83") (pintype "passive"))
      (node (ref "J11") (pin "83") (pinfunction "B23_83") (pintype "passive"))
      (node (ref "J12") (pin "83") (pinfunction "B23_83") (pintype "passive"))
      (node (ref "J13") (pin "83") (pinfunction "B23_83") (pintype "passive"))
      (node (ref "J14") (pin "83") (pinfunction "B23_83") (pintype "passive"))
      (node (ref "J15") (pin "83") (pinfunction "B23_83") (pintype "passive"))
      (node (ref "J16") (pin "83") (pinfunction "B23_83") (pintype "passive"))
      (node (ref "J2") (pin "83") (pinfunction "B23_83") (pintype "passive"))
      (node (ref "J3") (pin "83") (pinfunction "B23_83") (pintype "passive"))
      (node (ref "J4") (pin "83") (pinfunction "B23_83") (pintype "passive"))
      (node (ref "J5") (pin "83") (pinfunction "B23_83") (pintype "passive"))
      (node (ref "J6") (pin "83") (pinfunction "B23_83") (pintype "passive"))
      (node (ref "J7") (pin "83") (pinfunction "B23_83") (pintype "passive"))
      (node (ref "J8") (pin "83") (pinfunction "B23_83") (pintype "passive"))
      (node (ref "J9") (pin "83") (pinfunction "B23_83") (pintype "passive"))
      (node (ref "R31") (pin "2") (pinfunction "2_2") (pintype "passive"))
      (node (ref "U3") (pin "3") (pinfunction "DO1-_3") (pintype "passive"))
    )
    (net (code "160") (name "/bus31") (class "Default")
      (node (ref "P7") (pin "33") (pinfunction "33_33") (pintype "passive"))
      (node (ref "U11") (pin "1B6") (pinfunction "U8/B2n_1B6") (pintype "passive"))
      (node (ref "U3") (pin "7") (pinfunction "DI2_7") (pintype "passive"))
    )
    (net (code "161") (name "/bus31_n") (class "Default")
      (node (ref "J1") (pin "85") (pinfunction "B25_85") (pintype "passive"))
      (node (ref "J10") (pin "85") (pinfunction "B25_85") (pintype "passive"))
      (node (ref "J11") (pin "85") (pinfunction "B25_85") (pintype "passive"))
      (node (ref "J12") (pin "85") (pinfunction "B25_85") (pintype "passive"))
      (node (ref "J13") (pin "85") (pinfunction "B25_85") (pintype "passive"))
      (node (ref "J14") (pin "85") (pinfunction "B25_85") (pintype "passive"))
      (node (ref "J15") (pin "85") (pinfunction "B25_85") (pintype "passive"))
      (node (ref "J16") (pin "85") (pinfunction "B25_85") (pintype "passive"))
      (node (ref "J2") (pin "85") (pinfunction "B25_85") (pintype "passive"))
      (node (ref "J3") (pin "85") (pinfunction "B25_85") (pintype "passive"))
      (node (ref "J4") (pin "85") (pinfunction "B25_85") (pintype "passive"))
      (node (ref "J5") (pin "85") (pinfunction "B25_85") (pintype "passive"))
      (node (ref "J6") (pin "85") (pinfunction "B25_85") (pintype "passive"))
      (node (ref "J7") (pin "85") (pinfunction "B25_85") (pintype "passive"))
      (node (ref "J8") (pin "85") (pinfunction "B25_85") (pintype "passive"))
      (node (ref "J9") (pin "85") (pinfunction "B25_85") (pintype "passive"))
      (node (ref "R32") (pin "1") (pinfunction "1_1") (pintype "passive"))
      (node (ref "U3") (pin "6") (pinfunction "DO2+_6") (pintype "passive"))
    )
    (net (code "162") (name "/bus31_p") (class "Default")
      (node (ref "J1") (pin "84") (pinfunction "B24_84") (pintype "passive"))
      (node (ref "J10") (pin "84") (pinfunction "B24_84") (pintype "passive"))
      (node (ref "J11") (pin "84") (pinfunction "B24_84") (pintype "passive"))
      (node (ref "J12") (pin "84") (pinfunction "B24_84") (pintype "passive"))
      (node (ref "J13") (pin "84") (pinfunction "B24_84") (pintype "passive"))
      (node (ref "J14") (pin "84") (pinfunction "B24_84") (pintype "passive"))
      (node (ref "J15") (pin "84") (pinfunction "B24_84") (pintype "passive"))
      (node (ref "J16") (pin "84") (pinfunction "B24_84") (pintype "passive"))
      (node (ref "J2") (pin "84") (pinfunction "B24_84") (pintype "passive"))
      (node (ref "J3") (pin "84") (pinfunction "B24_84") (pintype "passive"))
      (node (ref "J4") (pin "84") (pinfunction "B24_84") (pintype "passive"))
      (node (ref "J5") (pin "84") (pinfunction "B24_84") (pintype "passive"))
      (node (ref "J6") (pin "84") (pinfunction "B24_84") (pintype "passive"))
      (node (ref "J7") (pin "84") (pinfunction "B24_84") (pintype "passive"))
      (node (ref "J8") (pin "84") (pinfunction "B24_84") (pintype "passive"))
      (node (ref "J9") (pin "84") (pinfunction "B24_84") (pintype "passive"))
      (node (ref "R32") (pin "2") (pinfunction "2_2") (pintype "passive"))
      (node (ref "U3") (pin "5") (pinfunction "DO2-_5") (pintype "passive"))
    )
    (net (code "163") (name "/bus32") (class "Default")
      (node (ref "P9") (pin "6") (pinfunction "6_6") (pintype "passive"))
      (node (ref "U11") (pin "1B13") (pinfunction "N1/L19n_1B13") (pintype "passive"))
      (node (ref "U2") (pin "11") (pinfunction "YD_11") (pintype "passive"))
    )
    (net (code "164") (name "/bus32_n") (class "Default")
      (node (ref "J1") (pin "15") (pinfunction "A15_15") (pintype "passive"))
      (node (ref "J10") (pin "15") (pinfunction "A15_15") (pintype "passive"))
      (node (ref "J11") (pin "15") (pinfunction "A15_15") (pintype "passive"))
      (node (ref "J12") (pin "15") (pinfunction "A15_15") (pintype "passive"))
      (node (ref "J13") (pin "15") (pinfunction "A15_15") (pintype "passive"))
      (node (ref "J14") (pin "15") (pinfunction "A15_15") (pintype "passive"))
      (node (ref "J15") (pin "15") (pinfunction "A15_15") (pintype "passive"))
      (node (ref "J16") (pin "15") (pinfunction "A15_15") (pintype "passive"))
      (node (ref "J2") (pin "15") (pinfunction "A15_15") (pintype "passive"))
      (node (ref "J3") (pin "15") (pinfunction "A15_15") (pintype "passive"))
      (node (ref "J4") (pin "15") (pinfunction "A15_15") (pintype "passive"))
      (node (ref "J5") (pin "15") (pinfunction "A15_15") (pintype "passive"))
      (node (ref "J6") (pin "15") (pinfunction "A15_15") (pintype "passive"))
      (node (ref "J7") (pin "15") (pinfunction "A15_15") (pintype "passive"))
      (node (ref "J8") (pin "15") (pinfunction "A15_15") (pintype "passive"))
      (node (ref "J9") (pin "15") (pinfunction "A15_15") (pintype "passive"))
      (node (ref "R33") (pin "1") (pinfunction "1_1") (pintype "passive"))
      (node (ref "U2") (pin "10") (pinfunction "D+_10") (pintype "passive"))
    )
    (net (code "165") (name "/bus32_p") (class "Default")
      (node (ref "J1") (pin "16") (pinfunction "A16_16") (pintype "passive"))
      (node (ref "J10") (pin "16") (pinfunction "A16_16") (pintype "passive"))
      (node (ref "J11") (pin "16") (pinfunction "A16_16") (pintype "passive"))
      (node (ref "J12") (pin "16") (pinfunction "A16_16") (pintype "passive"))
      (node (ref "J13") (pin "16") (pinfunction "A16_16") (pintype "passive"))
      (node (ref "J14") (pin "16") (pinfunction "A16_16") (pintype "passive"))
      (node (ref "J15") (pin "16") (pinfunction "A16_16") (pintype "passive"))
      (node (ref "J16") (pin "16") (pinfunction "A16_16") (pintype "passive"))
      (node (ref "J2") (pin "16") (pinfunction "A16_16") (pintype "passive"))
      (node (ref "J3") (pin "16") (pinfunction "A16_16") (pintype "passive"))
      (node (ref "J4") (pin "16") (pinfunction "A16_16") (pintype "passive"))
      (node (ref "J5") (pin "16") (pinfunction "A16_16") (pintype "passive"))
      (node (ref "J6") (pin "16") (pinfunction "A16_16") (pintype "passive"))
      (node (ref "J7") (pin "16") (pinfunction "A16_16") (pintype "passive"))
      (node (ref "J8") (pin "16") (pinfunction "A16_16") (pintype "passive"))
      (node (ref "J9") (pin "16") (pinfunction "A16_16") (pintype "passive"))
      (node (ref "R33") (pin "2") (pinfunction "2_2") (pintype "passive"))
      (node (ref "U2") (pin "9") (pinfunction "D-_9") (pintype "passive"))
    )
    (net (code "166") (name "/bus33") (class "Default")
      (node (ref "P9") (pin "5") (pinfunction "5_5") (pintype "passive"))
      (node (ref "U11") (pin "1B12") (pinfunction "AA5/B5p_1B12") (pintype "passive"))
      (node (ref "U2") (pin "13") (pinfunction "YB_13") (pintype "passive"))
    )
    (net (code "167") (name "/bus33_n") (class "Default")
      (node (ref "J1") (pin "14") (pinfunction "A14_14") (pintype "passive"))
      (node (ref "J10") (pin "14") (pinfunction "A14_14") (pintype "passive"))
      (node (ref "J11") (pin "14") (pinfunction "A14_14") (pintype "passive"))
      (node (ref "J12") (pin "14") (pinfunction "A14_14") (pintype "passive"))
      (node (ref "J13") (pin "14") (pinfunction "A14_14") (pintype "passive"))
      (node (ref "J14") (pin "14") (pinfunction "A14_14") (pintype "passive"))
      (node (ref "J15") (pin "14") (pinfunction "A14_14") (pintype "passive"))
      (node (ref "J16") (pin "14") (pinfunction "A14_14") (pintype "passive"))
      (node (ref "J2") (pin "14") (pinfunction "A14_14") (pintype "passive"))
      (node (ref "J3") (pin "14") (pinfunction "A14_14") (pintype "passive"))
      (node (ref "J4") (pin "14") (pinfunction "A14_14") (pintype "passive"))
      (node (ref "J5") (pin "14") (pinfunction "A14_14") (pintype "passive"))
      (node (ref "J6") (pin "14") (pinfunction "A14_14") (pintype "passive"))
      (node (ref "J7") (pin "14") (pinfunction "A14_14") (pintype "passive"))
      (node (ref "J8") (pin "14") (pinfunction "A14_14") (pintype "passive"))
      (node (ref "J9") (pin "14") (pinfunction "A14_14") (pintype "passive"))
      (node (ref "R34") (pin "1") (pinfunction "1_1") (pintype "passive"))
      (node (ref "U2") (pin "14") (pinfunction "B+_14") (pintype "passive"))
    )
    (net (code "168") (name "/bus33_p") (class "Default")
      (node (ref "J1") (pin "13") (pinfunction "A13_13") (pintype "passive"))
      (node (ref "J10") (pin "13") (pinfunction "A13_13") (pintype "passive"))
      (node (ref "J11") (pin "13") (pinfunction "A13_13") (pintype "passive"))
      (node (ref "J12") (pin "13") (pinfunction "A13_13") (pintype "passive"))
      (node (ref "J13") (pin "13") (pinfunction "A13_13") (pintype "passive"))
      (node (ref "J14") (pin "13") (pinfunction "A13_13") (pintype "passive"))
      (node (ref "J15") (pin "13") (pinfunction "A13_13") (pintype "passive"))
      (node (ref "J16") (pin "13") (pinfunction "A13_13") (pintype "passive"))
      (node (ref "J2") (pin "13") (pinfunction "A13_13") (pintype "passive"))
      (node (ref "J3") (pin "13") (pinfunction "A13_13") (pintype "passive"))
      (node (ref "J4") (pin "13") (pinfunction "A13_13") (pintype "passive"))
      (node (ref "J5") (pin "13") (pinfunction "A13_13") (pintype "passive"))
      (node (ref "J6") (pin "13") (pinfunction "A13_13") (pintype "passive"))
      (node (ref "J7") (pin "13") (pinfunction "A13_13") (pintype "passive"))
      (node (ref "J8") (pin "13") (pinfunction "A13_13") (pintype "passive"))
      (node (ref "J9") (pin "13") (pinfunction "A13_13") (pintype "passive"))
      (node (ref "R34") (pin "2") (pinfunction "2_2") (pintype "passive"))
      (node (ref "U2") (pin "15") (pinfunction "B-_15") (pintype "passive"))
    )
    (net (code "169") (name "/bus34") (class "Default")
      (node (ref "P9") (pin "8") (pinfunction "8_8") (pintype "passive"))
      (node (ref "U11") (pin "1B15") (pinfunction "P2/L20p_1B15") (pintype "passive"))
      (node (ref "U2") (pin "3") (pinfunction "YA_3") (pintype "passive"))
    )
    (net (code "170") (name "/bus34_n") (class "Default")
      (node (ref "J1") (pin "19") (pinfunction "A19_19") (pintype "passive"))
      (node (ref "J10") (pin "19") (pinfunction "A19_19") (pintype "passive"))
      (node (ref "J11") (pin "19") (pinfunction "A19_19") (pintype "passive"))
      (node (ref "J12") (pin "19") (pinfunction "A19_19") (pintype "passive"))
      (node (ref "J13") (pin "19") (pinfunction "A19_19") (pintype "passive"))
      (node (ref "J14") (pin "19") (pinfunction "A19_19") (pintype "passive"))
      (node (ref "J15") (pin "19") (pinfunction "A19_19") (pintype "passive"))
      (node (ref "J16") (pin "19") (pinfunction "A19_19") (pintype "passive"))
      (node (ref "J2") (pin "19") (pinfunction "A19_19") (pintype "passive"))
      (node (ref "J3") (pin "19") (pinfunction "A19_19") (pintype "passive"))
      (node (ref "J4") (pin "19") (pinfunction "A19_19") (pintype "passive"))
      (node (ref "J5") (pin "19") (pinfunction "A19_19") (pintype "passive"))
      (node (ref "J6") (pin "19") (pinfunction "A19_19") (pintype "passive"))
      (node (ref "J7") (pin "19") (pinfunction "A19_19") (pintype "passive"))
      (node (ref "J8") (pin "19") (pinfunction "A19_19") (pintype "passive"))
      (node (ref "J9") (pin "19") (pinfunction "A19_19") (pintype "passive"))
      (node (ref "R35") (pin "1") (pinfunction "1_1") (pintype "passive"))
      (node (ref "U2") (pin "2") (pinfunction "A+_2") (pintype "passive"))
    )
    (net (code "171") (name "/bus34_p") (class "Default")
      (node (ref "J1") (pin "20") (pinfunction "A20_20") (pintype "passive"))
      (node (ref "J10") (pin "20") (pinfunction "A20_20") (pintype "passive"))
      (node (ref "J11") (pin "20") (pinfunction "A20_20") (pintype "passive"))
      (node (ref "J12") (pin "20") (pinfunction "A20_20") (pintype "passive"))
      (node (ref "J13") (pin "20") (pinfunction "A20_20") (pintype "passive"))
      (node (ref "J14") (pin "20") (pinfunction "A20_20") (pintype "passive"))
      (node (ref "J15") (pin "20") (pinfunction "A20_20") (pintype "passive"))
      (node (ref "J16") (pin "20") (pinfunction "A20_20") (pintype "passive"))
      (node (ref "J2") (pin "20") (pinfunction "A20_20") (pintype "passive"))
      (node (ref "J3") (pin "20") (pinfunction "A20_20") (pintype "passive"))
      (node (ref "J4") (pin "20") (pinfunction "A20_20") (pintype "passive"))
      (node (ref "J5") (pin "20") (pinfunction "A20_20") (pintype "passive"))
      (node (ref "J6") (pin "20") (pinfunction "A20_20") (pintype "passive"))
      (node (ref "J7") (pin "20") (pinfunction "A20_20") (pintype "passive"))
      (node (ref "J8") (pin "20") (pinfunction "A20_20") (pintype "passive"))
      (node (ref "J9") (pin "20") (pinfunction "A20_20") (pintype "passive"))
      (node (ref "R35") (pin "2") (pinfunction "2_2") (pintype "passive"))
      (node (ref "U2") (pin "1") (pinfunction "A-_1") (pintype "passive"))
    )
    (net (code "172") (name "/bus35") (class "Default")
      (node (ref "P9") (pin "7") (pinfunction "7_7") (pintype "passive"))
      (node (ref "U11") (pin "1B14") (pinfunction "AA6/B5n_1B14") (pintype "passive"))
      (node (ref "U2") (pin "5") (pinfunction "YC_5") (pintype "passive"))
    )
    (net (code "173") (name "/bus35_n") (class "Default")
      (node (ref "J1") (pin "18") (pinfunction "A18_18") (pintype "passive"))
      (node (ref "J10") (pin "18") (pinfunction "A18_18") (pintype "passive"))
      (node (ref "J11") (pin "18") (pinfunction "A18_18") (pintype "passive"))
      (node (ref "J12") (pin "18") (pinfunction "A18_18") (pintype "passive"))
      (node (ref "J13") (pin "18") (pinfunction "A18_18") (pintype "passive"))
      (node (ref "J14") (pin "18") (pinfunction "A18_18") (pintype "passive"))
      (node (ref "J15") (pin "18") (pinfunction "A18_18") (pintype "passive"))
      (node (ref "J16") (pin "18") (pinfunction "A18_18") (pintype "passive"))
      (node (ref "J2") (pin "18") (pinfunction "A18_18") (pintype "passive"))
      (node (ref "J3") (pin "18") (pinfunction "A18_18") (pintype "passive"))
      (node (ref "J4") (pin "18") (pinfunction "A18_18") (pintype "passive"))
      (node (ref "J5") (pin "18") (pinfunction "A18_18") (pintype "passive"))
      (node (ref "J6") (pin "18") (pinfunction "A18_18") (pintype "passive"))
      (node (ref "J7") (pin "18") (pinfunction "A18_18") (pintype "passive"))
      (node (ref "J8") (pin "18") (pinfunction "A18_18") (pintype "passive"))
      (node (ref "J9") (pin "18") (pinfunction "A18_18") (pintype "passive"))
      (node (ref "R36") (pin "1") (pinfunction "1_1") (pintype "passive"))
      (node (ref "U2") (pin "6") (pinfunction "C+_6") (pintype "passive"))
    )
    (net (code "174") (name "/bus35_p") (class "Default")
      (node (ref "J1") (pin "17") (pinfunction "A17_17") (pintype "passive"))
      (node (ref "J10") (pin "17") (pinfunction "A17_17") (pintype "passive"))
      (node (ref "J11") (pin "17") (pinfunction "A17_17") (pintype "passive"))
      (node (ref "J12") (pin "17") (pinfunction "A17_17") (pintype "passive"))
      (node (ref "J13") (pin "17") (pinfunction "A17_17") (pintype "passive"))
      (node (ref "J14") (pin "17") (pinfunction "A17_17") (pintype "passive"))
      (node (ref "J15") (pin "17") (pinfunction "A17_17") (pintype "passive"))
      (node (ref "J16") (pin "17") (pinfunction "A17_17") (pintype "passive"))
      (node (ref "J2") (pin "17") (pinfunction "A17_17") (pintype "passive"))
      (node (ref "J3") (pin "17") (pinfunction "A17_17") (pintype "passive"))
      (node (ref "J4") (pin "17") (pinfunction "A17_17") (pintype "passive"))
      (node (ref "J5") (pin "17") (pinfunction "A17_17") (pintype "passive"))
      (node (ref "J6") (pin "17") (pinfunction "A17_17") (pintype "passive"))
      (node (ref "J7") (pin "17") (pinfunction "A17_17") (pintype "passive"))
      (node (ref "J8") (pin "17") (pinfunction "A17_17") (pintype "passive"))
      (node (ref "J9") (pin "17") (pinfunction "A17_17") (pintype "passive"))
      (node (ref "R36") (pin "2") (pinfunction "2_2") (pintype "passive"))
      (node (ref "U2") (pin "7") (pinfunction "C-_7") (pintype "passive"))
    )
    (net (code "175") (name "/bus36") (class "Default")
      (node (ref "P9") (pin "2") (pinfunction "2_2") (pintype "passive"))
      (node (ref "U1") (pin "11") (pinfunction "YD_11") (pintype "passive"))
      (node (ref "U11") (pin "1B9") (pinfunction "M3/L18n_1B9") (pintype "passive"))
    )
    (net (code "176") (name "/bus36_n") (class "Default")
      (node (ref "J1") (pin "78") (pinfunction "B18_78") (pintype "passive"))
      (node (ref "J10") (pin "78") (pinfunction "B18_78") (pintype "passive"))
      (node (ref "J11") (pin "78") (pinfunction "B18_78") (pintype "passive"))
      (node (ref "J12") (pin "78") (pinfunction "B18_78") (pintype "passive"))
      (node (ref "J13") (pin "78") (pinfunction "B18_78") (pintype "passive"))
      (node (ref "J14") (pin "78") (pinfunction "B18_78") (pintype "passive"))
      (node (ref "J15") (pin "78") (pinfunction "B18_78") (pintype "passive"))
      (node (ref "J16") (pin "78") (pinfunction "B18_78") (pintype "passive"))
      (node (ref "J2") (pin "78") (pinfunction "B18_78") (pintype "passive"))
      (node (ref "J3") (pin "78") (pinfunction "B18_78") (pintype "passive"))
      (node (ref "J4") (pin "78") (pinfunction "B18_78") (pintype "passive"))
      (node (ref "J5") (pin "78") (pinfunction "B18_78") (pintype "passive"))
      (node (ref "J6") (pin "78") (pinfunction "B18_78") (pintype "passive"))
      (node (ref "J7") (pin "78") (pinfunction "B18_78") (pintype "passive"))
      (node (ref "J8") (pin "78") (pinfunction "B18_78") (pintype "passive"))
      (node (ref "J9") (pin "78") (pinfunction "B18_78") (pintype "passive"))
      (node (ref "R37") (pin "1") (pinfunction "1_1") (pintype "passive"))
      (node (ref "U1") (pin "10") (pinfunction "D+_10") (pintype "passive"))
    )
    (net (code "177") (name "/bus36_p") (class "Default")
      (node (ref "J1") (pin "77") (pinfunction "B17_77") (pintype "passive"))
      (node (ref "J10") (pin "77") (pinfunction "B17_77") (pintype "passive"))
      (node (ref "J11") (pin "77") (pinfunction "B17_77") (pintype "passive"))
      (node (ref "J12") (pin "77") (pinfunction "B17_77") (pintype "passive"))
      (node (ref "J13") (pin "77") (pinfunction "B17_77") (pintype "passive"))
      (node (ref "J14") (pin "77") (pinfunction "B17_77") (pintype "passive"))
      (node (ref "J15") (pin "77") (pinfunction "B17_77") (pintype "passive"))
      (node (ref "J16") (pin "77") (pinfunction "B17_77") (pintype "passive"))
      (node (ref "J2") (pin "77") (pinfunction "B17_77") (pintype "passive"))
      (node (ref "J3") (pin "77") (pinfunction "B17_77") (pintype "passive"))
      (node (ref "J4") (pin "77") (pinfunction "B17_77") (pintype "passive"))
      (node (ref "J5") (pin "77") (pinfunction "B17_77") (pintype "passive"))
      (node (ref "J6") (pin "77") (pinfunction "B17_77") (pintype "passive"))
      (node (ref "J7") (pin "77") (pinfunction "B17_77") (pintype "passive"))
      (node (ref "J8") (pin "77") (pinfunction "B17_77") (pintype "passive"))
      (node (ref "J9") (pin "77") (pinfunction "B17_77") (pintype "passive"))
      (node (ref "R37") (pin "2") (pinfunction "2_2") (pintype "passive"))
      (node (ref "U1") (pin "9") (pinfunction "D-_9") (pintype "passive"))
    )
    (net (code "178") (name "/bus37") (class "Default")
      (node (ref "P9") (pin "1") (pinfunction "1_1") (pintype "passive"))
      (node (ref "U1") (pin "13") (pinfunction "YB_13") (pintype "passive"))
      (node (ref "U11") (pin "1B8") (pinfunction "W6/B4p_1B8") (pintype "passive"))
    )
    (net (code "179") (name "/bus37_n") (class "Default")
      (node (ref "J1") (pin "79") (pinfunction "B19_79") (pintype "passive"))
      (node (ref "J10") (pin "79") (pinfunction "B19_79") (pintype "passive"))
      (node (ref "J11") (pin "79") (pinfunction "B19_79") (pintype "passive"))
      (node (ref "J12") (pin "79") (pinfunction "B19_79") (pintype "passive"))
      (node (ref "J13") (pin "79") (pinfunction "B19_79") (pintype "passive"))
      (node (ref "J14") (pin "79") (pinfunction "B19_79") (pintype "passive"))
      (node (ref "J15") (pin "79") (pinfunction "B19_79") (pintype "passive"))
      (node (ref "J16") (pin "79") (pinfunction "B19_79") (pintype "passive"))
      (node (ref "J2") (pin "79") (pinfunction "B19_79") (pintype "passive"))
      (node (ref "J3") (pin "79") (pinfunction "B19_79") (pintype "passive"))
      (node (ref "J4") (pin "79") (pinfunction "B19_79") (pintype "passive"))
      (node (ref "J5") (pin "79") (pinfunction "B19_79") (pintype "passive"))
      (node (ref "J6") (pin "79") (pinfunction "B19_79") (pintype "passive"))
      (node (ref "J7") (pin "79") (pinfunction "B19_79") (pintype "passive"))
      (node (ref "J8") (pin "79") (pinfunction "B19_79") (pintype "passive"))
      (node (ref "J9") (pin "79") (pinfunction "B19_79") (pintype "passive"))
      (node (ref "R38") (pin "1") (pinfunction "1_1") (pintype "passive"))
      (node (ref "U1") (pin "14") (pinfunction "B+_14") (pintype "passive"))
    )
    (net (code "180") (name "/bus37_p") (class "Default")
      (node (ref "J1") (pin "80") (pinfunction "B20_80") (pintype "passive"))
      (node (ref "J10") (pin "80") (pinfunction "B20_80") (pintype "passive"))
      (node (ref "J11") (pin "80") (pinfunction "B20_80") (pintype "passive"))
      (node (ref "J12") (pin "80") (pinfunction "B20_80") (pintype "passive"))
      (node (ref "J13") (pin "80") (pinfunction "B20_80") (pintype "passive"))
      (node (ref "J14") (pin "80") (pinfunction "B20_80") (pintype "passive"))
      (node (ref "J15") (pin "80") (pinfunction "B20_80") (pintype "passive"))
      (node (ref "J16") (pin "80") (pinfunction "B20_80") (pintype "passive"))
      (node (ref "J2") (pin "80") (pinfunction "B20_80") (pintype "passive"))
      (node (ref "J3") (pin "80") (pinfunction "B20_80") (pintype "passive"))
      (node (ref "J4") (pin "80") (pinfunction "B20_80") (pintype "passive"))
      (node (ref "J5") (pin "80") (pinfunction "B20_80") (pintype "passive"))
      (node (ref "J6") (pin "80") (pinfunction "B20_80") (pintype "passive"))
      (node (ref "J7") (pin "80") (pinfunction "B20_80") (pintype "passive"))
      (node (ref "J8") (pin "80") (pinfunction "B20_80") (pintype "passive"))
      (node (ref "J9") (pin "80") (pinfunction "B20_80") (pintype "passive"))
      (node (ref "R38") (pin "2") (pinfunction "2_2") (pintype "passive"))
      (node (ref "U1") (pin "15") (pinfunction "B-_15") (pintype "passive"))
    )
    (net (code "181") (name "/bus38") (class "Default")
      (node (ref "P9") (pin "4") (pinfunction "4_4") (pintype "passive"))
      (node (ref "U1") (pin "3") (pinfunction "YA_3") (pintype "passive"))
      (node (ref "U11") (pin "1B11") (pinfunction "N2/L19p_1B11") (pintype "passive"))
    )
    (net (code "182") (name "/bus38_n") (class "Default")
      (node (ref "J1") (pin "74") (pinfunction "B14_74") (pintype "passive"))
      (node (ref "J10") (pin "74") (pinfunction "B14_74") (pintype "passive"))
      (node (ref "J11") (pin "74") (pinfunction "B14_74") (pintype "passive"))
      (node (ref "J12") (pin "74") (pinfunction "B14_74") (pintype "passive"))
      (node (ref "J13") (pin "74") (pinfunction "B14_74") (pintype "passive"))
      (node (ref "J14") (pin "74") (pinfunction "B14_74") (pintype "passive"))
      (node (ref "J15") (pin "74") (pinfunction "B14_74") (pintype "passive"))
      (node (ref "J16") (pin "74") (pinfunction "B14_74") (pintype "passive"))
      (node (ref "J2") (pin "74") (pinfunction "B14_74") (pintype "passive"))
      (node (ref "J3") (pin "74") (pinfunction "B14_74") (pintype "passive"))
      (node (ref "J4") (pin "74") (pinfunction "B14_74") (pintype "passive"))
      (node (ref "J5") (pin "74") (pinfunction "B14_74") (pintype "passive"))
      (node (ref "J6") (pin "74") (pinfunction "B14_74") (pintype "passive"))
      (node (ref "J7") (pin "74") (pinfunction "B14_74") (pintype "passive"))
      (node (ref "J8") (pin "74") (pinfunction "B14_74") (pintype "passive"))
      (node (ref "J9") (pin "74") (pinfunction "B14_74") (pintype "passive"))
      (node (ref "R39") (pin "1") (pinfunction "1_1") (pintype "passive"))
      (node (ref "U1") (pin "2") (pinfunction "A+_2") (pintype "passive"))
    )
    (net (code "183") (name "/bus38_p") (class "Default")
      (node (ref "J1") (pin "73") (pinfunction "B13_73") (pintype "passive"))
      (node (ref "J10") (pin "73") (pinfunction "B13_73") (pintype "passive"))
      (node (ref "J11") (pin "73") (pinfunction "B13_73") (pintype "passive"))
      (node (ref "J12") (pin "73") (pinfunction "B13_73") (pintype "passive"))
      (node (ref "J13") (pin "73") (pinfunction "B13_73") (pintype "passive"))
      (node (ref "J14") (pin "73") (pinfunction "B13_73") (pintype "passive"))
      (node (ref "J15") (pin "73") (pinfunction "B13_73") (pintype "passive"))
      (node (ref "J16") (pin "73") (pinfunction "B13_73") (pintype "passive"))
      (node (ref "J2") (pin "73") (pinfunction "B13_73") (pintype "passive"))
      (node (ref "J3") (pin "73") (pinfunction "B13_73") (pintype "passive"))
      (node (ref "J4") (pin "73") (pinfunction "B13_73") (pintype "passive"))
      (node (ref "J5") (pin "73") (pinfunction "B13_73") (pintype "passive"))
      (node (ref "J6") (pin "73") (pinfunction "B13_73") (pintype "passive"))
      (node (ref "J7") (pin "73") (pinfunction "B13_73") (pintype "passive"))
      (node (ref "J8") (pin "73") (pinfunction "B13_73") (pintype "passive"))
      (node (ref "J9") (pin "73") (pinfunction "B13_73") (pintype "passive"))
      (node (ref "R39") (pin "2") (pinfunction "2_2") (pintype "passive"))
      (node (ref "U1") (pin "1") (pinfunction "A-_1") (pintype "passive"))
    )
    (net (code "184") (name "/bus39") (class "Default")
      (node (ref "P9") (pin "3") (pinfunction "3_3") (pintype "passive"))
      (node (ref "U1") (pin "5") (pinfunction "YC_5") (pintype "passive"))
      (node (ref "U11") (pin "1B10") (pinfunction "V7/B4n_1B10") (pintype "passive"))
    )
    (net (code "185") (name "/bus39_n") (class "Default")
      (node (ref "J1") (pin "75") (pinfunction "B15_75") (pintype "passive"))
      (node (ref "J10") (pin "75") (pinfunction "B15_75") (pintype "passive"))
      (node (ref "J11") (pin "75") (pinfunction "B15_75") (pintype "passive"))
      (node (ref "J12") (pin "75") (pinfunction "B15_75") (pintype "passive"))
      (node (ref "J13") (pin "75") (pinfunction "B15_75") (pintype "passive"))
      (node (ref "J14") (pin "75") (pinfunction "B15_75") (pintype "passive"))
      (node (ref "J15") (pin "75") (pinfunction "B15_75") (pintype "passive"))
      (node (ref "J16") (pin "75") (pinfunction "B15_75") (pintype "passive"))
      (node (ref "J2") (pin "75") (pinfunction "B15_75") (pintype "passive"))
      (node (ref "J3") (pin "75") (pinfunction "B15_75") (pintype "passive"))
      (node (ref "J4") (pin "75") (pinfunction "B15_75") (pintype "passive"))
      (node (ref "J5") (pin "75") (pinfunction "B15_75") (pintype "passive"))
      (node (ref "J6") (pin "75") (pinfunction "B15_75") (pintype "passive"))
      (node (ref "J7") (pin "75") (pinfunction "B15_75") (pintype "passive"))
      (node (ref "J8") (pin "75") (pinfunction "B15_75") (pintype "passive"))
      (node (ref "J9") (pin "75") (pinfunction "B15_75") (pintype "passive"))
      (node (ref "R40") (pin "1") (pinfunction "1_1") (pintype "passive"))
      (node (ref "U1") (pin "6") (pinfunction "C+_6") (pintype "passive"))
    )
    (net (code "186") (name "/bus39_p") (class "Default")
      (node (ref "J1") (pin "76") (pinfunction "B16_76") (pintype "passive"))
      (node (ref "J10") (pin "76") (pinfunction "B16_76") (pintype "passive"))
      (node (ref "J11") (pin "76") (pinfunction "B16_76") (pintype "passive"))
      (node (ref "J12") (pin "76") (pinfunction "B16_76") (pintype "passive"))
      (node (ref "J13") (pin "76") (pinfunction "B16_76") (pintype "passive"))
      (node (ref "J14") (pin "76") (pinfunction "B16_76") (pintype "passive"))
      (node (ref "J15") (pin "76") (pinfunction "B16_76") (pintype "passive"))
      (node (ref "J16") (pin "76") (pinfunction "B16_76") (pintype "passive"))
      (node (ref "J2") (pin "76") (pinfunction "B16_76") (pintype "passive"))
      (node (ref "J3") (pin "76") (pinfunction "B16_76") (pintype "passive"))
      (node (ref "J4") (pin "76") (pinfunction "B16_76") (pintype "passive"))
      (node (ref "J5") (pin "76") (pinfunction "B16_76") (pintype "passive"))
      (node (ref "J6") (pin "76") (pinfunction "B16_76") (pintype "passive"))
      (node (ref "J7") (pin "76") (pinfunction "B16_76") (pintype "passive"))
      (node (ref "J8") (pin "76") (pinfunction "B16_76") (pintype "passive"))
      (node (ref "J9") (pin "76") (pinfunction "B16_76") (pintype "passive"))
      (node (ref "R40") (pin "2") (pinfunction "2_2") (pintype "passive"))
      (node (ref "U1") (pin "7") (pinfunction "C-_7") (pintype "passive"))
    )
    (net (code "187") (name "3.3V_dig") (class "Default")
      (node (ref "C1") (pin "1") (pinfunction "1_1") (pintype "passive"))
      (node (ref "C2") (pin "1") (pinfunction "1_1") (pintype "passive"))
      (node (ref "C39") (pin "1") (pinfunction "1_1") (pintype "passive"))
      (node (ref "C40") (pin "1") (pinfunction "1_1") (pintype "passive"))
      (node (ref "C41") (pin "1") (pinfunction "1_1") (pintype "passive"))
      (node (ref "C42") (pin "1") (pinfunction "1_1") (pintype "passive"))
      (node (ref "C43") (pin "1") (pinfunction "1_1") (pintype "passive"))
      (node (ref "C44") (pin "1") (pinfunction "1_1") (pintype "passive"))
      (node (ref "C45") (pin "1") (pinfunction "1_1") (pintype "passive"))
      (node (ref "C46") (pin "1") (pinfunction "1_1") (pintype "passive"))
      (node (ref "C47") (pin "2") (pinfunction "2_2") (pintype "passive"))
      (node (ref "C48") (pin "2") (pinfunction "2_2") (pintype "passive"))
      (node (ref "C49") (pin "2") (pinfunction "2_2") (pintype "passive"))
      (node (ref "C50") (pin "2") (pinfunction "2_2") (pintype "passive"))
      (node (ref "P7") (pin "2") (pinfunction "2_2") (pintype "passive"))
      (node (ref "P7") (pin "4") (pinfunction "4_4") (pintype "passive"))
      (node (ref "P7") (pin "6") (pinfunction "6_6") (pintype "passive"))
      (node (ref "U1") (pin "12") (pinfunction "ENBD_12") (pintype "passive"))
      (node (ref "U1") (pin "16") (pinfunction "Vcc_16") (pintype "passive"))
      (node (ref "U1") (pin "4") (pinfunction "EAC_4") (pintype "passive"))
      (node (ref "U10") (pin "16") (pinfunction "Vcc_16") (pintype "passive"))
      (node (ref "U10") (pin "4") (pinfunction "EN_4") (pintype "passive"))
      (node (ref "U11") (pin "1A1") (pinfunction "3.3V_1A1") (pintype "passive"))
      (node (ref "U11") (pin "1C1") (pinfunction "3.3V_1C1") (pintype "passive"))
      (node (ref "U12") (pin "5") (pinfunction "DIR_5") (pintype "passive"))
      (node (ref "U12") (pin "6") (pinfunction "VCCB_6") (pintype "passive"))
      (node (ref "U13") (pin "5") (pinfunction "DIR_5") (pintype "passive"))
      (node (ref "U13") (pin "6") (pinfunction "VCCB_6") (pintype "passive"))
      (node (ref "U14") (pin "5") (pinfunction "DIR_5") (pintype "passive"))
      (node (ref "U14") (pin "6") (pinfunction "VCCB_6") (pintype "passive"))
      (node (ref "U15") (pin "5") (pinfunction "DIR_5") (pintype "passive"))
      (node (ref "U15") (pin "6") (pinfunction "VCCB_6") (pintype "passive"))
      (node (ref "U2") (pin "12") (pinfunction "ENBD_12") (pintype "passive"))
      (node (ref "U2") (pin "16") (pinfunction "Vcc_16") (pintype "passive"))
      (node (ref "U2") (pin "4") (pinfunction "EAC_4") (pintype "passive"))
      (node (ref "U3") (pin "16") (pinfunction "Vcc_16") (pintype "passive"))
      (node (ref "U3") (pin "4") (pinfunction "EN_4") (pintype "passive"))
      (node (ref "U4") (pin "16") (pinfunction "Vcc_16") (pintype "passive"))
      (node (ref "U4") (pin "4") (pinfunction "EN_4") (pintype "passive"))
      (node (ref "U5") (pin "16") (pinfunction "Vcc_16") (pintype "passive"))
      (node (ref "U5") (pin "4") (pinfunction "EN_4") (pintype "passive"))
      (node (ref "U6") (pin "16") (pinfunction "Vcc_16") (pintype "passive"))
      (node (ref "U6") (pin "4") (pinfunction "EN_4") (pintype "passive"))
      (node (ref "U7") (pin "16") (pinfunction "Vcc_16") (pintype "passive"))
      (node (ref "U7") (pin "4") (pinfunction "EN_4") (pintype "passive"))
      (node (ref "U8") (pin "16") (pinfunction "Vcc_16") (pintype "passive"))
      (node (ref "U8") (pin "4") (pinfunction "EN_4") (pintype "passive"))
      (node (ref "U9") (pin "16") (pinfunction "Vcc_16") (pintype "passive"))
      (node (ref "U9") (pin "4") (pinfunction "EN_4") (pintype "passive"))
    )
    (net (code "188") (name "5V_ANA_BUS") (class "Default")
      (node (ref "C16") (pin "1") (pinfunction "1_1") (pintype "passive"))
      (node (ref "C18") (pin "1") (pinfunction "1_1") (pintype "passive"))
      (node (ref "C20") (pin "1") (pinfunction "1_1") (pintype "passive"))
      (node (ref "C22") (pin "1") (pinfunction "1_1") (pintype "passive"))
      (node (ref "C25") (pin "2") (pinfunction "2_2") (pintype "passive"))
      (node (ref "C26") (pin "2") (pinfunction "2_2") (pintype "passive"))
      (node (ref "C29") (pin "2") (pinfunction "2_2") (pintype "passive"))
      (node (ref "C30") (pin "2") (pinfunction "2_2") (pintype "passive"))
      (node (ref "C33") (pin "2") (pinfunction "2_2") (pintype "passive"))
      (node (ref "C34") (pin "2") (pinfunction "2_2") (pintype "passive"))
      (node (ref "C37") (pin "2") (pinfunction "2_2") (pintype "passive"))
      (node (ref "C38") (pin "2") (pinfunction "2_2") (pintype "passive"))
      (node (ref "J1") (pin "118") (pinfunction "B58_118") (pintype "passive"))
      (node (ref "J1") (pin "58") (pinfunction "A58_58") (pintype "passive"))
      (node (ref "J10") (pin "118") (pinfunction "B58_118") (pintype "passive"))
      (node (ref "J10") (pin "58") (pinfunction "A58_58") (pintype "passive"))
      (node (ref "J11") (pin "118") (pinfunction "B58_118") (pintype "passive"))
      (node (ref "J11") (pin "58") (pinfunction "A58_58") (pintype "passive"))
      (node (ref "J12") (pin "118") (pinfunction "B58_118") (pintype "passive"))
      (node (ref "J12") (pin "58") (pinfunction "A58_58") (pintype "passive"))
      (node (ref "J13") (pin "118") (pinfunction "B58_118") (pintype "passive"))
      (node (ref "J13") (pin "58") (pinfunction "A58_58") (pintype "passive"))
      (node (ref "J14") (pin "118") (pinfunction "B58_118") (pintype "passive"))
      (node (ref "J14") (pin "58") (pinfunction "A58_58") (pintype "passive"))
      (node (ref "J15") (pin "118") (pinfunction "B58_118") (pintype "passive"))
      (node (ref "J15") (pin "58") (pinfunction "A58_58") (pintype "passive"))
      (node (ref "J16") (pin "118") (pinfunction "B58_118") (pintype "passive"))
      (node (ref "J16") (pin "58") (pinfunction "A58_58") (pintype "passive"))
      (node (ref "J2") (pin "118") (pinfunction "B58_118") (pintype "passive"))
      (node (ref "J2") (pin "58") (pinfunction "A58_58") (pintype "passive"))
      (node (ref "J3") (pin "118") (pinfunction "B58_118") (pintype "passive"))
      (node (ref "J3") (pin "58") (pinfunction "A58_58") (pintype "passive"))
      (node (ref "J4") (pin "118") (pinfunction "B58_118") (pintype "passive"))
      (node (ref "J4") (pin "58") (pinfunction "A58_58") (pintype "passive"))
      (node (ref "J5") (pin "118") (pinfunction "B58_118") (pintype "passive"))
      (node (ref "J5") (pin "58") (pinfunction "A58_58") (pintype "passive"))
      (node (ref "J6") (pin "118") (pinfunction "B58_118") (pintype "passive"))
      (node (ref "J6") (pin "58") (pinfunction "A58_58") (pintype "passive"))
      (node (ref "J7") (pin "118") (pinfunction "B58_118") (pintype "passive"))
      (node (ref "J7") (pin "58") (pinfunction "A58_58") (pintype "passive"))
      (node (ref "J8") (pin "118") (pinfunction "B58_118") (pintype "passive"))
      (node (ref "J8") (pin "58") (pinfunction "A58_58") (pintype "passive"))
      (node (ref "J9") (pin "118") (pinfunction "B58_118") (pintype "passive"))
      (node (ref "J9") (pin "58") (pinfunction "A58_58") (pintype "passive"))
    )
    (net (code "189") (name "5V_DIG_BUS") (class "Default")
      (node (ref "C10") (pin "2") (pinfunction "2_2") (pintype "passive"))
      (node (ref "C11") (pin "2") (pinfunction "2_2") (pintype "passive"))
      (node (ref "C12") (pin "2") (pinfunction "2_2") (pintype "passive"))
      (node (ref "C13") (pin "2") (pinfunction "2_2") (pintype "passive"))
      (node (ref "C14") (pin "2") (pinfunction "2_2") (pintype "passive"))
      (node (ref "C3") (pin "1") (pinfunction "1_1") (pintype "passive"))
      (node (ref "C4") (pin "1") (pinfunction "1_1") (pintype "passive"))
      (node (ref "C5") (pin "1") (pinfunction "1_1") (pintype "passive"))
      (node (ref "C6") (pin "1") (pinfunction "1_1") (pintype "passive"))
      (node (ref "C7") (pin "2") (pinfunction "2_2") (pintype "passive"))
      (node (ref "C8") (pin "2") (pinfunction "2_2") (pintype "passive"))
      (node (ref "C9") (pin "2") (pinfunction "2_2") (pintype "passive"))
      (node (ref "J1") (pin "1") (pinfunction "A1_1") (pintype "passive"))
      (node (ref "J1") (pin "61") (pinfunction "B1_61") (pintype "passive"))
      (node (ref "J10") (pin "1") (pinfunction "A1_1") (pintype "passive"))
      (node (ref "J10") (pin "61") (pinfunction "B1_61") (pintype "passive"))
      (node (ref "J11") (pin "1") (pinfunction "A1_1") (pintype "passive"))
      (node (ref "J11") (pin "61") (pinfunction "B1_61") (pintype "passive"))
      (node (ref "J12") (pin "1") (pinfunction "A1_1") (pintype "passive"))
      (node (ref "J12") (pin "61") (pinfunction "B1_61") (pintype "passive"))
      (node (ref "J13") (pin "1") (pinfunction "A1_1") (pintype "passive"))
      (node (ref "J13") (pin "61") (pinfunction "B1_61") (pintype "passive"))
      (node (ref "J14") (pin "1") (pinfunction "A1_1") (pintype "passive"))
      (node (ref "J14") (pin "61") (pinfunction "B1_61") (pintype "passive"))
      (node (ref "J15") (pin "1") (pinfunction "A1_1") (pintype "passive"))
      (node (ref "J15") (pin "61") (pinfunction "B1_61") (pintype "passive"))
      (node (ref "J16") (pin "1") (pinfunction "A1_1") (pintype "passive"))
      (node (ref "J16") (pin "61") (pinfunction "B1_61") (pintype "passive"))
      (node (ref "J2") (pin "1") (pinfunction "A1_1") (pintype "passive"))
      (node (ref "J2") (pin "61") (pinfunction "B1_61") (pintype "passive"))
      (node (ref "J3") (pin "1") (pinfunction "A1_1") (pintype "passive"))
      (node (ref "J3") (pin "61") (pinfunction "B1_61") (pintype "passive"))
      (node (ref "J4") (pin "1") (pinfunction "A1_1") (pintype "passive"))
      (node (ref "J4") (pin "61") (pinfunction "B1_61") (pintype "passive"))
      (node (ref "J5") (pin "1") (pinfunction "A1_1") (pintype "passive"))
      (node (ref "J5") (pin "61") (pinfunction "B1_61") (pintype "passive"))
      (node (ref "J6") (pin "1") (pinfunction "A1_1") (pintype "passive"))
      (node (ref "J6") (pin "61") (pinfunction "B1_61") (pintype "passive"))
      (node (ref "J7") (pin "1") (pinfunction "A1_1") (pintype "passive"))
      (node (ref "J7") (pin "61") (pinfunction "B1_61") (pintype "passive"))
      (node (ref "J8") (pin "1") (pinfunction "A1_1") (pintype "passive"))
      (node (ref "J8") (pin "61") (pinfunction "B1_61") (pintype "passive"))
      (node (ref "J9") (pin "1") (pinfunction "A1_1") (pintype "passive"))
      (node (ref "J9") (pin "61") (pinfunction "B1_61") (pintype "passive"))
      (node (ref "U12") (pin "1") (pinfunction "VCCA_1") (pintype "passive"))
      (node (ref "U13") (pin "1") (pinfunction "VCCA_1") (pintype "passive"))
      (node (ref "U14") (pin "1") (pinfunction "VCCA_1") (pintype "passive"))
      (node (ref "U15") (pin "1") (pinfunction "VCCA_1") (pintype "passive"))
    )
    (net (code "190") (name "8V_BUS") (class "Default")
      (node (ref "C15") (pin "1") (pinfunction "1_1") (pintype "passive"))
      (node (ref "C17") (pin "1") (pinfunction "1_1") (pintype "passive"))
      (node (ref "C19") (pin "1") (pinfunction "1_1") (pintype "passive"))
      (node (ref "C21") (pin "1") (pinfunction "1_1") (pintype "passive"))
      (node (ref "C23") (pin "2") (pinfunction "2_2") (pintype "passive"))
      (node (ref "C24") (pin "2") (pinfunction "2_2") (pintype "passive"))
      (node (ref "C27") (pin "2") (pinfunction "2_2") (pintype "passive"))
      (node (ref "C28") (pin "2") (pinfunction "2_2") (pintype "passive"))
      (node (ref "C31") (pin "2") (pinfunction "2_2") (pintype "passive"))
      (node (ref "C32") (pin "2") (pinfunction "2_2") (pintype "passive"))
      (node (ref "C35") (pin "2") (pinfunction "2_2") (pintype "passive"))
      (node (ref "C36") (pin "2") (pinfunction "2_2") (pintype "passive"))
      (node (ref "J1") (pin "120") (pinfunction "B60_120") (pintype "passive"))
      (node (ref "J1") (pin "60") (pinfunction "A60_60") (pintype "passive"))
      (node (ref "J10") (pin "120") (pinfunction "B60_120") (pintype "passive"))
      (node (ref "J10") (pin "60") (pinfunction "A60_60") (pintype "passive"))
      (node (ref "J11") (pin "120") (pinfunction "B60_120") (pintype "passive"))
      (node (ref "J11") (pin "60") (pinfunction "A60_60") (pintype "passive"))
      (node (ref "J12") (pin "120") (pinfunction "B60_120") (pintype "passive"))
      (node (ref "J12") (pin "60") (pinfunction "A60_60") (pintype "passive"))
      (node (ref "J13") (pin "120") (pinfunction "B60_120") (pintype "passive"))
      (node (ref "J13") (pin "60") (pinfunction "A60_60") (pintype "passive"))
      (node (ref "J14") (pin "120") (pinfunction "B60_120") (pintype "passive"))
      (node (ref "J14") (pin "60") (pinfunction "A60_60") (pintype "passive"))
      (node (ref "J15") (pin "120") (pinfunction "B60_120") (pintype "passive"))
      (node (ref "J15") (pin "60") (pinfunction "A60_60") (pintype "passive"))
      (node (ref "J16") (pin "120") (pinfunction "B60_120") (pintype "passive"))
      (node (ref "J16") (pin "60") (pinfunction "A60_60") (pintype "passive"))
      (node (ref "J2") (pin "120") (pinfunction "B60_120") (pintype "passive"))
      (node (ref "J2") (pin "60") (pinfunction "A60_60") (pintype "passive"))
      (node (ref "J3") (pin "120") (pinfunction "B60_120") (pintype "passive"))
      (node (ref "J3") (pin "60") (pinfunction "A60_60") (pintype "passive"))
      (node (ref "J4") (pin "120") (pinfunction "B60_120") (pintype "passive"))
      (node (ref "J4") (pin "60") (pinfunction "A60_60") (pintype "passive"))
      (node (ref "J5") (pin "120") (pinfunction "B60_120") (pintype "passive"))
      (node (ref "J5") (pin "60") (pinfunction "A60_60") (pintype "passive"))
      (node (ref "J6") (pin "120") (pinfunction "B60_120") (pintype "passive"))
      (node (ref "J6") (pin "60") (pinfunction "A60_60") (pintype "passive"))
      (node (ref "J7") (pin "120") (pinfunction "B60_120") (pintype "passive"))
      (node (ref "J7") (pin "60") (pinfunction "A60_60") (pintype "passive"))
      (node (ref "J8") (pin "120") (pinfunction "B60_120") (pintype "passive"))
      (node (ref "J8") (pin "60") (pinfunction "A60_60") (pintype "passive"))
      (node (ref "J9") (pin "120") (pinfunction "B60_120") (pintype "passive"))
      (node (ref "J9") (pin "60") (pinfunction "A60_60") (pintype "passive"))
    )
    (net (code "191") (name "AGND") (class "Default")
      (node (ref "C15") (pin "2") (pinfunction "2_2") (pintype "passive"))
      (node (ref "C16") (pin "2") (pinfunction "2_2") (pintype "passive"))
      (node (ref "C17") (pin "2") (pinfunction "2_2") (pintype "passive"))
      (node (ref "C18") (pin "2") (pinfunction "2_2") (pintype "passive"))
      (node (ref "C19") (pin "2") (pinfunction "2_2") (pintype "passive"))
      (node (ref "C20") (pin "2") (pinfunction "2_2") (pintype "passive"))
      (node (ref "C21") (pin "2") (pinfunction "2_2") (pintype "passive"))
      (node (ref "C22") (pin "2") (pinfunction "2_2") (pintype "passive"))
      (node (ref "C23") (pin "1") (pinfunction "1_1") (pintype "passive"))
      (node (ref "C24") (pin "1") (pinfunction "1_1") (pintype "passive"))
      (node (ref "C25") (pin "1") (pinfunction "1_1") (pintype "passive"))
      (node (ref "C26") (pin "1") (pinfunction "1_1") (pintype "passive"))
      (node (ref "C27") (pin "1") (pinfunction "1_1") (pintype "passive"))
      (node (ref "C28") (pin "1") (pinfunction "1_1") (pintype "passive"))
      (node (ref "C29") (pin "1") (pinfunction "1_1") (pintype "passive"))
      (node (ref "C30") (pin "1") (pinfunction "1_1") (pintype "passive"))
      (node (ref "C31") (pin "1") (pinfunction "1_1") (pintype "passive"))
      (node (ref "C32") (pin "1") (pinfunction "1_1") (pintype "passive"))
      (node (ref "C33") (pin "1") (pinfunction "1_1") (pintype "passive"))
      (node (ref "C34") (pin "1") (pinfunction "1_1") (pintype "passive"))
      (node (ref "C35") (pin "1") (pinfunction "1_1") (pintype "passive"))
      (node (ref "C36") (pin "1") (pinfunction "1_1") (pintype "passive"))
      (node (ref "C37") (pin "1") (pinfunction "1_1") (pintype "passive"))
      (node (ref "C38") (pin "1") (pinfunction "1_1") (pintype "passive"))
      (node (ref "J1") (pin "117") (pinfunction "B57_117") (pintype "passive"))
      (node (ref "J1") (pin "119") (pinfunction "B59_119") (pintype "passive"))
      (node (ref "J1") (pin "57") (pinfunction "A57_57") (pintype "passive"))
      (node (ref "J1") (pin "59") (pinfunction "A59_59") (pintype "passive"))
      (node (ref "J10") (pin "117") (pinfunction "B57_117") (pintype "passive"))
      (node (ref "J10") (pin "119") (pinfunction "B59_119") (pintype "passive"))
      (node (ref "J10") (pin "57") (pinfunction "A57_57") (pintype "passive"))
      (node (ref "J10") (pin "59") (pinfunction "A59_59") (pintype "passive"))
      (node (ref "J11") (pin "117") (pinfunction "B57_117") (pintype "passive"))
      (node (ref "J11") (pin "119") (pinfunction "B59_119") (pintype "passive"))
      (node (ref "J11") (pin "57") (pinfunction "A57_57") (pintype "passive"))
      (node (ref "J11") (pin "59") (pinfunction "A59_59") (pintype "passive"))
      (node (ref "J12") (pin "117") (pinfunction "B57_117") (pintype "passive"))
      (node (ref "J12") (pin "119") (pinfunction "B59_119") (pintype "passive"))
      (node (ref "J12") (pin "57") (pinfunction "A57_57") (pintype "passive"))
      (node (ref "J12") (pin "59") (pinfunction "A59_59") (pintype "passive"))
      (node (ref "J13") (pin "117") (pinfunction "B57_117") (pintype "passive"))
      (node (ref "J13") (pin "119") (pinfunction "B59_119") (pintype "passive"))
      (node (ref "J13") (pin "57") (pinfunction "A57_57") (pintype "passive"))
      (node (ref "J13") (pin "59") (pinfunction "A59_59") (pintype "passive"))
      (node (ref "J14") (pin "117") (pinfunction "B57_117") (pintype "passive"))
      (node (ref "J14") (pin "119") (pinfunction "B59_119") (pintype "passive"))
      (node (ref "J14") (pin "57") (pinfunction "A57_57") (pintype "passive"))
      (node (ref "J14") (pin "59") (pinfunction "A59_59") (pintype "passive"))
      (node (ref "J15") (pin "117") (pinfunction "B57_117") (pintype "passive"))
      (node (ref "J15") (pin "119") (pinfunction "B59_119") (pintype "passive"))
      (node (ref "J15") (pin "57") (pinfunction "A57_57") (pintype "passive"))
      (node (ref "J15") (pin "59") (pinfunction "A59_59") (pintype "passive"))
      (node (ref "J16") (pin "117") (pinfunction "B57_117") (pintype "passive"))
      (node (ref "J16") (pin "119") (pinfunction "B59_119") (pintype "passive"))
      (node (ref "J16") (pin "57") (pinfunction "A57_57") (pintype "passive"))
      (node (ref "J16") (pin "59") (pinfunction "A59_59") (pintype "passive"))
      (node (ref "J2") (pin "117") (pinfunction "B57_117") (pintype "passive"))
      (node (ref "J2") (pin "119") (pinfunction "B59_119") (pintype "passive"))
      (node (ref "J2") (pin "57") (pinfunction "A57_57") (pintype "passive"))
      (node (ref "J2") (pin "59") (pinfunction "A59_59") (pintype "passive"))
      (node (ref "J3") (pin "117") (pinfunction "B57_117") (pintype "passive"))
      (node (ref "J3") (pin "119") (pinfunction "B59_119") (pintype "passive"))
      (node (ref "J3") (pin "57") (pinfunction "A57_57") (pintype "passive"))
      (node (ref "J3") (pin "59") (pinfunction "A59_59") (pintype "passive"))
      (node (ref "J4") (pin "117") (pinfunction "B57_117") (pintype "passive"))
      (node (ref "J4") (pin "119") (pinfunction "B59_119") (pintype "passive"))
      (node (ref "J4") (pin "57") (pinfunction "A57_57") (pintype "passive"))
      (node (ref "J4") (pin "59") (pinfunction "A59_59") (pintype "passive"))
      (node (ref "J5") (pin "117") (pinfunction "B57_117") (pintype "passive"))
      (node (ref "J5") (pin "119") (pinfunction "B59_119") (pintype "passive"))
      (node (ref "J5") (pin "57") (pinfunction "A57_57") (pintype "passive"))
      (node (ref "J5") (pin "59") (pinfunction "A59_59") (pintype "passive"))
      (node (ref "J6") (pin "117") (pinfunction "B57_117") (pintype "passive"))
      (node (ref "J6") (pin "119") (pinfunction "B59_119") (pintype "passive"))
      (node (ref "J6") (pin "57") (pinfunction "A57_57") (pintype "passive"))
      (node (ref "J6") (pin "59") (pinfunction "A59_59") (pintype "passive"))
      (node (ref "J7") (pin "117") (pinfunction "B57_117") (pintype "passive"))
      (node (ref "J7") (pin "119") (pinfunction "B59_119") (pintype "passive"))
      (node (ref "J7") (pin "57") (pinfunction "A57_57") (pintype "passive"))
      (node (ref "J7") (pin "59") (pinfunction "A59_59") (pintype "passive"))
      (node (ref "J8") (pin "117") (pinfunction "B57_117") (pintype "passive"))
      (node (ref "J8") (pin "119") (pinfunction "B59_119") (pintype "passive"))
      (node (ref "J8") (pin "57") (pinfunction "A57_57") (pintype "passive"))
      (node (ref "J8") (pin "59") (pinfunction "A59_59") (pintype "passive"))
      (node (ref "J9") (pin "117") (pinfunction "B57_117") (pintype "passive"))
      (node (ref "J9") (pin "119") (pinfunction "B59_119") (pintype "passive"))
      (node (ref "J9") (pin "57") (pinfunction "A57_57") (pintype "passive"))
      (node (ref "J9") (pin "59") (pinfunction "A59_59") (pintype "passive"))
    )
    (net (code "192") (name "DGND") (class "Default")
      (node (ref "C1") (pin "2") (pinfunction "2_2") (pintype "passive"))
      (node (ref "C10") (pin "1") (pinfunction "1_1") (pintype "passive"))
      (node (ref "C11") (pin "1") (pinfunction "1_1") (pintype "passive"))
      (node (ref "C12") (pin "1") (pinfunction "1_1") (pintype "passive"))
      (node (ref "C13") (pin "1") (pinfunction "1_1") (pintype "passive"))
      (node (ref "C14") (pin "1") (pinfunction "1_1") (pintype "passive"))
      (node (ref "C2") (pin "2") (pinfunction "2_2") (pintype "passive"))
      (node (ref "C3") (pin "2") (pinfunction "2_2") (pintype "passive"))
      (node (ref "C39") (pin "2") (pinfunction "2_2") (pintype "passive"))
      (node (ref "C4") (pin "2") (pinfunction "2_2") (pintype "passive"))
      (node (ref "C40") (pin "2") (pinfunction "2_2") (pintype "passive"))
      (node (ref "C41") (pin "2") (pinfunction "2_2") (pintype "passive"))
      (node (ref "C42") (pin "2") (pinfunction "2_2") (pintype "passive"))
      (node (ref "C43") (pin "2") (pinfunction "2_2") (pintype "passive"))
      (node (ref "C44") (pin "2") (pinfunction "2_2") (pintype "passive"))
      (node (ref "C45") (pin "2") (pinfunction "2_2") (pintype "passive"))
      (node (ref "C46") (pin "2") (pinfunction "2_2") (pintype "passive"))
      (node (ref "C47") (pin "1") (pinfunction "1_1") (pintype "passive"))
      (node (ref "C48") (pin "1") (pinfunction "1_1") (pintype "passive"))
      (node (ref "C49") (pin "1") (pinfunction "1_1") (pintype "passive"))
      (node (ref "C5") (pin "2") (pinfunction "2_2") (pintype "passive"))
      (node (ref "C50") (pin "1") (pinfunction "1_1") (pintype "passive"))
      (node (ref "C6") (pin "2") (pinfunction "2_2") (pintype "passive"))
      (node (ref "C7") (pin "1") (pinfunction "1_1") (pintype "passive"))
      (node (ref "C8") (pin "1") (pinfunction "1_1") (pintype "passive"))
      (node (ref "C9") (pin "1") (pinfunction "1_1") (pintype "passive"))
      (node (ref "J1") (pin "10") (pinfunction "A10_10") (pintype "passive"))
      (node (ref "J1") (pin "108") (pinfunction "B48_108") (pintype "passive"))
      (node (ref "J1") (pin "11") (pinfunction "A11_11") (pintype "passive"))
      (node (ref "J1") (pin "12") (pinfunction "A12_12") (pintype "passive"))
      (node (ref "J1") (pin "2") (pinfunction "A2_2") (pintype "passive"))
      (node (ref "J1") (pin "21") (pinfunction "A21_21") (pintype "passive"))
      (node (ref "J1") (pin "3") (pinfunction "A3_3") (pintype "passive"))
      (node (ref "J1") (pin "30") (pinfunction "A30_30") (pintype "passive"))
      (node (ref "J1") (pin "39") (pinfunction "A39_39") (pintype "passive"))
      (node (ref "J1") (pin "4") (pinfunction "A4_4") (pintype "passive"))
      (node (ref "J1") (pin "48") (pinfunction "A48_48") (pintype "passive"))
      (node (ref "J1") (pin "5") (pinfunction "A5_5") (pintype "passive"))
      (node (ref "J1") (pin "6") (pinfunction "A6_6") (pintype "passive"))
      (node (ref "J1") (pin "62") (pinfunction "B2_62") (pintype "passive"))
      (node (ref "J1") (pin "63") (pinfunction "B3_63") (pintype "passive"))
      (node (ref "J1") (pin "64") (pinfunction "B4_64") (pintype "passive"))
      (node (ref "J1") (pin "65") (pinfunction "B5_65") (pintype "passive"))
      (node (ref "J1") (pin "66") (pinfunction "B6_66") (pintype "passive"))
      (node (ref "J1") (pin "67") (pinfunction "B7_67") (pintype "passive"))
      (node (ref "J1") (pin "68") (pinfunction "B8_68") (pintype "passive"))
      (node (ref "J1") (pin "69") (pinfunction "B9_69") (pintype "passive"))
      (node (ref "J1") (pin "7") (pinfunction "A7_7") (pintype "passive"))
      (node (ref "J1") (pin "70") (pinfunction "B10_70") (pintype "passive"))
      (node (ref "J1") (pin "71") (pinfunction "B11_71") (pintype "passive"))
      (node (ref "J1") (pin "72") (pinfunction "B12_72") (pintype "passive"))
      (node (ref "J1") (pin "8") (pinfunction "A8_8") (pintype "passive"))
      (node (ref "J1") (pin "81") (pinfunction "B21_81") (pintype "passive"))
      (node (ref "J1") (pin "9") (pinfunction "A9_9") (pintype "passive"))
      (node (ref "J1") (pin "90") (pinfunction "B30_90") (pintype "passive"))
      (node (ref "J1") (pin "99") (pinfunction "B39_99") (pintype "passive"))
      (node (ref "J10") (pin "10") (pinfunction "A10_10") (pintype "passive"))
      (node (ref "J10") (pin "108") (pinfunction "B48_108") (pintype "passive"))
      (node (ref "J10") (pin "11") (pinfunction "A11_11") (pintype "passive"))
      (node (ref "J10") (pin "12") (pinfunction "A12_12") (pintype "passive"))
      (node (ref "J10") (pin "2") (pinfunction "A2_2") (pintype "passive"))
      (node (ref "J10") (pin "21") (pinfunction "A21_21") (pintype "passive"))
      (node (ref "J10") (pin "3") (pinfunction "A3_3") (pintype "passive"))
      (node (ref "J10") (pin "30") (pinfunction "A30_30") (pintype "passive"))
      (node (ref "J10") (pin "39") (pinfunction "A39_39") (pintype "passive"))
      (node (ref "J10") (pin "4") (pinfunction "A4_4") (pintype "passive"))
      (node (ref "J10") (pin "48") (pinfunction "A48_48") (pintype "passive"))
      (node (ref "J10") (pin "5") (pinfunction "A5_5") (pintype "passive"))
      (node (ref "J10") (pin "6") (pinfunction "A6_6") (pintype "passive"))
      (node (ref "J10") (pin "62") (pinfunction "B2_62") (pintype "passive"))
      (node (ref "J10") (pin "63") (pinfunction "B3_63") (pintype "passive"))
      (node (ref "J10") (pin "64") (pinfunction "B4_64") (pintype "passive"))
      (node (ref "J10") (pin "65") (pinfunction "B5_65") (pintype "passive"))
      (node (ref "J10") (pin "66") (pinfunction "B6_66") (pintype "passive"))
      (node (ref "J10") (pin "67") (pinfunction "B7_67") (pintype "passive"))
      (node (ref "J10") (pin "68") (pinfunction "B8_68") (pintype "passive"))
      (node (ref "J10") (pin "69") (pinfunction "B9_69") (pintype "passive"))
      (node (ref "J10") (pin "7") (pinfunction "A7_7") (pintype "passive"))
      (node (ref "J10") (pin "70") (pinfunction "B10_70") (pintype "passive"))
      (node (ref "J10") (pin "71") (pinfunction "B11_71") (pintype "passive"))
      (node (ref "J10") (pin "72") (pinfunction "B12_72") (pintype "passive"))
      (node (ref "J10") (pin "8") (pinfunction "A8_8") (pintype "passive"))
      (node (ref "J10") (pin "81") (pinfunction "B21_81") (pintype "passive"))
      (node (ref "J10") (pin "9") (pinfunction "A9_9") (pintype "passive"))
      (node (ref "J10") (pin "90") (pinfunction "B30_90") (pintype "passive"))
      (node (ref "J10") (pin "99") (pinfunction "B39_99") (pintype "passive"))
      (node (ref "J11") (pin "10") (pinfunction "A10_10") (pintype "passive"))
      (node (ref "J11") (pin "108") (pinfunction "B48_108") (pintype "passive"))
      (node (ref "J11") (pin "11") (pinfunction "A11_11") (pintype "passive"))
      (node (ref "J11") (pin "12") (pinfunction "A12_12") (pintype "passive"))
      (node (ref "J11") (pin "2") (pinfunction "A2_2") (pintype "passive"))
      (node (ref "J11") (pin "21") (pinfunction "A21_21") (pintype "passive"))
      (node (ref "J11") (pin "3") (pinfunction "A3_3") (pintype "passive"))
      (node (ref "J11") (pin "30") (pinfunction "A30_30") (pintype "passive"))
      (node (ref "J11") (pin "39") (pinfunction "A39_39") (pintype "passive"))
      (node (ref "J11") (pin "4") (pinfunction "A4_4") (pintype "passive"))
      (node (ref "J11") (pin "48") (pinfunction "A48_48") (pintype "passive"))
      (node (ref "J11") (pin "5") (pinfunction "A5_5") (pintype "passive"))
      (node (ref "J11") (pin "6") (pinfunction "A6_6") (pintype "passive"))
      (node (ref "J11") (pin "62") (pinfunction "B2_62") (pintype "passive"))
      (node (ref "J11") (pin "63") (pinfunction "B3_63") (pintype "passive"))
      (node (ref "J11") (pin "64") (pinfunction "B4_64") (pintype "passive"))
      (node (ref "J11") (pin "65") (pinfunction "B5_65") (pintype "passive"))
      (node (ref "J11") (pin "66") (pinfunction "B6_66") (pintype "passive"))
      (node (ref "J11") (pin "67") (pinfunction "B7_67") (pintype "passive"))
      (node (ref "J11") (pin "68") (pinfunction "B8_68") (pintype "passive"))
      (node (ref "J11") (pin "69") (pinfunction "B9_69") (pintype "passive"))
      (node (ref "J11") (pin "7") (pinfunction "A7_7") (pintype "passive"))
      (node (ref "J11") (pin "70") (pinfunction "B10_70") (pintype "passive"))
      (node (ref "J11") (pin "71") (pinfunction "B11_71") (pintype "passive"))
      (node (ref "J11") (pin "72") (pinfunction "B12_72") (pintype "passive"))
      (node (ref "J11") (pin "8") (pinfunction "A8_8") (pintype "passive"))
      (node (ref "J11") (pin "81") (pinfunction "B21_81") (pintype "passive"))
      (node (ref "J11") (pin "9") (pinfunction "A9_9") (pintype "passive"))
      (node (ref "J11") (pin "90") (pinfunction "B30_90") (pintype "passive"))
      (node (ref "J11") (pin "99") (pinfunction "B39_99") (pintype "passive"))
      (node (ref "J12") (pin "10") (pinfunction "A10_10") (pintype "passive"))
      (node (ref "J12") (pin "108") (pinfunction "B48_108") (pintype "passive"))
      (node (ref "J12") (pin "11") (pinfunction "A11_11") (pintype "passive"))
      (node (ref "J12") (pin "12") (pinfunction "A12_12") (pintype "passive"))
      (node (ref "J12") (pin "2") (pinfunction "A2_2") (pintype "passive"))
      (node (ref "J12") (pin "21") (pinfunction "A21_21") (pintype "passive"))
      (node (ref "J12") (pin "3") (pinfunction "A3_3") (pintype "passive"))
      (node (ref "J12") (pin "30") (pinfunction "A30_30") (pintype "passive"))
      (node (ref "J12") (pin "39") (pinfunction "A39_39") (pintype "passive"))
      (node (ref "J12") (pin "4") (pinfunction "A4_4") (pintype "passive"))
      (node (ref "J12") (pin "48") (pinfunction "A48_48") (pintype "passive"))
      (node (ref "J12") (pin "5") (pinfunction "A5_5") (pintype "passive"))
      (node (ref "J12") (pin "6") (pinfunction "A6_6") (pintype "passive"))
      (node (ref "J12") (pin "62") (pinfunction "B2_62") (pintype "passive"))
      (node (ref "J12") (pin "63") (pinfunction "B3_63") (pintype "passive"))
      (node (ref "J12") (pin "64") (pinfunction "B4_64") (pintype "passive"))
      (node (ref "J12") (pin "65") (pinfunction "B5_65") (pintype "passive"))
      (node (ref "J12") (pin "66") (pinfunction "B6_66") (pintype "passive"))
      (node (ref "J12") (pin "67") (pinfunction "B7_67") (pintype "passive"))
      (node (ref "J12") (pin "68") (pinfunction "B8_68") (pintype "passive"))
      (node (ref "J12") (pin "69") (pinfunction "B9_69") (pintype "passive"))
      (node (ref "J12") (pin "7") (pinfunction "A7_7") (pintype "passive"))
      (node (ref "J12") (pin "70") (pinfunction "B10_70") (pintype "passive"))
      (node (ref "J12") (pin "71") (pinfunction "B11_71") (pintype "passive"))
      (node (ref "J12") (pin "72") (pinfunction "B12_72") (pintype "passive"))
      (node (ref "J12") (pin "8") (pinfunction "A8_8") (pintype "passive"))
      (node (ref "J12") (pin "81") (pinfunction "B21_81") (pintype "passive"))
      (node (ref "J12") (pin "9") (pinfunction "A9_9") (pintype "passive"))
      (node (ref "J12") (pin "90") (pinfunction "B30_90") (pintype "passive"))
      (node (ref "J12") (pin "99") (pinfunction "B39_99") (pintype "passive"))
      (node (ref "J13") (pin "10") (pinfunction "A10_10") (pintype "passive"))
      (node (ref "J13") (pin "108") (pinfunction "B48_108") (pintype "passive"))
      (node (ref "J13") (pin "11") (pinfunction "A11_11") (pintype "passive"))
      (node (ref "J13") (pin "12") (pinfunction "A12_12") (pintype "passive"))
      (node (ref "J13") (pin "2") (pinfunction "A2_2") (pintype "passive"))
      (node (ref "J13") (pin "21") (pinfunction "A21_21") (pintype "passive"))
      (node (ref "J13") (pin "3") (pinfunction "A3_3") (pintype "passive"))
      (node (ref "J13") (pin "30") (pinfunction "A30_30") (pintype "passive"))
      (node (ref "J13") (pin "39") (pinfunction "A39_39") (pintype "passive"))
      (node (ref "J13") (pin "4") (pinfunction "A4_4") (pintype "passive"))
      (node (ref "J13") (pin "48") (pinfunction "A48_48") (pintype "passive"))
      (node (ref "J13") (pin "5") (pinfunction "A5_5") (pintype "passive"))
      (node (ref "J13") (pin "6") (pinfunction "A6_6") (pintype "passive"))
      (node (ref "J13") (pin "62") (pinfunction "B2_62") (pintype "passive"))
      (node (ref "J13") (pin "63") (pinfunction "B3_63") (pintype "passive"))
      (node (ref "J13") (pin "64") (pinfunction "B4_64") (pintype "passive"))
      (node (ref "J13") (pin "65") (pinfunction "B5_65") (pintype "passive"))
      (node (ref "J13") (pin "66") (pinfunction "B6_66") (pintype "passive"))
      (node (ref "J13") (pin "67") (pinfunction "B7_67") (pintype "passive"))
      (node (ref "J13") (pin "68") (pinfunction "B8_68") (pintype "passive"))
      (node (ref "J13") (pin "69") (pinfunction "B9_69") (pintype "passive"))
      (node (ref "J13") (pin "7") (pinfunction "A7_7") (pintype "passive"))
      (node (ref "J13") (pin "70") (pinfunction "B10_70") (pintype "passive"))
      (node (ref "J13") (pin "71") (pinfunction "B11_71") (pintype "passive"))
      (node (ref "J13") (pin "72") (pinfunction "B12_72") (pintype "passive"))
      (node (ref "J13") (pin "8") (pinfunction "A8_8") (pintype "passive"))
      (node (ref "J13") (pin "81") (pinfunction "B21_81") (pintype "passive"))
      (node (ref "J13") (pin "9") (pinfunction "A9_9") (pintype "passive"))
      (node (ref "J13") (pin "90") (pinfunction "B30_90") (pintype "passive"))
      (node (ref "J13") (pin "99") (pinfunction "B39_99") (pintype "passive"))
      (node (ref "J14") (pin "10") (pinfunction "A10_10") (pintype "passive"))
      (node (ref "J14") (pin "108") (pinfunction "B48_108") (pintype "passive"))
      (node (ref "J14") (pin "11") (pinfunction "A11_11") (pintype "passive"))
      (node (ref "J14") (pin "12") (pinfunction "A12_12") (pintype "passive"))
      (node (ref "J14") (pin "2") (pinfunction "A2_2") (pintype "passive"))
      (node (ref "J14") (pin "21") (pinfunction "A21_21") (pintype "passive"))
      (node (ref "J14") (pin "3") (pinfunction "A3_3") (pintype "passive"))
      (node (ref "J14") (pin "30") (pinfunction "A30_30") (pintype "passive"))
      (node (ref "J14") (pin "39") (pinfunction "A39_39") (pintype "passive"))
      (node (ref "J14") (pin "4") (pinfunction "A4_4") (pintype "passive"))
      (node (ref "J14") (pin "48") (pinfunction "A48_48") (pintype "passive"))
      (node (ref "J14") (pin "5") (pinfunction "A5_5") (pintype "passive"))
      (node (ref "J14") (pin "6") (pinfunction "A6_6") (pintype "passive"))
      (node (ref "J14") (pin "62") (pinfunction "B2_62") (pintype "passive"))
      (node (ref "J14") (pin "63") (pinfunction "B3_63") (pintype "passive"))
      (node (ref "J14") (pin "64") (pinfunction "B4_64") (pintype "passive"))
      (node (ref "J14") (pin "65") (pinfunction "B5_65") (pintype "passive"))
      (node (ref "J14") (pin "66") (pinfunction "B6_66") (pintype "passive"))
      (node (ref "J14") (pin "67") (pinfunction "B7_67") (pintype "passive"))
      (node (ref "J14") (pin "68") (pinfunction "B8_68") (pintype "passive"))
      (node (ref "J14") (pin "69") (pinfunction "B9_69") (pintype "passive"))
      (node (ref "J14") (pin "7") (pinfunction "A7_7") (pintype "passive"))
      (node (ref "J14") (pin "70") (pinfunction "B10_70") (pintype "passive"))
      (node (ref "J14") (pin "71") (pinfunction "B11_71") (pintype "passive"))
      (node (ref "J14") (pin "72") (pinfunction "B12_72") (pintype "passive"))
      (node (ref "J14") (pin "8") (pinfunction "A8_8") (pintype "passive"))
      (node (ref "J14") (pin "81") (pinfunction "B21_81") (pintype "passive"))
      (node (ref "J14") (pin "9") (pinfunction "A9_9") (pintype "passive"))
      (node (ref "J14") (pin "90") (pinfunction "B30_90") (pintype "passive"))
      (node (ref "J14") (pin "99") (pinfunction "B39_99") (pintype "passive"))
      (node (ref "J15") (pin "10") (pinfunction "A10_10") (pintype "passive"))
      (node (ref "J15") (pin "108") (pinfunction "B48_108") (pintype "passive"))
      (node (ref "J15") (pin "11") (pinfunction "A11_11") (pintype "passive"))
      (node (ref "J15") (pin "12") (pinfunction "A12_12") (pintype "passive"))
      (node (ref "J15") (pin "2") (pinfunction "A2_2") (pintype "passive"))
      (node (ref "J15") (pin "21") (pinfunction "A21_21") (pintype "passive"))
      (node (ref "J15") (pin "3") (pinfunction "A3_3") (pintype "passive"))
      (node (ref "J15") (pin "30") (pinfunction "A30_30") (pintype "passive"))
      (node (ref "J15") (pin "39") (pinfunction "A39_39") (pintype "passive"))
      (node (ref "J15") (pin "4") (pinfunction "A4_4") (pintype "passive"))
      (node (ref "J15") (pin "48") (pinfunction "A48_48") (pintype "passive"))
      (node (ref "J15") (pin "5") (pinfunction "A5_5") (pintype "passive"))
      (node (ref "J15") (pin "6") (pinfunction "A6_6") (pintype "passive"))
      (node (ref "J15") (pin "62") (pinfunction "B2_62") (pintype "passive"))
      (node (ref "J15") (pin "63") (pinfunction "B3_63") (pintype "passive"))
      (node (ref "J15") (pin "64") (pinfunction "B4_64") (pintype "passive"))
      (node (ref "J15") (pin "65") (pinfunction "B5_65") (pintype "passive"))
      (node (ref "J15") (pin "66") (pinfunction "B6_66") (pintype "passive"))
      (node (ref "J15") (pin "67") (pinfunction "B7_67") (pintype "passive"))
      (node (ref "J15") (pin "68") (pinfunction "B8_68") (pintype "passive"))
      (node (ref "J15") (pin "69") (pinfunction "B9_69") (pintype "passive"))
      (node (ref "J15") (pin "7") (pinfunction "A7_7") (pintype "passive"))
      (node (ref "J15") (pin "70") (pinfunction "B10_70") (pintype "passive"))
      (node (ref "J15") (pin "71") (pinfunction "B11_71") (pintype "passive"))
      (node (ref "J15") (pin "72") (pinfunction "B12_72") (pintype "passive"))
      (node (ref "J15") (pin "8") (pinfunction "A8_8") (pintype "passive"))
      (node (ref "J15") (pin "81") (pinfunction "B21_81") (pintype "passive"))
      (node (ref "J15") (pin "9") (pinfunction "A9_9") (pintype "passive"))
      (node (ref "J15") (pin "90") (pinfunction "B30_90") (pintype "passive"))
      (node (ref "J15") (pin "99") (pinfunction "B39_99") (pintype "passive"))
      (node (ref "J16") (pin "10") (pinfunction "A10_10") (pintype "passive"))
      (node (ref "J16") (pin "108") (pinfunction "B48_108") (pintype "passive"))
      (node (ref "J16") (pin "11") (pinfunction "A11_11") (pintype "passive"))
      (node (ref "J16") (pin "12") (pinfunction "A12_12") (pintype "passive"))
      (node (ref "J16") (pin "2") (pinfunction "A2_2") (pintype "passive"))
      (node (ref "J16") (pin "21") (pinfunction "A21_21") (pintype "passive"))
      (node (ref "J16") (pin "3") (pinfunction "A3_3") (pintype "passive"))
      (node (ref "J16") (pin "30") (pinfunction "A30_30") (pintype "passive"))
      (node (ref "J16") (pin "39") (pinfunction "A39_39") (pintype "passive"))
      (node (ref "J16") (pin "4") (pinfunction "A4_4") (pintype "passive"))
      (node (ref "J16") (pin "48") (pinfunction "A48_48") (pintype "passive"))
      (node (ref "J16") (pin "5") (pinfunction "A5_5") (pintype "passive"))
      (node (ref "J16") (pin "6") (pinfunction "A6_6") (pintype "passive"))
      (node (ref "J16") (pin "62") (pinfunction "B2_62") (pintype "passive"))
      (node (ref "J16") (pin "63") (pinfunction "B3_63") (pintype "passive"))
      (node (ref "J16") (pin "64") (pinfunction "B4_64") (pintype "passive"))
      (node (ref "J16") (pin "65") (pinfunction "B5_65") (pintype "passive"))
      (node (ref "J16") (pin "66") (pinfunction "B6_66") (pintype "passive"))
      (node (ref "J16") (pin "67") (pinfunction "B7_67") (pintype "passive"))
      (node (ref "J16") (pin "68") (pinfunction "B8_68") (pintype "passive"))
      (node (ref "J16") (pin "69") (pinfunction "B9_69") (pintype "passive"))
      (node (ref "J16") (pin "7") (pinfunction "A7_7") (pintype "passive"))
      (node (ref "J16") (pin "70") (pinfunction "B10_70") (pintype "passive"))
      (node (ref "J16") (pin "71") (pinfunction "B11_71") (pintype "passive"))
      (node (ref "J16") (pin "72") (pinfunction "B12_72") (pintype "passive"))
      (node (ref "J16") (pin "8") (pinfunction "A8_8") (pintype "passive"))
      (node (ref "J16") (pin "81") (pinfunction "B21_81") (pintype "passive"))
      (node (ref "J16") (pin "9") (pinfunction "A9_9") (pintype "passive"))
      (node (ref "J16") (pin "90") (pinfunction "B30_90") (pintype "passive"))
      (node (ref "J16") (pin "99") (pinfunction "B39_99") (pintype "passive"))
      (node (ref "J2") (pin "10") (pinfunction "A10_10") (pintype "passive"))
      (node (ref "J2") (pin "108") (pinfunction "B48_108") (pintype "passive"))
      (node (ref "J2") (pin "11") (pinfunction "A11_11") (pintype "passive"))
      (node (ref "J2") (pin "12") (pinfunction "A12_12") (pintype "passive"))
      (node (ref "J2") (pin "2") (pinfunction "A2_2") (pintype "passive"))
      (node (ref "J2") (pin "21") (pinfunction "A21_21") (pintype "passive"))
      (node (ref "J2") (pin "3") (pinfunction "A3_3") (pintype "passive"))
      (node (ref "J2") (pin "30") (pinfunction "A30_30") (pintype "passive"))
      (node (ref "J2") (pin "39") (pinfunction "A39_39") (pintype "passive"))
      (node (ref "J2") (pin "4") (pinfunction "A4_4") (pintype "passive"))
      (node (ref "J2") (pin "48") (pinfunction "A48_48") (pintype "passive"))
      (node (ref "J2") (pin "5") (pinfunction "A5_5") (pintype "passive"))
      (node (ref "J2") (pin "6") (pinfunction "A6_6") (pintype "passive"))
      (node (ref "J2") (pin "62") (pinfunction "B2_62") (pintype "passive"))
      (node (ref "J2") (pin "63") (pinfunction "B3_63") (pintype "passive"))
      (node (ref "J2") (pin "64") (pinfunction "B4_64") (pintype "passive"))
      (node (ref "J2") (pin "65") (pinfunction "B5_65") (pintype "passive"))
      (node (ref "J2") (pin "66") (pinfunction "B6_66") (pintype "passive"))
      (node (ref "J2") (pin "67") (pinfunction "B7_67") (pintype "passive"))
      (node (ref "J2") (pin "68") (pinfunction "B8_68") (pintype "passive"))
      (node (ref "J2") (pin "69") (pinfunction "B9_69") (pintype "passive"))
      (node (ref "J2") (pin "7") (pinfunction "A7_7") (pintype "passive"))
      (node (ref "J2") (pin "70") (pinfunction "B10_70") (pintype "passive"))
      (node (ref "J2") (pin "71") (pinfunction "B11_71") (pintype "passive"))
      (node (ref "J2") (pin "72") (pinfunction "B12_72") (pintype "passive"))
      (node (ref "J2") (pin "8") (pinfunction "A8_8") (pintype "passive"))
      (node (ref "J2") (pin "81") (pinfunction "B21_81") (pintype "passive"))
      (node (ref "J2") (pin "9") (pinfunction "A9_9") (pintype "passive"))
      (node (ref "J2") (pin "90") (pinfunction "B30_90") (pintype "passive"))
      (node (ref "J2") (pin "99") (pinfunction "B39_99") (pintype "passive"))
      (node (ref "J3") (pin "10") (pinfunction "A10_10") (pintype "passive"))
      (node (ref "J3") (pin "108") (pinfunction "B48_108") (pintype "passive"))
      (node (ref "J3") (pin "11") (pinfunction "A11_11") (pintype "passive"))
      (node (ref "J3") (pin "12") (pinfunction "A12_12") (pintype "passive"))
      (node (ref "J3") (pin "2") (pinfunction "A2_2") (pintype "passive"))
      (node (ref "J3") (pin "21") (pinfunction "A21_21") (pintype "passive"))
      (node (ref "J3") (pin "3") (pinfunction "A3_3") (pintype "passive"))
      (node (ref "J3") (pin "30") (pinfunction "A30_30") (pintype "passive"))
      (node (ref "J3") (pin "39") (pinfunction "A39_39") (pintype "passive"))
      (node (ref "J3") (pin "4") (pinfunction "A4_4") (pintype "passive"))
      (node (ref "J3") (pin "48") (pinfunction "A48_48") (pintype "passive"))
      (node (ref "J3") (pin "5") (pinfunction "A5_5") (pintype "passive"))
      (node (ref "J3") (pin "6") (pinfunction "A6_6") (pintype "passive"))
      (node (ref "J3") (pin "62") (pinfunction "B2_62") (pintype "passive"))
      (node (ref "J3") (pin "63") (pinfunction "B3_63") (pintype "passive"))
      (node (ref "J3") (pin "64") (pinfunction "B4_64") (pintype "passive"))
      (node (ref "J3") (pin "65") (pinfunction "B5_65") (pintype "passive"))
      (node (ref "J3") (pin "66") (pinfunction "B6_66") (pintype "passive"))
      (node (ref "J3") (pin "67") (pinfunction "B7_67") (pintype "passive"))
      (node (ref "J3") (pin "68") (pinfunction "B8_68") (pintype "passive"))
      (node (ref "J3") (pin "69") (pinfunction "B9_69") (pintype "passive"))
      (node (ref "J3") (pin "7") (pinfunction "A7_7") (pintype "passive"))
      (node (ref "J3") (pin "70") (pinfunction "B10_70") (pintype "passive"))
      (node (ref "J3") (pin "71") (pinfunction "B11_71") (pintype "passive"))
      (node (ref "J3") (pin "72") (pinfunction "B12_72") (pintype "passive"))
      (node (ref "J3") (pin "8") (pinfunction "A8_8") (pintype "passive"))
      (node (ref "J3") (pin "81") (pinfunction "B21_81") (pintype "passive"))
      (node (ref "J3") (pin "9") (pinfunction "A9_9") (pintype "passive"))
      (node (ref "J3") (pin "90") (pinfunction "B30_90") (pintype "passive"))
      (node (ref "J3") (pin "99") (pinfunction "B39_99") (pintype "passive"))
      (node (ref "J4") (pin "10") (pinfunction "A10_10") (pintype "passive"))
      (node (ref "J4") (pin "108") (pinfunction "B48_108") (pintype "passive"))
      (node (ref "J4") (pin "11") (pinfunction "A11_11") (pintype "passive"))
      (node (ref "J4") (pin "12") (pinfunction "A12_12") (pintype "passive"))
      (node (ref "J4") (pin "2") (pinfunction "A2_2") (pintype "passive"))
      (node (ref "J4") (pin "21") (pinfunction "A21_21") (pintype "passive"))
      (node (ref "J4") (pin "3") (pinfunction "A3_3") (pintype "passive"))
      (node (ref "J4") (pin "30") (pinfunction "A30_30") (pintype "passive"))
      (node (ref "J4") (pin "39") (pinfunction "A39_39") (pintype "passive"))
      (node (ref "J4") (pin "4") (pinfunction "A4_4") (pintype "passive"))
      (node (ref "J4") (pin "48") (pinfunction "A48_48") (pintype "passive"))
      (node (ref "J4") (pin "5") (pinfunction "A5_5") (pintype "passive"))
      (node (ref "J4") (pin "6") (pinfunction "A6_6") (pintype "passive"))
      (node (ref "J4") (pin "62") (pinfunction "B2_62") (pintype "passive"))
      (node (ref "J4") (pin "63") (pinfunction "B3_63") (pintype "passive"))
      (node (ref "J4") (pin "64") (pinfunction "B4_64") (pintype "passive"))
      (node (ref "J4") (pin "65") (pinfunction "B5_65") (pintype "passive"))
      (node (ref "J4") (pin "66") (pinfunction "B6_66") (pintype "passive"))
      (node (ref "J4") (pin "67") (pinfunction "B7_67") (pintype "passive"))
      (node (ref "J4") (pin "68") (pinfunction "B8_68") (pintype "passive"))
      (node (ref "J4") (pin "69") (pinfunction "B9_69") (pintype "passive"))
      (node (ref "J4") (pin "7") (pinfunction "A7_7") (pintype "passive"))
      (node (ref "J4") (pin "70") (pinfunction "B10_70") (pintype "passive"))
      (node (ref "J4") (pin "71") (pinfunction "B11_71") (pintype "passive"))
      (node (ref "J4") (pin "72") (pinfunction "B12_72") (pintype "passive"))
      (node (ref "J4") (pin "8") (pinfunction "A8_8") (pintype "passive"))
      (node (ref "J4") (pin "81") (pinfunction "B21_81") (pintype "passive"))
      (node (ref "J4") (pin "9") (pinfunction "A9_9") (pintype "passive"))
      (node (ref "J4") (pin "90") (pinfunction "B30_90") (pintype "passive"))
      (node (ref "J4") (pin "99") (pinfunction "B39_99") (pintype "passive"))
      (node (ref "J5") (pin "10") (pinfunction "A10_10") (pintype "passive"))
      (node (ref "J5") (pin "108") (pinfunction "B48_108") (pintype "passive"))
      (node (ref "J5") (pin "11") (pinfunction "A11_11") (pintype "passive"))
      (node (ref "J5") (pin "12") (pinfunction "A12_12") (pintype "passive"))
      (node (ref "J5") (pin "2") (pinfunction "A2_2") (pintype "passive"))
      (node (ref "J5") (pin "21") (pinfunction "A21_21") (pintype "passive"))
      (node (ref "J5") (pin "3") (pinfunction "A3_3") (pintype "passive"))
      (node (ref "J5") (pin "30") (pinfunction "A30_30") (pintype "passive"))
      (node (ref "J5") (pin "39") (pinfunction "A39_39") (pintype "passive"))
      (node (ref "J5") (pin "4") (pinfunction "A4_4") (pintype "passive"))
      (node (ref "J5") (pin "48") (pinfunction "A48_48") (pintype "passive"))
      (node (ref "J5") (pin "5") (pinfunction "A5_5") (pintype "passive"))
      (node (ref "J5") (pin "6") (pinfunction "A6_6") (pintype "passive"))
      (node (ref "J5") (pin "62") (pinfunction "B2_62") (pintype "passive"))
      (node (ref "J5") (pin "63") (pinfunction "B3_63") (pintype "passive"))
      (node (ref "J5") (pin "64") (pinfunction "B4_64") (pintype "passive"))
      (node (ref "J5") (pin "65") (pinfunction "B5_65") (pintype "passive"))
      (node (ref "J5") (pin "66") (pinfunction "B6_66") (pintype "passive"))
      (node (ref "J5") (pin "67") (pinfunction "B7_67") (pintype "passive"))
      (node (ref "J5") (pin "68") (pinfunction "B8_68") (pintype "passive"))
      (node (ref "J5") (pin "69") (pinfunction "B9_69") (pintype "passive"))
      (node (ref "J5") (pin "7") (pinfunction "A7_7") (pintype "passive"))
      (node (ref "J5") (pin "70") (pinfunction "B10_70") (pintype "passive"))
      (node (ref "J5") (pin "71") (pinfunction "B11_71") (pintype "passive"))
      (node (ref "J5") (pin "72") (pinfunction "B12_72") (pintype "passive"))
      (node (ref "J5") (pin "8") (pinfunction "A8_8") (pintype "passive"))
      (node (ref "J5") (pin "81") (pinfunction "B21_81") (pintype "passive"))
      (node (ref "J5") (pin "9") (pinfunction "A9_9") (pintype "passive"))
      (node (ref "J5") (pin "90") (pinfunction "B30_90") (pintype "passive"))
      (node (ref "J5") (pin "99") (pinfunction "B39_99") (pintype "passive"))
      (node (ref "J6") (pin "10") (pinfunction "A10_10") (pintype "passive"))
      (node (ref "J6") (pin "108") (pinfunction "B48_108") (pintype "passive"))
      (node (ref "J6") (pin "11") (pinfunction "A11_11") (pintype "passive"))
      (node (ref "J6") (pin "12") (pinfunction "A12_12") (pintype "passive"))
      (node (ref "J6") (pin "2") (pinfunction "A2_2") (pintype "passive"))
      (node (ref "J6") (pin "21") (pinfunction "A21_21") (pintype "passive"))
      (node (ref "J6") (pin "3") (pinfunction "A3_3") (pintype "passive"))
      (node (ref "J6") (pin "30") (pinfunction "A30_30") (pintype "passive"))
      (node (ref "J6") (pin "39") (pinfunction "A39_39") (pintype "passive"))
      (node (ref "J6") (pin "4") (pinfunction "A4_4") (pintype "passive"))
      (node (ref "J6") (pin "48") (pinfunction "A48_48") (pintype "passive"))
      (node (ref "J6") (pin "5") (pinfunction "A5_5") (pintype "passive"))
      (node (ref "J6") (pin "6") (pinfunction "A6_6") (pintype "passive"))
      (node (ref "J6") (pin "62") (pinfunction "B2_62") (pintype "passive"))
      (node (ref "J6") (pin "63") (pinfunction "B3_63") (pintype "passive"))
      (node (ref "J6") (pin "64") (pinfunction "B4_64") (pintype "passive"))
      (node (ref "J6") (pin "65") (pinfunction "B5_65") (pintype "passive"))
      (node (ref "J6") (pin "66") (pinfunction "B6_66") (pintype "passive"))
      (node (ref "J6") (pin "67") (pinfunction "B7_67") (pintype "passive"))
      (node (ref "J6") (pin "68") (pinfunction "B8_68") (pintype "passive"))
      (node (ref "J6") (pin "69") (pinfunction "B9_69") (pintype "passive"))
      (node (ref "J6") (pin "7") (pinfunction "A7_7") (pintype "passive"))
      (node (ref "J6") (pin "70") (pinfunction "B10_70") (pintype "passive"))
      (node (ref "J6") (pin "71") (pinfunction "B11_71") (pintype "passive"))
      (node (ref "J6") (pin "72") (pinfunction "B12_72") (pintype "passive"))
      (node (ref "J6") (pin "8") (pinfunction "A8_8") (pintype "passive"))
      (node (ref "J6") (pin "81") (pinfunction "B21_81") (pintype "passive"))
      (node (ref "J6") (pin "9") (pinfunction "A9_9") (pintype "passive"))
      (node (ref "J6") (pin "90") (pinfunction "B30_90") (pintype "passive"))
      (node (ref "J6") (pin "99") (pinfunction "B39_99") (pintype "passive"))
      (node (ref "J7") (pin "10") (pinfunction "A10_10") (pintype "passive"))
      (node (ref "J7") (pin "108") (pinfunction "B48_108") (pintype "passive"))
      (node (ref "J7") (pin "11") (pinfunction "A11_11") (pintype "passive"))
      (node (ref "J7") (pin "12") (pinfunction "A12_12") (pintype "passive"))
      (node (ref "J7") (pin "2") (pinfunction "A2_2") (pintype "passive"))
      (node (ref "J7") (pin "21") (pinfunction "A21_21") (pintype "passive"))
      (node (ref "J7") (pin "3") (pinfunction "A3_3") (pintype "passive"))
      (node (ref "J7") (pin "30") (pinfunction "A30_30") (pintype "passive"))
      (node (ref "J7") (pin "39") (pinfunction "A39_39") (pintype "passive"))
      (node (ref "J7") (pin "4") (pinfunction "A4_4") (pintype "passive"))
      (node (ref "J7") (pin "48") (pinfunction "A48_48") (pintype "passive"))
      (node (ref "J7") (pin "5") (pinfunction "A5_5") (pintype "passive"))
      (node (ref "J7") (pin "6") (pinfunction "A6_6") (pintype "passive"))
      (node (ref "J7") (pin "62") (pinfunction "B2_62") (pintype "passive"))
      (node (ref "J7") (pin "63") (pinfunction "B3_63") (pintype "passive"))
      (node (ref "J7") (pin "64") (pinfunction "B4_64") (pintype "passive"))
      (node (ref "J7") (pin "65") (pinfunction "B5_65") (pintype "passive"))
      (node (ref "J7") (pin "66") (pinfunction "B6_66") (pintype "passive"))
      (node (ref "J7") (pin "67") (pinfunction "B7_67") (pintype "passive"))
      (node (ref "J7") (pin "68") (pinfunction "B8_68") (pintype "passive"))
      (node (ref "J7") (pin "69") (pinfunction "B9_69") (pintype "passive"))
      (node (ref "J7") (pin "7") (pinfunction "A7_7") (pintype "passive"))
      (node (ref "J7") (pin "70") (pinfunction "B10_70") (pintype "passive"))
      (node (ref "J7") (pin "71") (pinfunction "B11_71") (pintype "passive"))
      (node (ref "J7") (pin "72") (pinfunction "B12_72") (pintype "passive"))
      (node (ref "J7") (pin "8") (pinfunction "A8_8") (pintype "passive"))
      (node (ref "J7") (pin "81") (pinfunction "B21_81") (pintype "passive"))
      (node (ref "J7") (pin "9") (pinfunction "A9_9") (pintype "passive"))
      (node (ref "J7") (pin "90") (pinfunction "B30_90") (pintype "passive"))
      (node (ref "J7") (pin "99") (pinfunction "B39_99") (pintype "passive"))
      (node (ref "J8") (pin "10") (pinfunction "A10_10") (pintype "passive"))
      (node (ref "J8") (pin "108") (pinfunction "B48_108") (pintype "passive"))
      (node (ref "J8") (pin "11") (pinfunction "A11_11") (pintype "passive"))
      (node (ref "J8") (pin "12") (pinfunction "A12_12") (pintype "passive"))
      (node (ref "J8") (pin "2") (pinfunction "A2_2") (pintype "passive"))
      (node (ref "J8") (pin "21") (pinfunction "A21_21") (pintype "passive"))
      (node (ref "J8") (pin "3") (pinfunction "A3_3") (pintype "passive"))
      (node (ref "J8") (pin "30") (pinfunction "A30_30") (pintype "passive"))
      (node (ref "J8") (pin "39") (pinfunction "A39_39") (pintype "passive"))
      (node (ref "J8") (pin "4") (pinfunction "A4_4") (pintype "passive"))
      (node (ref "J8") (pin "48") (pinfunction "A48_48") (pintype "passive"))
      (node (ref "J8") (pin "5") (pinfunction "A5_5") (pintype "passive"))
      (node (ref "J8") (pin "6") (pinfunction "A6_6") (pintype "passive"))
      (node (ref "J8") (pin "62") (pinfunction "B2_62") (pintype "passive"))
      (node (ref "J8") (pin "63") (pinfunction "B3_63") (pintype "passive"))
      (node (ref "J8") (pin "64") (pinfunction "B4_64") (pintype "passive"))
      (node (ref "J8") (pin "65") (pinfunction "B5_65") (pintype "passive"))
      (node (ref "J8") (pin "66") (pinfunction "B6_66") (pintype "passive"))
      (node (ref "J8") (pin "67") (pinfunction "B7_67") (pintype "passive"))
      (node (ref "J8") (pin "68") (pinfunction "B8_68") (pintype "passive"))
      (node (ref "J8") (pin "69") (pinfunction "B9_69") (pintype "passive"))
      (node (ref "J8") (pin "7") (pinfunction "A7_7") (pintype "passive"))
      (node (ref "J8") (pin "70") (pinfunction "B10_70") (pintype "passive"))
      (node (ref "J8") (pin "71") (pinfunction "B11_71") (pintype "passive"))
      (node (ref "J8") (pin "72") (pinfunction "B12_72") (pintype "passive"))
      (node (ref "J8") (pin "8") (pinfunction "A8_8") (pintype "passive"))
      (node (ref "J8") (pin "81") (pinfunction "B21_81") (pintype "passive"))
      (node (ref "J8") (pin "9") (pinfunction "A9_9") (pintype "passive"))
      (node (ref "J8") (pin "90") (pinfunction "B30_90") (pintype "passive"))
      (node (ref "J8") (pin "99") (pinfunction "B39_99") (pintype "passive"))
      (node (ref "J9") (pin "10") (pinfunction "A10_10") (pintype "passive"))
      (node (ref "J9") (pin "108") (pinfunction "B48_108") (pintype "passive"))
      (node (ref "J9") (pin "11") (pinfunction "A11_11") (pintype "passive"))
      (node (ref "J9") (pin "12") (pinfunction "A12_12") (pintype "passive"))
      (node (ref "J9") (pin "2") (pinfunction "A2_2") (pintype "passive"))
      (node (ref "J9") (pin "21") (pinfunction "A21_21") (pintype "passive"))
      (node (ref "J9") (pin "3") (pinfunction "A3_3") (pintype "passive"))
      (node (ref "J9") (pin "30") (pinfunction "A30_30") (pintype "passive"))
      (node (ref "J9") (pin "39") (pinfunction "A39_39") (pintype "passive"))
      (node (ref "J9") (pin "4") (pinfunction "A4_4") (pintype "passive"))
      (node (ref "J9") (pin "48") (pinfunction "A48_48") (pintype "passive"))
      (node (ref "J9") (pin "5") (pinfunction "A5_5") (pintype "passive"))
      (node (ref "J9") (pin "6") (pinfunction "A6_6") (pintype "passive"))
      (node (ref "J9") (pin "62") (pinfunction "B2_62") (pintype "passive"))
      (node (ref "J9") (pin "63") (pinfunction "B3_63") (pintype "passive"))
      (node (ref "J9") (pin "64") (pinfunction "B4_64") (pintype "passive"))
      (node (ref "J9") (pin "65") (pinfunction "B5_65") (pintype "passive"))
      (node (ref "J9") (pin "66") (pinfunction "B6_66") (pintype "passive"))
      (node (ref "J9") (pin "67") (pinfunction "B7_67") (pintype "passive"))
      (node (ref "J9") (pin "68") (pinfunction "B8_68") (pintype "passive"))
      (node (ref "J9") (pin "69") (pinfunction "B9_69") (pintype "passive"))
      (node (ref "J9") (pin "7") (pinfunction "A7_7") (pintype "passive"))
      (node (ref "J9") (pin "70") (pinfunction "B10_70") (pintype "passive"))
      (node (ref "J9") (pin "71") (pinfunction "B11_71") (pintype "passive"))
      (node (ref "J9") (pin "72") (pinfunction "B12_72") (pintype "passive"))
      (node (ref "J9") (pin "8") (pinfunction "A8_8") (pintype "passive"))
      (node (ref "J9") (pin "81") (pinfunction "B21_81") (pintype "passive"))
      (node (ref "J9") (pin "9") (pinfunction "A9_9") (pintype "passive"))
      (node (ref "J9") (pin "90") (pinfunction "B30_90") (pintype "passive"))
      (node (ref "J9") (pin "99") (pinfunction "B39_99") (pintype "passive"))
      (node (ref "P1") (pin "2") (pinfunction "Y_2") (pintype "passive"))
      (node (ref "P10") (pin "15") (pinfunction "15_15") (pintype "passive"))
      (node (ref "P10") (pin "38") (pinfunction "38_38") (pintype "passive"))
      (node (ref "P10") (pin "40") (pinfunction "40_40") (pintype "passive"))
      (node (ref "P2") (pin "2") (pinfunction "Y_2") (pintype "passive"))
      (node (ref "P3") (pin "2") (pinfunction "Y_2") (pintype "passive"))
      (node (ref "P4") (pin "2") (pinfunction "Y_2") (pintype "passive"))
      (node (ref "P5") (pin "1") (pinfunction "1_1") (pintype "passive"))
      (node (ref "P5") (pin "40") (pinfunction "40_40") (pintype "passive"))
      (node (ref "P6") (pin "1") (pinfunction "1_1") (pintype "passive"))
      (node (ref "P6") (pin "20") (pinfunction "20_20") (pintype "passive"))
      (node (ref "P7") (pin "1") (pinfunction "1_1") (pintype "passive"))
      (node (ref "P7") (pin "13") (pinfunction "13_13") (pintype "passive"))
      (node (ref "P7") (pin "14") (pinfunction "14_14") (pintype "passive"))
      (node (ref "P7") (pin "36") (pinfunction "36_36") (pintype "passive"))
      (node (ref "P8") (pin "14") (pinfunction "14_14") (pintype "passive"))
      (node (ref "P8") (pin "2") (pinfunction "2_2") (pintype "passive"))
      (node (ref "P8") (pin "35") (pinfunction "35_35") (pintype "passive"))
      (node (ref "P9") (pin "16") (pinfunction "16_16") (pintype "passive"))
      (node (ref "P9") (pin "38") (pinfunction "38_38") (pintype "passive"))
      (node (ref "P9") (pin "40") (pinfunction "40_40") (pintype "passive"))
      (node (ref "R41") (pin "1") (pinfunction "1_1") (pintype "passive"))
      (node (ref "R42") (pin "1") (pinfunction "1_1") (pintype "passive"))
      (node (ref "R43") (pin "1") (pinfunction "1_1") (pintype "passive"))
      (node (ref "R44") (pin "1") (pinfunction "1_1") (pintype "passive"))
      (node (ref "R45") (pin "1") (pinfunction "1_1") (pintype "passive"))
      (node (ref "R46") (pin "1") (pinfunction "1_1") (pintype "passive"))
      (node (ref "R47") (pin "1") (pinfunction "1_1") (pintype "passive"))
      (node (ref "R48") (pin "1") (pinfunction "1_1") (pintype "passive"))
      (node (ref "U1") (pin "8") (pinfunction "GND_8") (pintype "passive"))
      (node (ref "U10") (pin "12") (pinfunction "EN#_12") (pintype "passive"))
      (node (ref "U10") (pin "8") (pinfunction "GND_8") (pintype "passive"))
      (node (ref "U11") (pin "1A2") (pinfunction "GND_1A2") (pintype "passive"))
      (node (ref "U11") (pin "1B2") (pinfunction "GND_1B2") (pintype "passive"))
      (node (ref "U11") (pin "1B39") (pinfunction "GND_1B39") (pintype "passive"))
      (node (ref "U11") (pin "1C2") (pinfunction "GND_1C2") (pintype "passive"))
      (node (ref "U11") (pin "1C39") (pinfunction "GND_1C39") (pintype "passive"))
      (node (ref "U11") (pin "2A2") (pinfunction "GND_2A2") (pintype "passive"))
      (node (ref "U11") (pin "2A39") (pinfunction "GND_2A39") (pintype "passive"))
      (node (ref "U11") (pin "2B2") (pinfunction "GND_2B2") (pintype "passive"))
      (node (ref "U11") (pin "2B39") (pinfunction "GND_2B39") (pintype "passive"))
      (node (ref "U11") (pin "2C2") (pinfunction "GND_2C2") (pintype "passive"))
      (node (ref "U11") (pin "2C39") (pinfunction "GND_2C39") (pintype "passive"))
      (node (ref "U12") (pin "2") (pinfunction "GND_2") (pintype "passive"))
      (node (ref "U13") (pin "2") (pinfunction "GND_2") (pintype "passive"))
      (node (ref "U14") (pin "2") (pinfunction "GND_2") (pintype "passive"))
      (node (ref "U15") (pin "2") (pinfunction "GND_2") (pintype "passive"))
      (node (ref "U2") (pin "8") (pinfunction "GND_8") (pintype "passive"))
      (node (ref "U3") (pin "12") (pinfunction "EN#_12") (pintype "passive"))
      (node (ref "U3") (pin "8") (pinfunction "GND_8") (pintype "passive"))
      (node (ref "U4") (pin "12") (pinfunction "EN#_12") (pintype "passive"))
      (node (ref "U4") (pin "8") (pinfunction "GND_8") (pintype "passive"))
      (node (ref "U5") (pin "12") (pinfunction "EN#_12") (pintype "passive"))
      (node (ref "U5") (pin "8") (pinfunction "GND_8") (pintype "passive"))
      (node (ref "U6") (pin "12") (pinfunction "EN#_12") (pintype "passive"))
      (node (ref "U6") (pin "8") (pinfunction "GND_8") (pintype "passive"))
      (node (ref "U7") (pin "12") (pinfunction "EN#_12") (pintype "passive"))
      (node (ref "U7") (pin "8") (pinfunction "GND_8") (pintype "passive"))
      (node (ref "U8") (pin "12") (pinfunction "EN#_12") (pintype "passive"))
      (node (ref "U8") (pin "8") (pinfunction "GND_8") (pintype "passive"))
      (node (ref "U9") (pin "12") (pinfunction "EN#_12") (pintype "passive"))
      (node (ref "U9") (pin "8") (pinfunction "GND_8") (pintype "passive"))
    )
    (net (code "193") (name "Net-(D1-K)") (class "Default")
      (node (ref "D1") (pin "2") (pinfunction "K_2") (pintype "passive"))
      (node (ref "R41") (pin "2") (pinfunction "2_2") (pintype "passive"))
    )
    (net (code "194") (name "Net-(D2-K)") (class "Default")
      (node (ref "D2") (pin "2") (pinfunction "K_2") (pintype "passive"))
      (node (ref "R42") (pin "2") (pinfunction "2_2") (pintype "passive"))
    )
    (net (code "195") (name "Net-(D3-K)") (class "Default")
      (node (ref "D3") (pin "2") (pinfunction "K_2") (pintype "passive"))
      (node (ref "R43") (pin "2") (pinfunction "2_2") (pintype "passive"))
    )
    (net (code "196") (name "Net-(D4-K)") (class "Default")
      (node (ref "D4") (pin "2") (pinfunction "K_2") (pintype "passive"))
      (node (ref "R44") (pin "2") (pinfunction "2_2") (pintype "passive"))
    )
    (net (code "197") (name "Net-(D5-K)") (class "Default")
      (node (ref "D5") (pin "2") (pinfunction "K_2") (pintype "passive"))
      (node (ref "R45") (pin "2") (pinfunction "2_2") (pintype "passive"))
    )
    (net (code "198") (name "Net-(D6-K)") (class "Default")
      (node (ref "D6") (pin "2") (pinfunction "K_2") (pintype "passive"))
      (node (ref "R46") (pin "2") (pinfunction "2_2") (pintype "passive"))
    )
    (net (code "199") (name "Net-(D7-K)") (class "Default")
      (node (ref "D7") (pin "2") (pinfunction "K_2") (pintype "passive"))
      (node (ref "R47") (pin "2") (pinfunction "2_2") (pintype "passive"))
    )
    (net (code "200") (name "Net-(D8-K)") (class "Default")
      (node (ref "D8") (pin "2") (pinfunction "K_2") (pintype "passive"))
      (node (ref "R48") (pin "2") (pinfunction "2_2") (pintype "passive"))
    )
    (net (code "201") (name "Net-(P1-X)") (class "Default")
      (node (ref "P1") (pin "1") (pinfunction "X_1") (pintype "passive"))
      (node (ref "U12") (pin "3") (pinfunction "A_3") (pintype "passive"))
    )
    (net (code "202") (name "Net-(P2-X)") (class "Default")
      (node (ref "P2") (pin "1") (pinfunction "X_1") (pintype "passive"))
      (node (ref "U13") (pin "3") (pinfunction "A_3") (pintype "passive"))
    )
    (net (code "203") (name "Net-(P3-X)") (class "Default")
      (node (ref "P3") (pin "1") (pinfunction "X_1") (pintype "passive"))
      (node (ref "U14") (pin "3") (pinfunction "A_3") (pintype "passive"))
    )
    (net (code "204") (name "Net-(P4-X)") (class "Default")
      (node (ref "P4") (pin "1") (pinfunction "X_1") (pintype "passive"))
      (node (ref "U15") (pin "3") (pinfunction "A_3") (pintype "passive"))
    )
    (net (code "205") (name "unconnected-(P5-Pad38)") (class "Default")
      (node (ref "P5") (pin "38") (pinfunction "38_38") (pintype "passive"))
    )
    (net (code "206") (name "unconnected-(P5-Pad39)") (class "Default")
      (node (ref "P5") (pin "39") (pinfunction "39_39") (pintype "passive"))
    )
    (net (code "207") (name "unconnected-(P7-Pad3)") (class "Default")
      (node (ref "P7") (pin "3") (pinfunction "3_3") (pintype "passive"))
    )
    (net (code "208") (name "unconnected-(P7-Pad5)") (class "Default")
      (node (ref "P7") (pin "5") (pinfunction "5_5") (pintype "passive"))
    )
    (net (code "209") (name "unconnected-(P7-Pad7)") (class "Default")
      (node (ref "P7") (pin "7") (pinfunction "7_7") (pintype "passive"))
    )
    (net (code "210") (name "unconnected-(P7-Pad8)") (class "Default")
      (node (ref "P7") (pin "8") (pinfunction "8_8") (pintype "passive"))
    )
    (net (code "211") (name "unconnected-(P7-Pad9)") (class "Default")
      (node (ref "P7") (pin "9") (pinfunction "9_9") (pintype "passive"))
    )
    (net (code "212") (name "unconnected-(P7-Pad10)") (class "Default")
      (node (ref "P7") (pin "10") (pinfunction "10_10") (pintype "passive"))
    )
    (net (code "213") (name "unconnected-(P7-Pad11)") (class "Default")
      (node (ref "P7") (pin "11") (pinfunction "11_11") (pintype "passive"))
    )
    (net (code "214") (name "unconnected-(P7-Pad12)") (class "Default")
      (node (ref "P7") (pin "12") (pinfunction "12_12") (pintype "passive"))
    )
    (net (code "215") (name "unconnected-(P7-Pad21)") (class "Default")
      (node (ref "P7") (pin "21") (pinfunction "21_21") (pintype "passive"))
    )
    (net (code "216") (name "unconnected-(P7-Pad22)") (class "Default")
      (node (ref "P7") (pin "22") (pinfunction "22_22") (pintype "passive"))
    )
    (net (code "217") (name "unconnected-(P7-Pad23)") (class "Default")
      (node (ref "P7") (pin "23") (pinfunction "23_23") (pintype "passive"))
    )
    (net (code "218") (name "unconnected-(P7-Pad24)") (class "Default")
      (node (ref "P7") (pin "24") (pinfunction "24_24") (pintype "passive"))
    )
    (net (code "219") (name "unconnected-(P7-Pad35)") (class "Default")
      (node (ref "P7") (pin "35") (pinfunction "35_35") (pintype "passive"))
    )
    (net (code "220") (name "unconnected-(P7-Pad37)") (class "Default")
      (node (ref "P7") (pin "37") (pinfunction "37_37") (pintype "passive"))
    )
    (net (code "221") (name "unconnected-(P7-Pad38)") (class "Default")
      (node (ref "P7") (pin "38") (pinfunction "38_38") (pintype "passive"))
    )
    (net (code "222") (name "unconnected-(P7-Pad39)") (class "Default")
      (node (ref "P7") (pin "39") (pinfunction "39_39") (pintype "passive"))
    )
    (net (code "223") (name "unconnected-(P7-Pad40)") (class "Default")
      (node (ref "P7") (pin "40") (pinfunction "40_40") (pintype "passive"))
    )
    (net (code "224") (name "unconnected-(P8-Pad1)") (class "Default")
      (node (ref "P8") (pin "1") (pinfunction "1_1") (pintype "passive"))
    )
    (net (code "225") (name "unconnected-(P8-Pad3)") (class "Default")
      (node (ref "P8") (pin "3") (pinfunction "3_3") (pintype "passive"))
    )
    (net (code "226") (name "unconnected-(P8-Pad4)") (class "Default")
      (node (ref "P8") (pin "4") (pinfunction "4_4") (pintype "passive"))
    )
    (net (code "227") (name "unconnected-(P8-Pad5)") (class "Default")
      (node (ref "P8") (pin "5") (pinfunction "5_5") (pintype "passive"))
    )
    (net (code "228") (name "unconnected-(P8-Pad6)") (class "Default")
      (node (ref "P8") (pin "6") (pinfunction "6_6") (pintype "passive"))
    )
    (net (code "229") (name "unconnected-(P8-Pad7)") (class "Default")
      (node (ref "P8") (pin "7") (pinfunction "7_7") (pintype "passive"))
    )
    (net (code "230") (name "unconnected-(P8-Pad8)") (class "Default")
      (node (ref "P8") (pin "8") (pinfunction "8_8") (pintype "passive"))
    )
    (net (code "231") (name "unconnected-(P8-Pad9)") (class "Default")
      (node (ref "P8") (pin "9") (pinfunction "9_9") (pintype "passive"))
    )
    (net (code "232") (name "unconnected-(P8-Pad10)") (class "Default")
      (node (ref "P8") (pin "10") (pinfunction "10_10") (pintype "passive"))
    )
    (net (code "233") (name "unconnected-(P8-Pad11)") (class "Default")
      (node (ref "P8") (pin "11") (pinfunction "11_11") (pintype "passive"))
    )
    (net (code "234") (name "unconnected-(P8-Pad12)") (class "Default")
      (node (ref "P8") (pin "12") (pinfunction "12_12") (pintype "passive"))
    )
    (net (code "235") (name "unconnected-(P8-Pad13)") (class "Default")
      (node (ref "P8") (pin "13") (pinfunction "13_13") (pintype "passive"))
    )
    (net (code "236") (name "unconnected-(P8-Pad15)") (class "Default")
      (node (ref "P8") (pin "15") (pinfunction "15_15") (pintype "passive"))
    )
    (net (code "237") (name "unconnected-(P8-Pad16)") (class "Default")
      (node (ref "P8") (pin "16") (pinfunction "16_16") (pintype "passive"))
    )
    (net (code "238") (name "unconnected-(P8-Pad17)") (class "Default")
      (node (ref "P8") (pin "17") (pinfunction "17_17") (pintype "passive"))
    )
    (net (code "239") (name "unconnected-(P8-Pad18)") (class "Default")
      (node (ref "P8") (pin "18") (pinfunction "18_18") (pintype "passive"))
    )
    (net (code "240") (name "unconnected-(P8-Pad36)") (class "Default")
      (node (ref "P8") (pin "36") (pinfunction "36_36") (pintype "passive"))
    )
    (net (code "241") (name "unconnected-(P8-Pad39)") (class "Default")
      (node (ref "P8") (pin "39") (pinfunction "39_39") (pintype "passive"))
    )
    (net (code "242") (name "unconnected-(P8-Pad40)") (class "Default")
      (node (ref "P8") (pin "40") (pinfunction "40_40") (pintype "passive"))
    )
    (net (code "243") (name "unconnected-(P9-Pad15)") (class "Default")
      (node (ref "P9") (pin "15") (pinfunction "15_15") (pintype "passive"))
    )
    (net (code "244") (name "unconnected-(P9-Pad27)") (class "Default")
      (node (ref "P9") (pin "27") (pinfunction "27_27") (pintype "passive"))
    )
    (net (code "245") (name "unconnected-(P9-Pad28)") (class "Default")
      (node (ref "P9") (pin "28") (pinfunction "28_28") (pintype "passive"))
    )
    (net (code "246") (name "unconnected-(P9-Pad29)") (class "Default")
      (node (ref "P9") (pin "29") (pinfunction "29_29") (pintype "passive"))
    )
    (net (code "247") (name "unconnected-(P9-Pad30)") (class "Default")
      (node (ref "P9") (pin "30") (pinfunction "30_30") (pintype "passive"))
    )
    (net (code "248") (name "unconnected-(P9-Pad31)") (class "Default")
      (node (ref "P9") (pin "31") (pinfunction "31_31") (pintype "passive"))
    )
    (net (code "249") (name "unconnected-(P9-Pad33)") (class "Default")
      (node (ref "P9") (pin "33") (pinfunction "33_33") (pintype "passive"))
    )
    (net (code "250") (name "unconnected-(P9-Pad35)") (class "Default")
      (node (ref "P9") (pin "35") (pinfunction "35_35") (pintype "passive"))
    )
    (net (code "251") (name "unconnected-(P9-Pad39)") (class "Default")
      (node (ref "P9") (pin "39") (pinfunction "39_39") (pintype "passive"))
    )
    (net (code "252") (name "unconnected-(P10-Pad16)") (class "Default")
      (node (ref "P10") (pin "16") (pinfunction "16_16") (pintype "passive"))
    )
    (net (code "253") (name "unconnected-(P10-Pad37)") (class "Default")
      (node (ref "P10") (pin "37") (pinfunction "37_37") (pintype "passive"))
    )
    (net (code "254") (name "unconnected-(P10-Pad39)") (class "Default")
      (node (ref "P10") (pin "39") (pinfunction "39_39") (pintype "passive"))
    )
    (net (code "255") (name "unconnected-(U11-1.2V-Pad1A4)") (class "Default")
      (node (ref "U11") (pin "1A4") (pinfunction "1.2V_1A4") (pintype "passive"))
    )
    (net (code "256") (name "unconnected-(U11-1.8V-Pad1A6)") (class "Default")
      (node (ref "U11") (pin "1A6") (pinfunction "1.8V_1A6") (pintype "passive"))
    )
    (net (code "257") (name "unconnected-(U11-2.5V-Pad2A18)") (class "Default")
      (node (ref "U11") (pin "2A18") (pinfunction "2.5V_2A18") (pintype "passive"))
    )
    (net (code "258") (name "unconnected-(U11-3.3V-Pad1B1)") (class "Default")
      (node (ref "U11") (pin "1B1") (pinfunction "3.3V_1B1") (pintype "passive"))
    )
    (net (code "259") (name "unconnected-(U11-3.3V-Pad2A1)") (class "Default")
      (node (ref "U11") (pin "2A1") (pinfunction "3.3V_2A1") (pintype "passive"))
    )
    (net (code "260") (name "unconnected-(U11-3.3V-Pad2B1)") (class "Default")
      (node (ref "U11") (pin "2B1") (pinfunction "3.3V_2B1") (pintype "passive"))
    )
    (net (code "261") (name "unconnected-(U11-3.3V-Pad2C1)") (class "Default")
      (node (ref "U11") (pin "2C1") (pinfunction "3.3V_2C1") (pintype "passive"))
    )
    (net (code "262") (name "unconnected-(U11-AA1{slash}L31n-Pad1B32)") (class "Default")
      (node (ref "U11") (pin "1B32") (pinfunction "AA1/L31n_1B32") (pintype "passive"))
    )
    (net (code "263") (name "unconnected-(U11-AA3{slash}CLKOUT-Pad1A19)") (class "Default")
      (node (ref "U11") (pin "1A19") (pinfunction "AA3/CLKOUT_1A19") (pintype "passive"))
    )
    (net (code "264") (name "unconnected-(U11-AA13{slash}B23p-Pad2A32)") (class "Default")
      (node (ref "U11") (pin "2A32") (pinfunction "AA13/B23p_2A32") (pintype "passive"))
    )
    (net (code "265") (name "unconnected-(U11-AB3{slash}CLKOUT-Pad1A21)") (class "Default")
      (node (ref "U11") (pin "1A21") (pinfunction "AB3/CLKOUT_1A21") (pintype "passive"))
    )
    (net (code "266") (name "unconnected-(U11-AB13{slash}B23n-Pad2A34)") (class "Default")
      (node (ref "U11") (pin "2A34") (pinfunction "AB13/B23n_2A34") (pintype "passive"))
    )
    (net (code "267") (name "unconnected-(U11-AB18{slash}IO-Pad2A30)") (class "Default")
      (node (ref "U11") (pin "2A30") (pinfunction "AB18/IO_2A30") (pintype "passive"))
    )
    (net (code "268") (name "unconnected-(U11-B11{slash}CLKIN-Pad1A13)") (class "Default")
      (node (ref "U11") (pin "1A13") (pinfunction "B11/CLKIN_1A13") (pintype "passive"))
    )
    (net (code "269") (name "unconnected-(U11-B21{slash}R3p-Pad2C23)") (class "Default")
      (node (ref "U11") (pin "2C23") (pinfunction "B21/R3p_2C23") (pintype "passive"))
    )
    (net (code "270") (name "unconnected-(U11-B22{slash}R3n-Pad2C25)") (class "Default")
      (node (ref "U11") (pin "2C25") (pinfunction "B22/R3n_2C25") (pintype "passive"))
    )
    (net (code "271") (name "unconnected-(U11-C20{slash}R2n-Pad2C29)") (class "Default")
      (node (ref "U11") (pin "2C29") (pinfunction "C20/R2n_2C29") (pintype "passive"))
    )
    (net (code "272") (name "unconnected-(U11-C22{slash}R4n-Pad2C21)") (class "Default")
      (node (ref "U11") (pin "2C21") (pinfunction "C22/R4n_2C21") (pintype "passive"))
    )
    (net (code "273") (name "unconnected-(U11-CHARGE_DET-Pad2A17)") (class "Default")
      (node (ref "U11") (pin "2A17") (pinfunction "CHARGE_DET_2A17") (pintype "passive"))
    )
    (net (code "274") (name "unconnected-(U11-D20{slash}R2p-Pad2C27)") (class "Default")
      (node (ref "U11") (pin "2C27") (pinfunction "D20/R2p_2C27") (pintype "passive"))
    )
    (net (code "275") (name "unconnected-(U11-F17{slash}R1n-Pad2C33)") (class "Default")
      (node (ref "U11") (pin "2C33") (pinfunction "F17/R1n_2C33") (pintype "passive"))
    )
    (net (code "276") (name "unconnected-(U11-G17{slash}R1p-Pad2C31)") (class "Default")
      (node (ref "U11") (pin "2C31") (pinfunction "G17/R1p_2C31") (pintype "passive"))
    )
    (net (code "277") (name "unconnected-(U11-GND-Pad1A39)") (class "Default")
      (node (ref "U11") (pin "1A39") (pinfunction "GND_1A39") (pintype "passive"))
    )
    (net (code "278") (name "unconnected-(U11-HSMC_VS0-Pad1A10)") (class "Default")
      (node (ref "U11") (pin "1A10") (pinfunction "HSMC_VS0_1A10") (pintype "passive"))
    )
    (net (code "279") (name "unconnected-(U11-HSMC_VS0-Pad2A10)") (class "Default")
      (node (ref "U11") (pin "2A10") (pinfunction "HSMC_VS0_2A10") (pintype "passive"))
    )
    (net (code "280") (name "unconnected-(U11-HSMC_VS1-Pad1A12)") (class "Default")
      (node (ref "U11") (pin "1A12") (pinfunction "HSMC_VS1_1A12") (pintype "passive"))
    )
    (net (code "281") (name "unconnected-(U11-HSMC_VS1-Pad2A12)") (class "Default")
      (node (ref "U11") (pin "2A12") (pinfunction "HSMC_VS1_2A12") (pintype "passive"))
    )
    (net (code "282") (name "unconnected-(U11-HSMC_VS2-Pad1A14)") (class "Default")
      (node (ref "U11") (pin "1A14") (pinfunction "HSMC_VS2_1A14") (pintype "passive"))
    )
    (net (code "283") (name "unconnected-(U11-HSMC_VS2-Pad2A14)") (class "Default")
      (node (ref "U11") (pin "2A14") (pinfunction "HSMC_VS2_2A14") (pintype "passive"))
    )
    (net (code "284") (name "unconnected-(U11-J17{slash}IO-Pad2C38)") (class "Default")
      (node (ref "U11") (pin "2C38") (pinfunction "J17/IO_2C38") (pintype "passive"))
    )
    (net (code "285") (name "unconnected-(U11-J18{slash}R12n-Pad2C36)") (class "Default")
      (node (ref "U11") (pin "2C36") (pinfunction "J18/R12n_2C36") (pintype "passive"))
    )
    (net (code "286") (name "unconnected-(U11-J19{slash}R10p-Pad2A35)") (class "Default")
      (node (ref "U11") (pin "2A35") (pinfunction "J19/R10p_2A35") (pintype "passive"))
    )
    (net (code "287") (name "unconnected-(U11-J20{slash}R10n-Pad2A37)") (class "Default")
      (node (ref "U11") (pin "2A37") (pinfunction "J20/R10n_2A37") (pintype "passive"))
    )
    (net (code "288") (name "unconnected-(U11-JTAG_TCK-Pad1A25)") (class "Default")
      (node (ref "U11") (pin "1A25") (pinfunction "JTAG_TCK_1A25") (pintype "passive"))
    )
    (net (code "289") (name "unconnected-(U11-JTAG_TCK-Pad2A25)") (class "Default")
      (node (ref "U11") (pin "2A25") (pinfunction "JTAG_TCK_2A25") (pintype "passive"))
    )
    (net (code "290") (name "unconnected-(U11-JTAG_TDI-Pad1A24)") (class "Default")
      (node (ref "U11") (pin "1A24") (pinfunction "JTAG_TDI_1A24") (pintype "passive"))
    )
    (net (code "291") (name "unconnected-(U11-JTAG_TDI-Pad2A24)") (class "Default")
      (node (ref "U11") (pin "2A24") (pinfunction "JTAG_TDI_2A24") (pintype "passive"))
    )
    (net (code "292") (name "unconnected-(U11-JTAG_TDO-Pad1A27)") (class "Default")
      (node (ref "U11") (pin "1A27") (pinfunction "JTAG_TDO_1A27") (pintype "passive"))
    )
    (net (code "293") (name "unconnected-(U11-JTAG_TDO-Pad2A27)") (class "Default")
      (node (ref "U11") (pin "2A27") (pinfunction "JTAG_TDO_2A27") (pintype "passive"))
    )
    (net (code "294") (name "unconnected-(U11-JTAG_TMC-Pad1A22)") (class "Default")
      (node (ref "U11") (pin "1A22") (pinfunction "JTAG_TMC_1A22") (pintype "passive"))
    )
    (net (code "295") (name "unconnected-(U11-JTAG_TMC-Pad2A22)") (class "Default")
      (node (ref "U11") (pin "2A22") (pinfunction "JTAG_TMC_2A22") (pintype "passive"))
    )
    (net (code "296") (name "unconnected-(U11-K21{slash}R16p-Pad2C35)") (class "Default")
      (node (ref "U11") (pin "2C35") (pinfunction "K21/R16p_2C35") (pintype "passive"))
    )
    (net (code "297") (name "unconnected-(U11-K22{slash}R16n-Pad2C37)") (class "Default")
      (node (ref "U11") (pin "2C37") (pinfunction "K22/R16n_2C37") (pintype "passive"))
    )
    (net (code "298") (name "unconnected-(U11-N5{slash}L22n-Pad1C36)") (class "Default")
      (node (ref "U11") (pin "1C36") (pinfunction "N5/L22n_1C36") (pintype "passive"))
    )
    (net (code "299") (name "unconnected-(U11-N7{slash}L30p-Pad1C15)") (class "Default")
      (node (ref "U11") (pin "1C15") (pinfunction "N7/L30p_1C15") (pintype "passive"))
    )
    (net (code "300") (name "unconnected-(U11-N17{slash}R21n-Pad2C26)") (class "Default")
      (node (ref "U11") (pin "2C26") (pinfunction "N17/R21n_2C26") (pintype "passive"))
    )
    (net (code "301") (name "unconnected-(U11-N18{slash}R21p-Pad2C24)") (class "Default")
      (node (ref "U11") (pin "2C24") (pinfunction "N18/R21p_2C24") (pintype "passive"))
    )
    (net (code "302") (name "unconnected-(U11-N20{slash}R22n-Pad2C22)") (class "Default")
      (node (ref "U11") (pin "2C22") (pinfunction "N20/R22n_2C22") (pintype "passive"))
    )
    (net (code "303") (name "unconnected-(U11-OVP_FLAG-Pad1A17)") (class "Default")
      (node (ref "U11") (pin "1A17") (pinfunction "OVP_FLAG_1A17") (pintype "passive"))
    )
    (net (code "304") (name "unconnected-(U11-P5{slash}L26p-Pad1C38)") (class "Default")
      (node (ref "U11") (pin "1C38") (pinfunction "P5/L26p_1C38") (pintype "passive"))
    )
    (net (code "305") (name "unconnected-(U11-P6{slash}L32p-Pad1C19)") (class "Default")
      (node (ref "U11") (pin "1C19") (pinfunction "P6/L32p_1C19") (pintype "passive"))
    )
    (net (code "306") (name "unconnected-(U11-P7{slash}L30n-Pad1C17)") (class "Default")
      (node (ref "U11") (pin "1C17") (pinfunction "P7/L30n_1C17") (pintype "passive"))
    )
    (net (code "307") (name "unconnected-(U11-Pad1A8)") (class "Default")
      (node (ref "U11") (pin "1A8") (pintype "passive"))
    )
    (net (code "308") (name "unconnected-(U11-Pad1A15)") (class "Default")
      (node (ref "U11") (pin "1A15") (pintype "passive"))
    )
    (net (code "309") (name "unconnected-(U11-Pad1A16)") (class "Default")
      (node (ref "U11") (pin "1A16") (pintype "passive"))
    )
    (net (code "310") (name "unconnected-(U11-Pad1A18)") (class "Default")
      (node (ref "U11") (pin "1A18") (pintype "passive"))
    )
    (net (code "311") (name "unconnected-(U11-Pad1A36)") (class "Default")
      (node (ref "U11") (pin "1A36") (pintype "passive"))
    )
    (net (code "312") (name "unconnected-(U11-Pad1A38)") (class "Default")
      (node (ref "U11") (pin "1A38") (pintype "passive"))
    )
    (net (code "313") (name "unconnected-(U11-R4{slash}L27p-Pad1C3)") (class "Default")
      (node (ref "U11") (pin "1C3") (pinfunction "R4/L27p_1C3") (pintype "passive"))
    )
    (net (code "314") (name "unconnected-(U11-R5{slash}L32n-Pad1C21)") (class "Default")
      (node (ref "U11") (pin "1C21") (pinfunction "R5/L32n_1C21") (pintype "passive"))
    )
    (net (code "315") (name "unconnected-(U11-R6{slash}L33n-Pad1C37)") (class "Default")
      (node (ref "U11") (pin "1C37") (pinfunction "R6/L33n_1C37") (pintype "passive"))
    )
    (net (code "316") (name "unconnected-(U11-R14{slash}B41p-Pad2C28)") (class "Default")
      (node (ref "U11") (pin "2C28") (pinfunction "R14/B41p_2C28") (pintype "passive"))
    )
    (net (code "317") (name "unconnected-(U11-R15{slash}B41n-Pad2C30)") (class "Default")
      (node (ref "U11") (pin "2C30") (pinfunction "R15/B41n_2C30") (pintype "passive"))
    )
    (net (code "318") (name "unconnected-(U11-R16{slash}IO{slash}CLKOUT-Pad2A21)") (class "Default")
      (node (ref "U11") (pin "2A21") (pinfunction "R16/IO/CLKOUT_2A21") (pintype "passive"))
    )
    (net (code "319") (name "unconnected-(U11-R17{slash}R30n-Pad1C22)") (class "Default")
      (node (ref "U11") (pin "1C22") (pinfunction "R17/R30n_1C22") (pintype "passive"))
    )
    (net (code "320") (name "unconnected-(U11-R18{slash}R26n-Pad1B33)") (class "Default")
      (node (ref "U11") (pin "1B33") (pinfunction "R18/R26n_1B33") (pintype "passive"))
    )
    (net (code "321") (name "unconnected-(U11-T5{slash}L33p-Pad1C35)") (class "Default")
      (node (ref "U11") (pin "1C35") (pinfunction "T5/L33p_1C35") (pintype "passive"))
    )
    (net (code "322") (name "unconnected-(U11-T10{slash}B13p-Pad1B36)") (class "Default")
      (node (ref "U11") (pin "1B36") (pinfunction "T10/B13p_1B36") (pintype "passive"))
    )
    (net (code "323") (name "unconnected-(U11-T11{slash}B13n-Pad1B38)") (class "Default")
      (node (ref "U11") (pin "1B38") (pinfunction "T11/B13n_1B38") (pintype "passive"))
    )
    (net (code "324") (name "unconnected-(U11-T16{slash}IO{slash}CLKOUT-Pad2A19)") (class "Default")
      (node (ref "U11") (pin "2A19") (pinfunction "T16/IO/CLKOUT_2A19") (pintype "passive"))
    )
    (net (code "325") (name "unconnected-(U11-T19{slash}R31p-Pad1C24)") (class "Default")
      (node (ref "U11") (pin "1C24") (pinfunction "T19/R31p_1C24") (pintype "passive"))
    )
    (net (code "326") (name "unconnected-(U11-T20{slash}R31n-Pad1C26)") (class "Default")
      (node (ref "U11") (pin "1C26") (pinfunction "T20/R31n_1C26") (pintype "passive"))
    )
    (net (code "327") (name "unconnected-(U11-T21{slash}CLKIN-Pad1A26)") (class "Default")
      (node (ref "U11") (pin "1A26") (pinfunction "T21/CLKIN_1A26") (pintype "passive"))
    )
    (net (code "328") (name "unconnected-(U11-T22{slash}CLKIN-Pad2A26)") (class "Default")
      (node (ref "U11") (pin "2A26") (pinfunction "T22/CLKIN_2A26") (pintype "passive"))
    )
    (net (code "329") (name "unconnected-(U11-U11{slash}B19p-Pad1C12)") (class "Default")
      (node (ref "U11") (pin "1C12") (pinfunction "U11/B19p_1C12") (pintype "passive"))
    )
    (net (code "330") (name "unconnected-(U11-U12{slash}B28p-Pad2A31)") (class "Default")
      (node (ref "U11") (pin "2A31") (pinfunction "U12/B28p_2A31") (pintype "passive"))
    )
    (net (code "331") (name "unconnected-(U11-U13{slash}B32p-Pad2A28)") (class "Default")
      (node (ref "U11") (pin "2A28") (pinfunction "U13/B32p_2A28") (pintype "passive"))
    )
    (net (code "332") (name "unconnected-(U11-U15{slash}B34p-Pad2C32)") (class "Default")
      (node (ref "U11") (pin "2C32") (pinfunction "U15/B34p_2C32") (pintype "passive"))
    )
    (net (code "333") (name "unconnected-(U11-U19{slash}R34p-Pad1C23)") (class "Default")
      (node (ref "U11") (pin "1C23") (pinfunction "U19/R34p_1C23") (pintype "passive"))
    )
    (net (code "334") (name "unconnected-(U11-U20{slash}R34n-Pad1C25)") (class "Default")
      (node (ref "U11") (pin "1C25") (pinfunction "U20/R34n_1C25") (pintype "passive"))
    )
    (net (code "335") (name "unconnected-(U11-U21{slash}R27p-Pad1C32)") (class "Default")
      (node (ref "U11") (pin "1C32") (pinfunction "U21/R27p_1C32") (pintype "passive"))
    )
    (net (code "336") (name "unconnected-(U11-U22{slash}R27n-Pad1C34)") (class "Default")
      (node (ref "U11") (pin "1C34") (pinfunction "U22/R27n_1C34") (pintype "passive"))
    )
    (net (code "337") (name "unconnected-(U11-V1{slash}L25n-Pad1B37)") (class "Default")
      (node (ref "U11") (pin "1B37") (pinfunction "V1/L25n_1B37") (pintype "passive"))
    )
    (net (code "338") (name "unconnected-(U11-V2{slash}L25p-Pad1B35)") (class "Default")
      (node (ref "U11") (pin "1B35") (pinfunction "V2/L25p_1B35") (pintype "passive"))
    )
    (net (code "339") (name "unconnected-(U11-V11{slash}B19n-Pad1C14)") (class "Default")
      (node (ref "U11") (pin "1C14") (pinfunction "V11/B19n_1C14") (pintype "passive"))
    )
    (net (code "340") (name "unconnected-(U11-V13{slash}B31p-Pad2A29)") (class "Default")
      (node (ref "U11") (pin "2A29") (pinfunction "V13/B31p_2A29") (pintype "passive"))
    )
    (net (code "341") (name "unconnected-(U11-V15{slash}B43n-Pad2C34)") (class "Default")
      (node (ref "U11") (pin "2C34") (pinfunction "V15/B43n_2C34") (pintype "passive"))
    )
    (net (code "342") (name "unconnected-(U11-V21{slash}R29p-Pad1C28)") (class "Default")
      (node (ref "U11") (pin "1C28") (pinfunction "V21/R29p_1C28") (pintype "passive"))
    )
    (net (code "343") (name "unconnected-(U11-V22{slash}R29n-Pad1C30)") (class "Default")
      (node (ref "U11") (pin "1C30") (pinfunction "V22/R29n_1C30") (pintype "passive"))
    )
    (net (code "344") (name "unconnected-(U11-VCCIO-Pad1A3)") (class "Default")
      (node (ref "U11") (pin "1A3") (pinfunction "VCCIO_1A3") (pintype "passive"))
    )
    (net (code "345") (name "unconnected-(U11-VCCIO-Pad1A5)") (class "Default")
      (node (ref "U11") (pin "1A5") (pinfunction "VCCIO_1A5") (pintype "passive"))
    )
    (net (code "346") (name "unconnected-(U11-VCCIO-Pad1A40)") (class "Default")
      (node (ref "U11") (pin "1A40") (pinfunction "VCCIO_1A40") (pintype "passive"))
    )
    (net (code "347") (name "unconnected-(U11-VCCIO-Pad1B40)") (class "Default")
      (node (ref "U11") (pin "1B40") (pinfunction "VCCIO_1B40") (pintype "passive"))
    )
    (net (code "348") (name "unconnected-(U11-VCCIO-Pad1C40)") (class "Default")
      (node (ref "U11") (pin "1C40") (pinfunction "VCCIO_1C40") (pintype "passive"))
    )
    (net (code "349") (name "unconnected-(U11-VCCIO-Pad2A7)") (class "Default")
      (node (ref "U11") (pin "2A7") (pinfunction "VCCIO_2A7") (pintype "passive"))
    )
    (net (code "350") (name "unconnected-(U11-VCCIO-Pad2A9)") (class "Default")
      (node (ref "U11") (pin "2A9") (pinfunction "VCCIO_2A9") (pintype "passive"))
    )
    (net (code "351") (name "unconnected-(U11-VCCIO-Pad2A11)") (class "Default")
      (node (ref "U11") (pin "2A11") (pinfunction "VCCIO_2A11") (pintype "passive"))
    )
    (net (code "352") (name "unconnected-(U11-VCCIO-Pad2A40)") (class "Default")
      (node (ref "U11") (pin "2A40") (pinfunction "VCCIO_2A40") (pintype "passive"))
    )
    (net (code "353") (name "unconnected-(U11-VCCIO-Pad2B40)") (class "Default")
      (node (ref "U11") (pin "2B40") (pinfunction "VCCIO_2B40") (pintype "passive"))
    )
    (net (code "354") (name "unconnected-(U11-VCCIO-Pad2C40)") (class "Default")
      (node (ref "U11") (pin "2C40") (pinfunction "VCCIO_2C40") (pintype "passive"))
    )
    (net (code "355") (name "unconnected-(U11-VDC-Pad2A3)") (class "Default")
      (node (ref "U11") (pin "2A3") (pinfunction "VDC_2A3") (pintype "passive"))
    )
    (net (code "356") (name "unconnected-(U11-VDC-Pad2A5)") (class "Default")
      (node (ref "U11") (pin "2A5") (pinfunction "VDC_2A5") (pintype "passive"))
    )
    (net (code "357") (name "unconnected-(U11-VREF-Pad1A7)") (class "Default")
      (node (ref "U11") (pin "1A7") (pinfunction "VREF_1A7") (pintype "passive"))
    )
    (net (code "358") (name "unconnected-(U11-VREF-Pad1A9)") (class "Default")
      (node (ref "U11") (pin "1A9") (pinfunction "VREF_1A9") (pintype "passive"))
    )
    (net (code "359") (name "unconnected-(U11-VREF-Pad2A13)") (class "Default")
      (node (ref "U11") (pin "2A13") (pinfunction "VREF_2A13") (pintype "passive"))
    )
    (net (code "360") (name "unconnected-(U11-VREF-Pad2A15)") (class "Default")
      (node (ref "U11") (pin "2A15") (pinfunction "VREF_2A15") (pintype "passive"))
    )
    (net (code "361") (name "unconnected-(U11-VREF-Pad2A16)") (class "Default")
      (node (ref "U11") (pin "2A16") (pinfunction "VREF_2A16") (pintype "passive"))
    )
    (net (code "362") (name "unconnected-(U11-W15{slash}B35p-Pad2A33)") (class "Default")
      (node (ref "U11") (pin "2A33") (pinfunction "W15/B35p_2A33") (pintype "passive"))
    )
    (net (code "363") (name "unconnected-(U11-W21{slash}R32p-Pad1C31)") (class "Default")
      (node (ref "U11") (pin "1C31") (pinfunction "W21/R32p_1C31") (pintype "passive"))
    )
    (net (code "364") (name "unconnected-(U11-W22{slash}R32n-Pad1C33)") (class "Default")
      (node (ref "U11") (pin "1C33") (pinfunction "W22/R32n_1C33") (pintype "passive"))
    )
    (net (code "365") (name "unconnected-(U11-Y1{slash}L29n-Pad1C13)") (class "Default")
      (node (ref "U11") (pin "1C13") (pinfunction "Y1/L29n_1C13") (pintype "passive"))
    )
    (net (code "366") (name "unconnected-(U11-Y4{slash}B3p-Pad2A23)") (class "Default")
      (node (ref "U11") (pin "2A23") (pinfunction "Y4/B3p_2A23") (pintype "passive"))
    )
    (net (code "367") (name "unconnected-(U11-Y8{slash}B11p-Pad1B34)") (class "Default")
      (node (ref "U11") (pin "1B34") (pinfunction "Y8/B11p_1B34") (pintype "passive"))
    )
    (net (code "368") (name "unconnected-(U11-Y21{slash}R35p-Pad1C27)") (class "Default")
      (node (ref "U11") (pin "1C27") (pinfunction "Y21/R35p_1C27") (pintype "passive"))
    )
    (net (code "369") (name "unconnected-(U11-Y22{slash}R35n-Pad1C29)") (class "Default")
      (node (ref "U11") (pin "1C29") (pinfunction "Y22/R35n_1C29") (pintype "passive"))
    )
    (net (code "370") (name "unconnected-(U11-n{slash}c-Pad2A4)") (class "Default")
      (node (ref "U11") (pin "2A4") (pinfunction "n/c_2A4") (pintype "passive"))
    )
    (net (code "371") (name "unconnected-(U11-n{slash}c-Pad2A6)") (class "Default")
      (node (ref "U11") (pin "2A6") (pinfunction "n/c_2A6") (pintype "passive"))
    )
    (net (code "372") (name "unconnected-(U11-n{slash}c-Pad2A8)") (class "Default")
      (node (ref "U11") (pin "2A8") (pinfunction "n/c_2A8") (pintype "passive"))
    )
    (net (code "373") (name "unconnected-(U11-n{slash}c-Pad2A20)") (class "Default")
      (node (ref "U11") (pin "2A20") (pinfunction "n/c_2A20") (pintype "passive"))
    )
    (net (code "374") (name "unconnected-(U11-n{slash}c-Pad2A36)") (class "Default")
      (node (ref "U11") (pin "2A36") (pinfunction "n/c_2A36") (pintype "passive"))
    )
    (net (code "375") (name "unconnected-(U11-n{slash}c-Pad2A38)") (class "Default")
      (node (ref "U11") (pin "2A38") (pinfunction "n/c_2A38") (pintype "passive"))
    )
  )
)
